# ME461_F28027.net
KiCad netlist of a schematic drawn in EAGLE
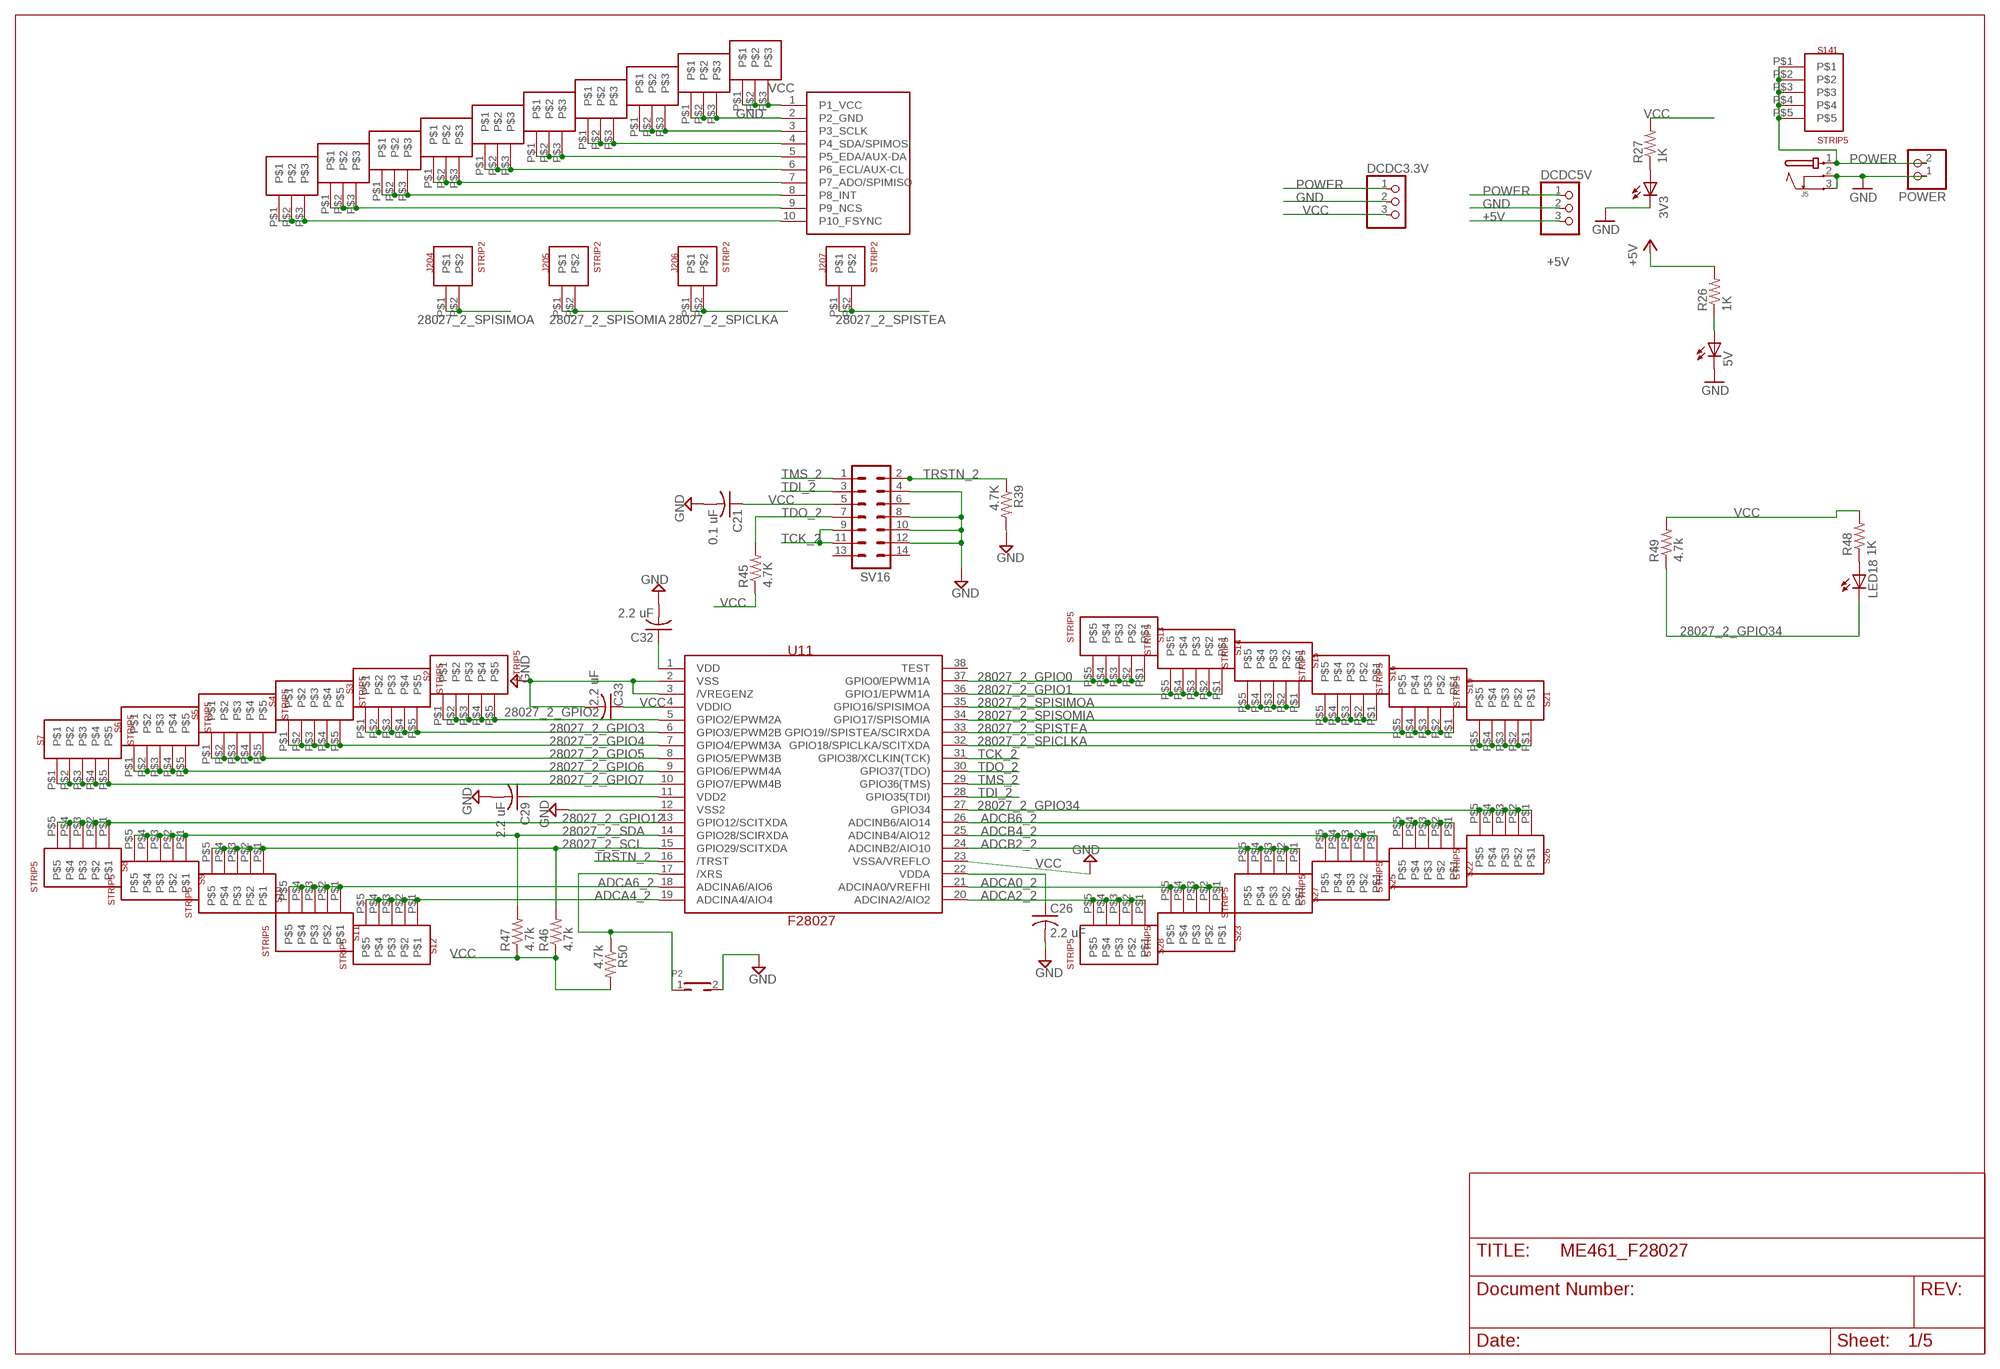
[diagram p0: schematic, sheet 1]
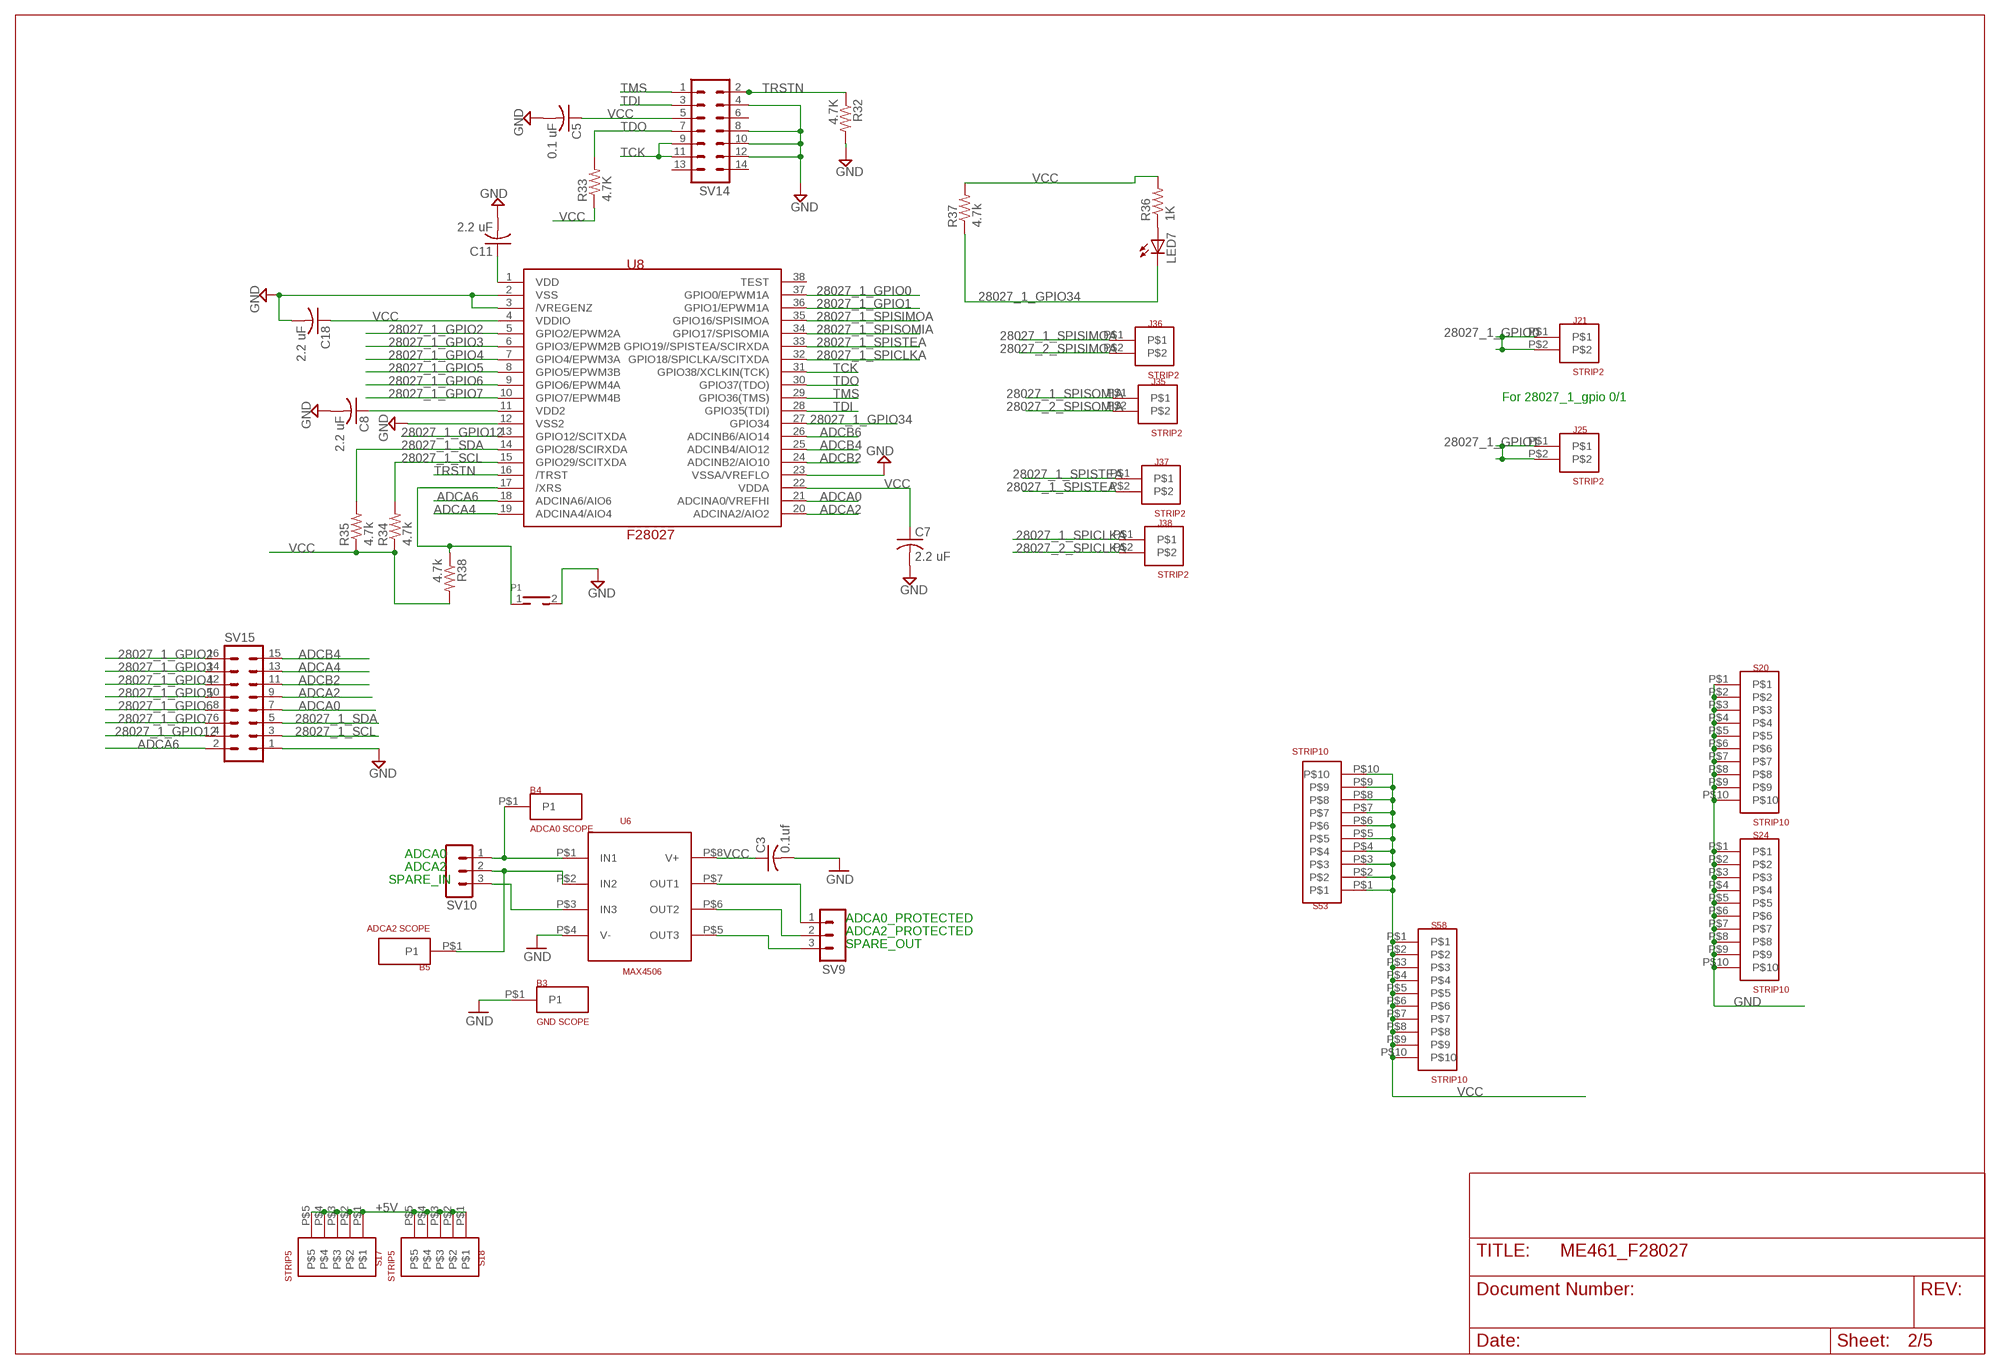
[diagram p1: schematic, sheet 2]
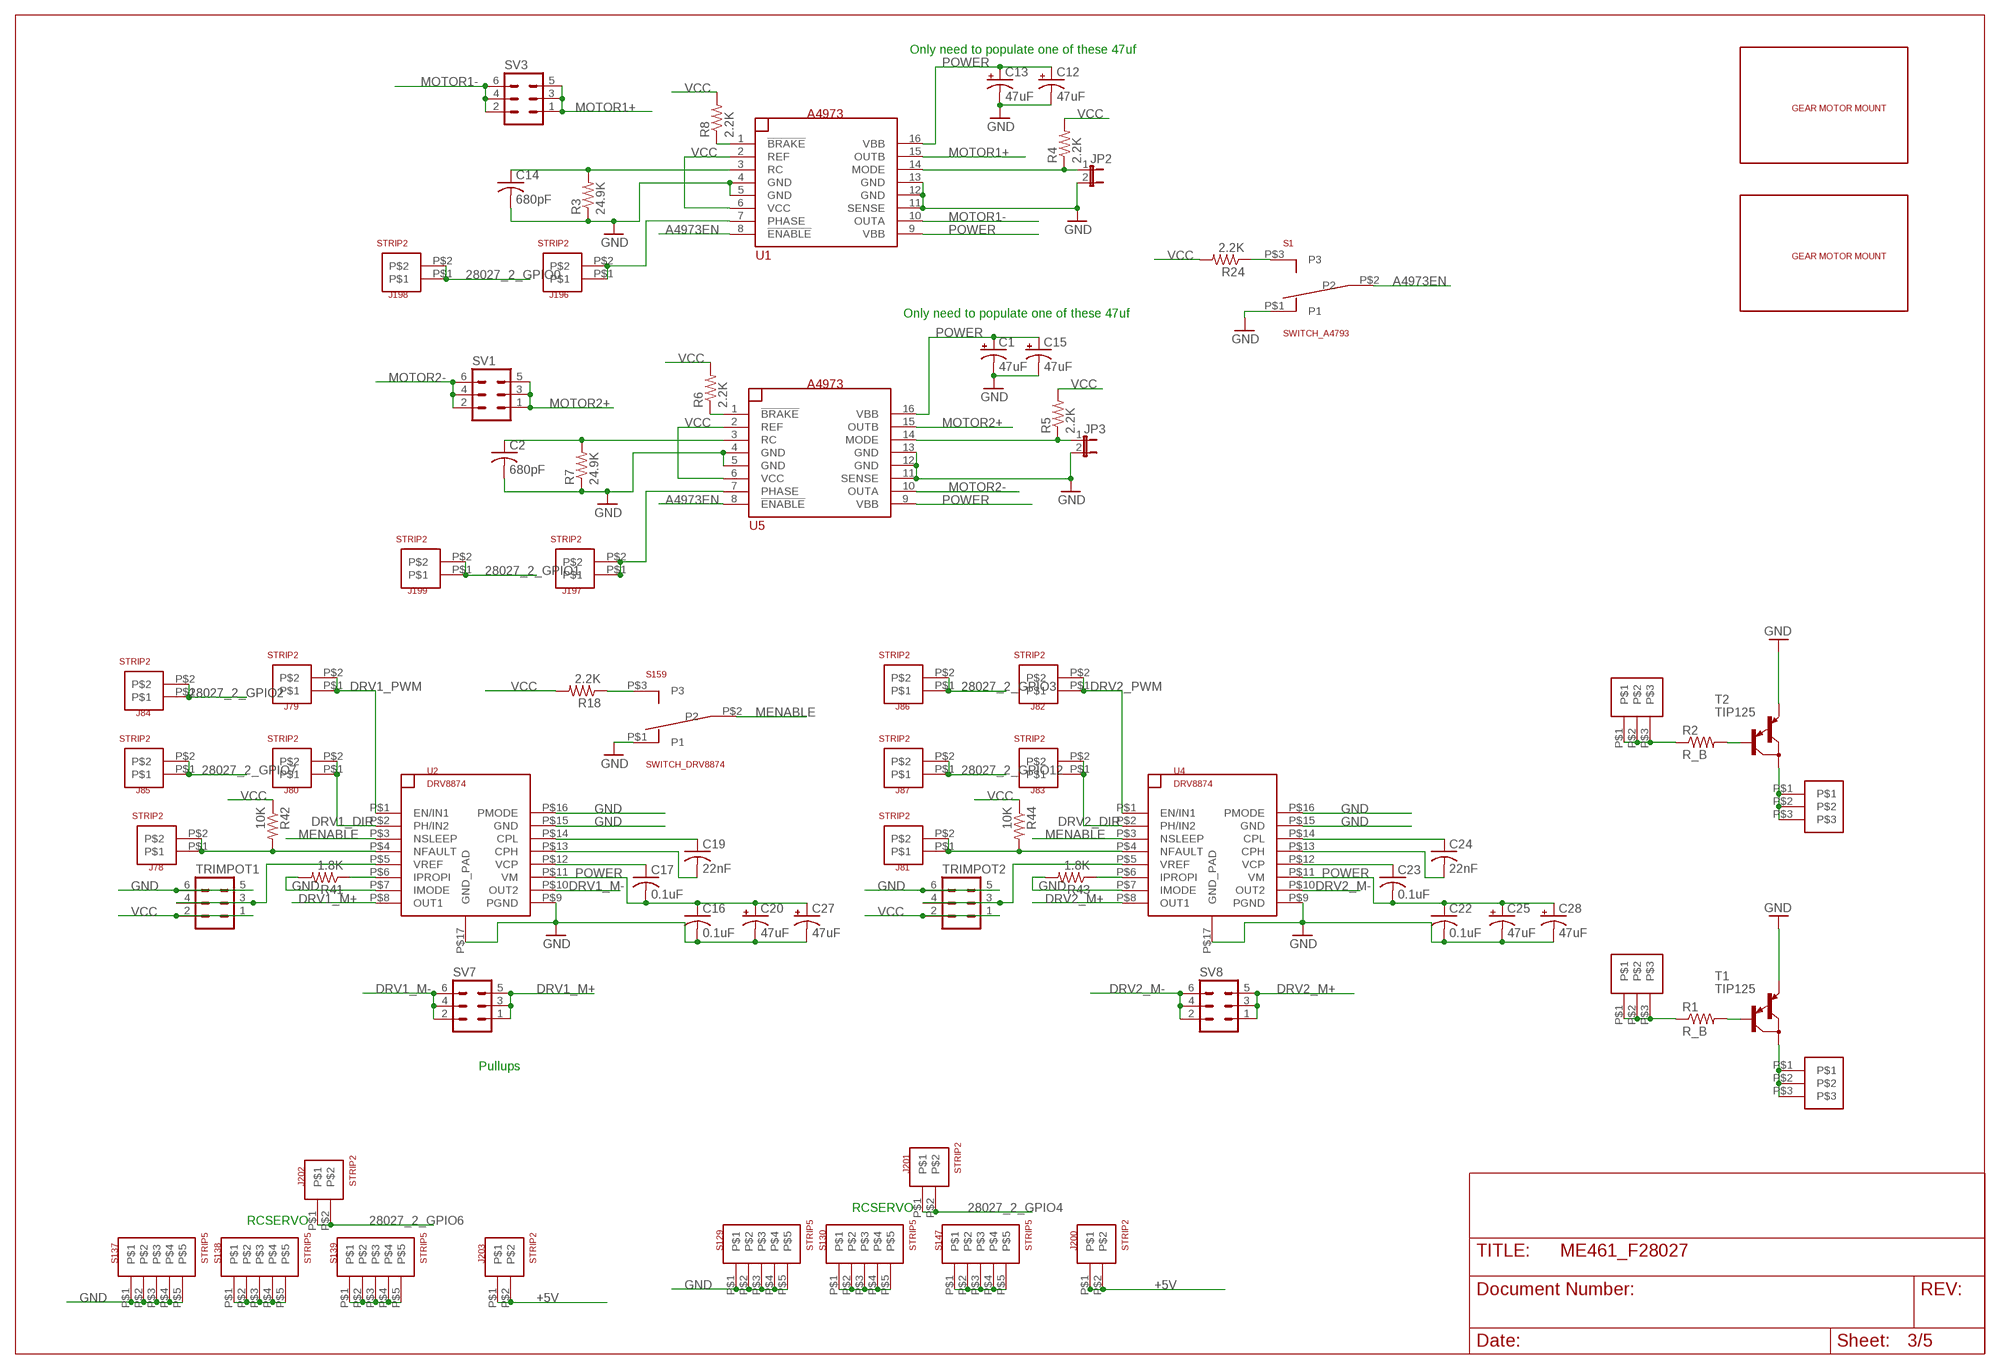
[diagram p2: schematic, sheet 3]
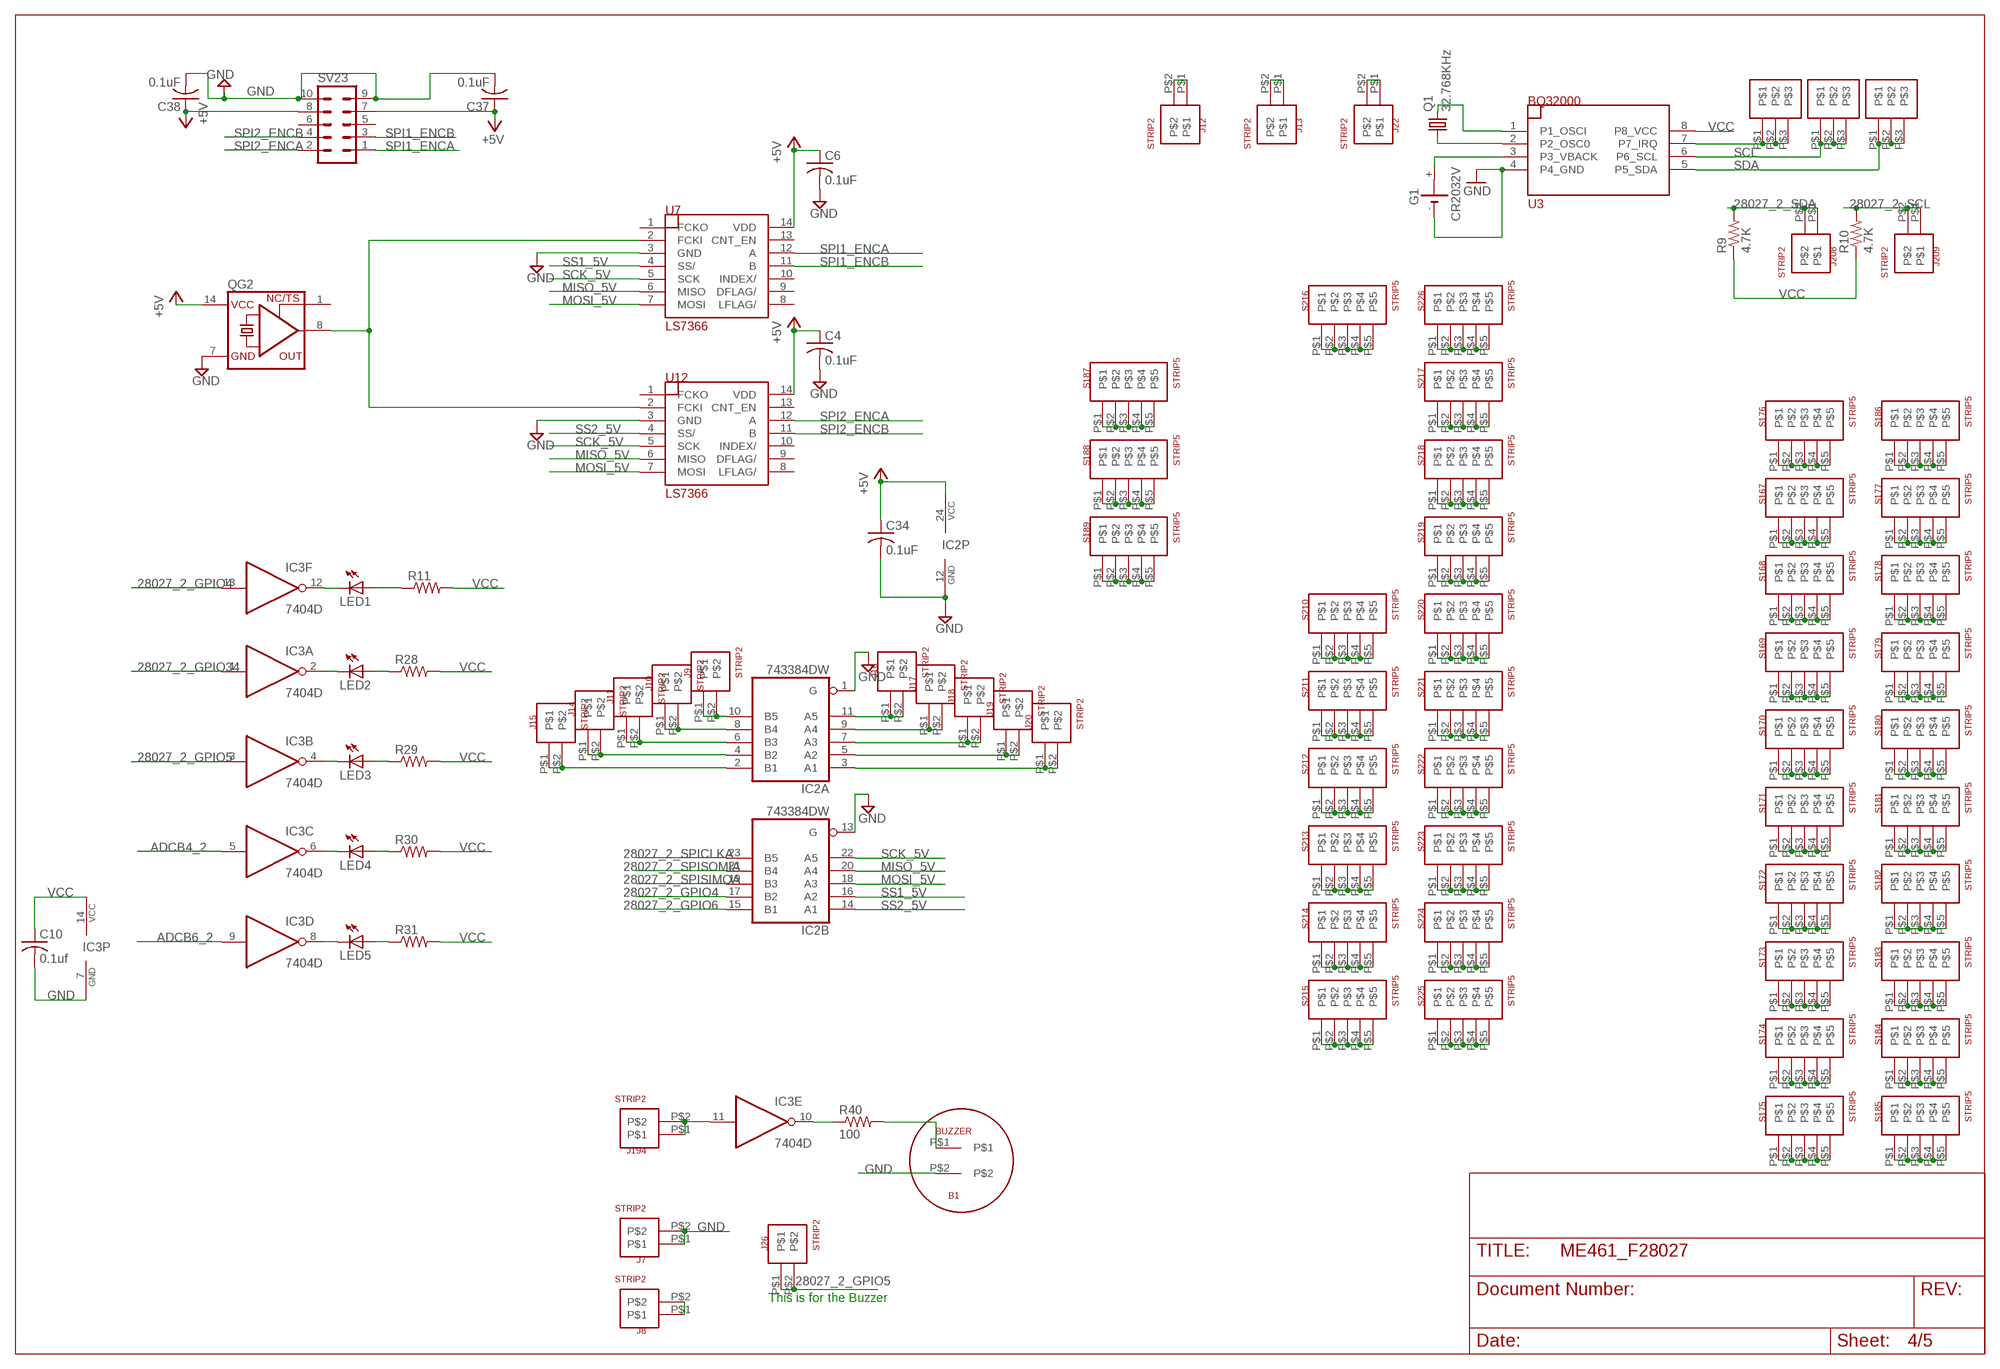
[diagram p3: schematic, sheet 4]
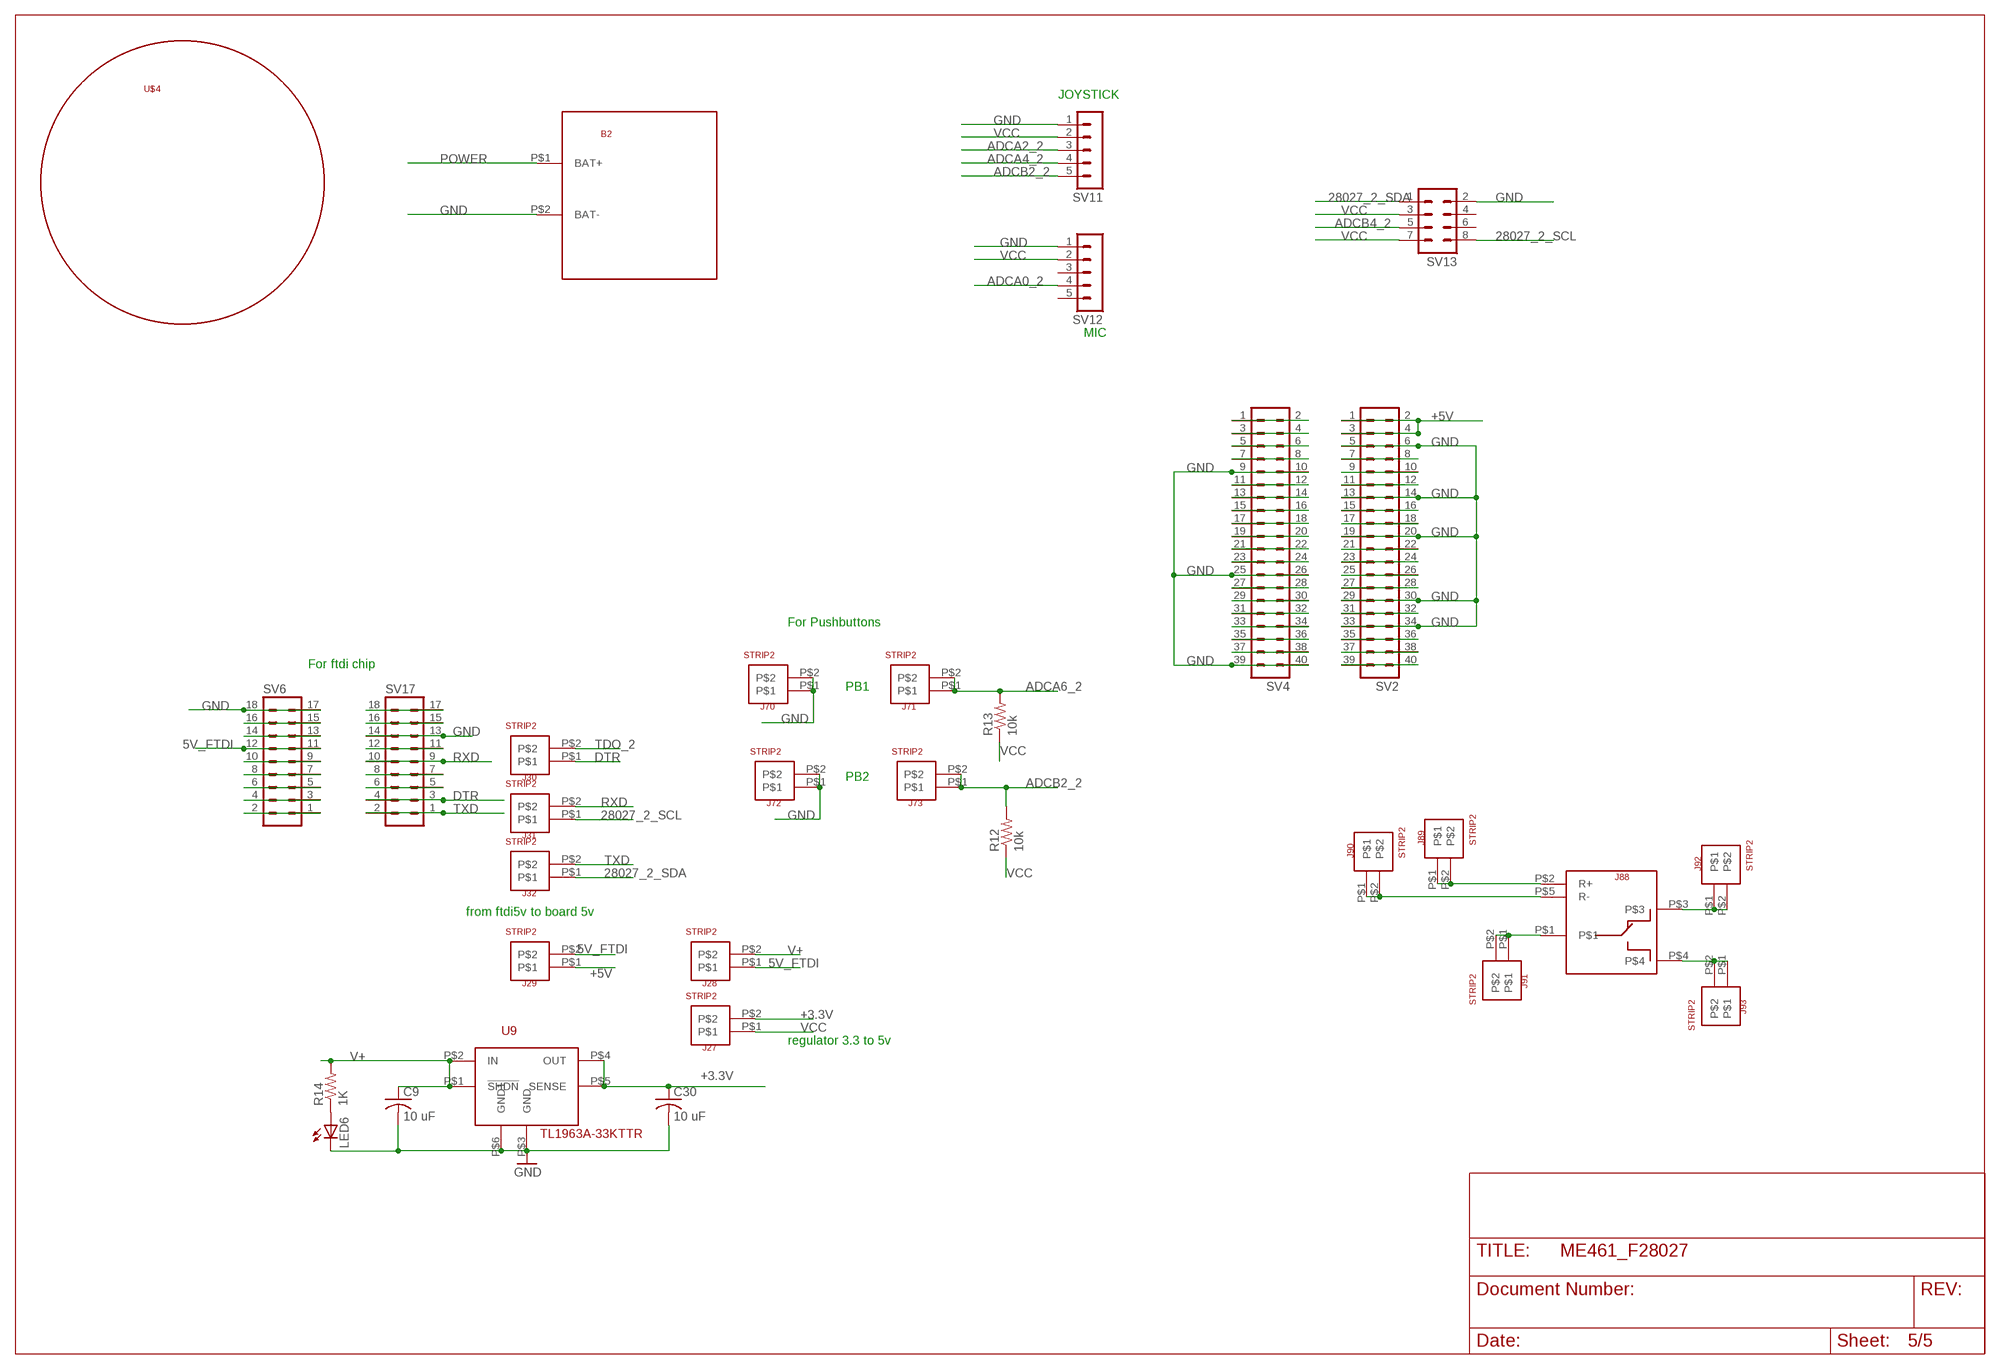
[diagram p4: schematic, sheet 5]

(export (version "E")
  (design (tool "Eeschema 10.0.6"))
  (components
    (comp (ref "C1")
      (value "47uF")
      (footprint "eagle-import:153CLV-0810")
      (libsource (lib "eagle-import") (part "CPOL-US153CLV-0810"))
    )
    (comp (ref "C2")
      (value "680pF")
      (footprint "eagle-import:C1206")
      (libsource (lib "eagle-import") (part "C-USC1206"))
    )
    (comp (ref "C12")
      (value "47uF")
      (footprint "eagle-import:153CLV-0810")
      (libsource (lib "eagle-import") (part "CPOL-US153CLV-0810"))
    )
    (comp (ref "C13")
      (value "47uF")
      (footprint "eagle-import:153CLV-0810")
      (libsource (lib "eagle-import") (part "CPOL-US153CLV-0810"))
    )
    (comp (ref "C14")
      (value "680pF")
      (footprint "eagle-import:C1206")
      (libsource (lib "eagle-import") (part "C-USC1206"))
    )
    (comp (ref "C15")
      (value "47uF")
      (footprint "eagle-import:153CLV-0810")
      (libsource (lib "eagle-import") (part "CPOL-US153CLV-0810"))
    )
    (comp (ref "C16")
      (value "0.1uF")
      (footprint "eagle-import:C1206")
      (libsource (lib "eagle-import") (part "C-USC1206"))
    )
    (comp (ref "C17")
      (value "0.1uF")
      (footprint "eagle-import:C1206")
      (libsource (lib "eagle-import") (part "C-USC1206"))
    )
    (comp (ref "C19")
      (value "22nF")
      (footprint "eagle-import:C1206")
      (libsource (lib "eagle-import") (part "C-USC1206"))
    )
    (comp (ref "C20")
      (value "47uF")
      (footprint "eagle-import:153CLV-0810")
      (libsource (lib "eagle-import") (part "CPOL-US153CLV-0810"))
    )
    (comp (ref "C22")
      (value "0.1uF")
      (footprint "eagle-import:C1206")
      (libsource (lib "eagle-import") (part "C-USC1206"))
    )
    (comp (ref "C23")
      (value "0.1uF")
      (footprint "eagle-import:C1206")
      (libsource (lib "eagle-import") (part "C-USC1206"))
    )
    (comp (ref "C24")
      (value "22nF")
      (footprint "eagle-import:C1206")
      (libsource (lib "eagle-import") (part "C-USC1206"))
    )
    (comp (ref "C25")
      (value "47uF")
      (footprint "eagle-import:153CLV-0810")
      (libsource (lib "eagle-import") (part "CPOL-US153CLV-0810"))
    )
    (comp (ref "C27")
      (value "47uF")
      (footprint "eagle-import:153CLV-0810")
      (libsource (lib "eagle-import") (part "CPOL-US153CLV-0810"))
    )
    (comp (ref "C28")
      (value "47uF")
      (footprint "eagle-import:153CLV-0810")
      (libsource (lib "eagle-import") (part "CPOL-US153CLV-0810"))
    )
    (comp (ref "J4")
      (value "STRIP3")
      (footprint "eagle-import:STRIP3")
      (libsource (lib "eagle-import") (part "STRIP3"))
    )
    (comp (ref "J6")
      (value "STRIP3")
      (footprint "eagle-import:STRIP3")
      (libsource (lib "eagle-import") (part "STRIP3"))
    )
    (comp (ref "J23")
      (value "STRIP3")
      (footprint "eagle-import:STRIP3")
      (libsource (lib "eagle-import") (part "STRIP3"))
    )
    (comp (ref "J24")
      (value "STRIP3")
      (footprint "eagle-import:STRIP3")
      (libsource (lib "eagle-import") (part "STRIP3"))
    )
    (comp (ref "J78")
      (value "STRIP2")
      (footprint "eagle-import:STRIP2")
      (libsource (lib "eagle-import") (part "STRIP2"))
    )
    (comp (ref "J79")
      (value "STRIP2")
      (footprint "eagle-import:STRIP2")
      (libsource (lib "eagle-import") (part "STRIP2"))
    )
    (comp (ref "J80")
      (value "STRIP2")
      (footprint "eagle-import:STRIP2")
      (libsource (lib "eagle-import") (part "STRIP2"))
    )
    (comp (ref "J81")
      (value "STRIP2")
      (footprint "eagle-import:STRIP2")
      (libsource (lib "eagle-import") (part "STRIP2"))
    )
    (comp (ref "J82")
      (value "STRIP2")
      (footprint "eagle-import:STRIP2")
      (libsource (lib "eagle-import") (part "STRIP2"))
    )
    (comp (ref "J83")
      (value "STRIP2")
      (footprint "eagle-import:STRIP2")
      (libsource (lib "eagle-import") (part "STRIP2"))
    )
    (comp (ref "J84")
      (value "STRIP2")
      (footprint "eagle-import:STRIP2")
      (libsource (lib "eagle-import") (part "STRIP2"))
    )
    (comp (ref "J85")
      (value "STRIP2")
      (footprint "eagle-import:STRIP2")
      (libsource (lib "eagle-import") (part "STRIP2"))
    )
    (comp (ref "J86")
      (value "STRIP2")
      (footprint "eagle-import:STRIP2")
      (libsource (lib "eagle-import") (part "STRIP2"))
    )
    (comp (ref "J87")
      (value "STRIP2")
      (footprint "eagle-import:STRIP2")
      (libsource (lib "eagle-import") (part "STRIP2"))
    )
    (comp (ref "J196")
      (value "STRIP2")
      (footprint "eagle-import:STRIP2")
      (libsource (lib "eagle-import") (part "STRIP2"))
    )
    (comp (ref "J197")
      (value "STRIP2")
      (footprint "eagle-import:STRIP2")
      (libsource (lib "eagle-import") (part "STRIP2"))
    )
    (comp (ref "J198")
      (value "STRIP2")
      (footprint "eagle-import:STRIP2")
      (libsource (lib "eagle-import") (part "STRIP2"))
    )
    (comp (ref "J199")
      (value "STRIP2")
      (footprint "eagle-import:STRIP2")
      (libsource (lib "eagle-import") (part "STRIP2"))
    )
    (comp (ref "J200")
      (value "STRIP2")
      (footprint "eagle-import:STRIP2")
      (libsource (lib "eagle-import") (part "STRIP2"))
    )
    (comp (ref "J201")
      (value "STRIP2")
      (footprint "eagle-import:STRIP2")
      (libsource (lib "eagle-import") (part "STRIP2"))
    )
    (comp (ref "J202")
      (value "STRIP2")
      (footprint "eagle-import:STRIP2")
      (libsource (lib "eagle-import") (part "STRIP2"))
    )
    (comp (ref "J203")
      (value "STRIP2")
      (footprint "eagle-import:STRIP2")
      (libsource (lib "eagle-import") (part "STRIP2"))
    )
    (comp (ref "JP2")
      (value "JP1E")
      (footprint "eagle-import:JP1")
      (libsource (lib "eagle-import") (part "JP1E"))
    )
    (comp (ref "JP3")
      (value "JP1E")
      (footprint "eagle-import:JP1")
      (libsource (lib "eagle-import") (part "JP1E"))
    )
    (comp (ref "R1")
      (value "R_B")
      (footprint "eagle-import:0207_10")
      (libsource (lib "eagle-import") (part "R-US_0207/10"))
    )
    (comp (ref "R2")
      (value "R_B")
      (footprint "eagle-import:0207_10")
      (libsource (lib "eagle-import") (part "R-US_0207/10"))
    )
    (comp (ref "R3")
      (value "24.9K")
      (footprint "eagle-import:M1206")
      (libsource (lib "eagle-import") (part "R-US_M1206"))
    )
    (comp (ref "R4")
      (value "2.2K")
      (footprint "eagle-import:M1206")
      (libsource (lib "eagle-import") (part "R-US_M1206"))
    )
    (comp (ref "R5")
      (value "2.2K")
      (footprint "eagle-import:M1206")
      (libsource (lib "eagle-import") (part "R-US_M1206"))
    )
    (comp (ref "R6")
      (value "2.2K")
      (footprint "eagle-import:M1206")
      (libsource (lib "eagle-import") (part "R-US_M1206"))
    )
    (comp (ref "R7")
      (value "24.9K")
      (footprint "eagle-import:M1206")
      (libsource (lib "eagle-import") (part "R-US_M1206"))
    )
    (comp (ref "R8")
      (value "2.2K")
      (footprint "eagle-import:M1206")
      (libsource (lib "eagle-import") (part "R-US_M1206"))
    )
    (comp (ref "R18")
      (value "2.2K")
      (footprint "eagle-import:M1206")
      (libsource (lib "eagle-import") (part "R-US_M1206"))
    )
    (comp (ref "R24")
      (value "2.2K")
      (footprint "eagle-import:M1206")
      (libsource (lib "eagle-import") (part "R-US_M1206"))
    )
    (comp (ref "R41")
      (value "1.8K")
      (footprint "eagle-import:M1206")
      (libsource (lib "eagle-import") (part "R-US_M1206"))
    )
    (comp (ref "R42")
      (value "10K")
      (footprint "eagle-import:M1206")
      (libsource (lib "eagle-import") (part "R-US_M1206"))
    )
    (comp (ref "R43")
      (value "1.8K")
      (footprint "eagle-import:M1206")
      (libsource (lib "eagle-import") (part "R-US_M1206"))
    )
    (comp (ref "R44")
      (value "10K")
      (footprint "eagle-import:M1206")
      (libsource (lib "eagle-import") (part "R-US_M1206"))
    )
    (comp (ref "S1")
      (value "SWITCH_A4793")
      (footprint "eagle-import:SWITCH_SLIDE")
      (libsource (lib "eagle-import") (part "SWITCH_SLIDE"))
    )
    (comp (ref "S129")
      (value "STRIP5")
      (footprint "eagle-import:STRIP5")
      (libsource (lib "eagle-import") (part "STRIP5"))
    )
    (comp (ref "S130")
      (value "STRIP5")
      (footprint "eagle-import:STRIP5")
      (libsource (lib "eagle-import") (part "STRIP5"))
    )
    (comp (ref "S137")
      (value "STRIP5")
      (footprint "eagle-import:STRIP5")
      (libsource (lib "eagle-import") (part "STRIP5"))
    )
    (comp (ref "S138")
      (value "STRIP5")
      (footprint "eagle-import:STRIP5")
      (libsource (lib "eagle-import") (part "STRIP5"))
    )
    (comp (ref "S139")
      (value "STRIP5")
      (footprint "eagle-import:STRIP5")
      (libsource (lib "eagle-import") (part "STRIP5"))
    )
    (comp (ref "S147")
      (value "STRIP5")
      (footprint "eagle-import:STRIP5")
      (libsource (lib "eagle-import") (part "STRIP5"))
    )
    (comp (ref "S159")
      (value "SWITCH_DRV8874")
      (footprint "eagle-import:SWITCH_SLIDE")
      (libsource (lib "eagle-import") (part "SWITCH_SLIDE"))
    )
    (comp (ref "SV1")
      (value "MA03-2")
      (footprint "eagle-import:MA03-2")
      (libsource (lib "eagle-import") (part "MA03-2"))
    )
    (comp (ref "SV3")
      (value "MA03-2")
      (footprint "eagle-import:MA03-2")
      (libsource (lib "eagle-import") (part "MA03-2"))
    )
    (comp (ref "SV7")
      (value "MA03-2")
      (footprint "eagle-import:MA03-2")
      (libsource (lib "eagle-import") (part "MA03-2"))
    )
    (comp (ref "SV8")
      (value "MA03-2")
      (footprint "eagle-import:MA03-2")
      (libsource (lib "eagle-import") (part "MA03-2"))
    )
    (comp (ref "T1")
      (value "TIP125")
      (footprint "eagle-import:TO220")
      (libsource (lib "eagle-import") (part "TIP125"))
    )
    (comp (ref "T2")
      (value "TIP125")
      (footprint "eagle-import:TO220")
      (libsource (lib "eagle-import") (part "TIP125"))
    )
    (comp (ref "TRIMPOT1")
      (value "MA03-2")
      (footprint "eagle-import:MA03-2")
      (libsource (lib "eagle-import") (part "MA03-2"))
    )
    (comp (ref "TRIMPOT2")
      (value "MA03-2")
      (footprint "eagle-import:MA03-2")
      (libsource (lib "eagle-import") (part "MA03-2"))
    )
    (comp (ref "U$2")
      (value "GEARMOTOR_MOUNT")
      (footprint "eagle-import:GEARMOTOR_MOUNT")
      (libsource (lib "eagle-import") (part "GEARMOTOR_MOUNT"))
    )
    (comp (ref "U$3")
      (value "GEARMOTOR_MOUNT")
      (footprint "eagle-import:GEARMOTOR_MOUNT")
      (libsource (lib "eagle-import") (part "GEARMOTOR_MOUNT"))
    )
    (comp (ref "U1")
      (value "A4973")
      (footprint "eagle-import:SO16W")
      (libsource (lib "eagle-import") (part "A3953"))
    )
    (comp (ref "U2")
      (value "DRV8874")
      (footprint "eagle-import:HTSSOP16")
      (libsource (lib "eagle-import") (part "DRV8874"))
    )
    (comp (ref "U4")
      (value "DRV8874")
      (footprint "eagle-import:HTSSOP16")
      (libsource (lib "eagle-import") (part "DRV8874"))
    )
    (comp (ref "U5")
      (value "A4973")
      (footprint "eagle-import:SO16W")
      (libsource (lib "eagle-import") (part "A3953"))
    )
    (comp (ref "B1")
      (value "BUZZER")
      (footprint "eagle-import:BUZZER")
      (libsource (lib "eagle-import") (part "BUZZER"))
    )
    (comp (ref "C4")
      (value "0.1uF")
      (footprint "eagle-import:C1206")
      (libsource (lib "eagle-import") (part "C-USC1206"))
    )
    (comp (ref "C6")
      (value "0.1uF")
      (footprint "eagle-import:C1206")
      (libsource (lib "eagle-import") (part "C-USC1206"))
    )
    (comp (ref "C10")
      (value "0.1uf")
      (footprint "eagle-import:C1206")
      (libsource (lib "eagle-import") (part "C-USC1206"))
    )
    (comp (ref "C34")
      (value "0.1uF")
      (footprint "eagle-import:C1206")
      (libsource (lib "eagle-import") (part "C-USC1206"))
    )
    (comp (ref "C37")
      (value "0.1uF")
      (footprint "eagle-import:C1206")
      (libsource (lib "eagle-import") (part "C-USC1206"))
    )
    (comp (ref "C38")
      (value "0.1uF")
      (footprint "eagle-import:C1206")
      (libsource (lib "eagle-import") (part "C-USC1206"))
    )
    (comp (ref "G1")
      (value "CR2032V")
      (footprint "eagle-import:CR2032V")
      (libsource (lib "eagle-import") (part "CR2032V"))
    )
    (comp (ref "IC2")
      (value "743384DW")
      (footprint "eagle-import:SO24W")
      (libsource (lib "eagle-import") (part "743384DW"))
    )
    (comp (ref "IC3")
      (value "7404D")
      (footprint "eagle-import:SO14")
      (libsource (lib "eagle-import") (part "7404D"))
    )
    (comp (ref "J1")
      (value "STRIP3")
      (footprint "eagle-import:STRIP3")
      (libsource (lib "eagle-import") (part "STRIP3"))
    )
    (comp (ref "J2")
      (value "STRIP3")
      (footprint "eagle-import:STRIP3")
      (libsource (lib "eagle-import") (part "STRIP3"))
    )
    (comp (ref "J3")
      (value "STRIP3")
      (footprint "eagle-import:STRIP3")
      (libsource (lib "eagle-import") (part "STRIP3"))
    )
    (comp (ref "J7")
      (value "STRIP2")
      (footprint "eagle-import:STRIP2")
      (libsource (lib "eagle-import") (part "STRIP2"))
    )
    (comp (ref "J8")
      (value "STRIP2")
      (footprint "eagle-import:STRIP2")
      (libsource (lib "eagle-import") (part "STRIP2"))
    )
    (comp (ref "J9")
      (value "STRIP2")
      (footprint "eagle-import:STRIP2")
      (libsource (lib "eagle-import") (part "STRIP2"))
    )
    (comp (ref "J10")
      (value "STRIP2")
      (footprint "eagle-import:STRIP2")
      (libsource (lib "eagle-import") (part "STRIP2"))
    )
    (comp (ref "J11")
      (value "STRIP2")
      (footprint "eagle-import:STRIP2")
      (libsource (lib "eagle-import") (part "STRIP2"))
    )
    (comp (ref "J12")
      (value "STRIP2")
      (footprint "eagle-import:STRIP2")
      (libsource (lib "eagle-import") (part "STRIP2"))
    )
    (comp (ref "J13")
      (value "STRIP2")
      (footprint "eagle-import:STRIP2")
      (libsource (lib "eagle-import") (part "STRIP2"))
    )
    (comp (ref "J14")
      (value "STRIP2")
      (footprint "eagle-import:STRIP2")
      (libsource (lib "eagle-import") (part "STRIP2"))
    )
    (comp (ref "J15")
      (value "STRIP2")
      (footprint "eagle-import:STRIP2")
      (libsource (lib "eagle-import") (part "STRIP2"))
    )
    (comp (ref "J16")
      (value "STRIP2")
      (footprint "eagle-import:STRIP2")
      (libsource (lib "eagle-import") (part "STRIP2"))
    )
    (comp (ref "J17")
      (value "STRIP2")
      (footprint "eagle-import:STRIP2")
      (libsource (lib "eagle-import") (part "STRIP2"))
    )
    (comp (ref "J18")
      (value "STRIP2")
      (footprint "eagle-import:STRIP2")
      (libsource (lib "eagle-import") (part "STRIP2"))
    )
    (comp (ref "J19")
      (value "STRIP2")
      (footprint "eagle-import:STRIP2")
      (libsource (lib "eagle-import") (part "STRIP2"))
    )
    (comp (ref "J20")
      (value "STRIP2")
      (footprint "eagle-import:STRIP2")
      (libsource (lib "eagle-import") (part "STRIP2"))
    )
    (comp (ref "J22")
      (value "STRIP2")
      (footprint "eagle-import:STRIP2")
      (libsource (lib "eagle-import") (part "STRIP2"))
    )
    (comp (ref "J26")
      (value "STRIP2")
      (footprint "eagle-import:STRIP2")
      (libsource (lib "eagle-import") (part "STRIP2"))
    )
    (comp (ref "J194")
      (value "STRIP2")
      (footprint "eagle-import:STRIP2")
      (libsource (lib "eagle-import") (part "STRIP2"))
    )
    (comp (ref "J208")
      (value "STRIP2")
      (footprint "eagle-import:STRIP2")
      (libsource (lib "eagle-import") (part "STRIP2"))
    )
    (comp (ref "J209")
      (value "STRIP2")
      (footprint "eagle-import:STRIP2")
      (libsource (lib "eagle-import") (part "STRIP2"))
    )
    (comp (ref "LED1")
      (value "LEDCHIPLED_1206")
      (footprint "eagle-import:CHIPLED_1206")
      (libsource (lib "eagle-import") (part "LEDCHIPLED_1206"))
    )
    (comp (ref "LED2")
      (value "LEDCHIPLED_1206")
      (footprint "eagle-import:CHIPLED_1206")
      (libsource (lib "eagle-import") (part "LEDCHIPLED_1206"))
    )
    (comp (ref "LED3")
      (value "LEDCHIPLED_1206")
      (footprint "eagle-import:CHIPLED_1206")
      (libsource (lib "eagle-import") (part "LEDCHIPLED_1206"))
    )
    (comp (ref "LED4")
      (value "LEDCHIPLED_1206")
      (footprint "eagle-import:CHIPLED_1206")
      (libsource (lib "eagle-import") (part "LEDCHIPLED_1206"))
    )
    (comp (ref "LED5")
      (value "LEDCHIPLED_1206")
      (footprint "eagle-import:CHIPLED_1206")
      (libsource (lib "eagle-import") (part "LEDCHIPLED_1206"))
    )
    (comp (ref "Q1")
      (value "32.768KHz")
      (footprint "eagle-import:TC26H")
      (libsource (lib "eagle-import") (part "CRYTALTC26H"))
    )
    (comp (ref "QG2")
      (value "XO-14")
      (footprint "eagle-import:DIL14S")
      (libsource (lib "eagle-import") (part "XO-14"))
    )
    (comp (ref "R9")
      (value "4.7K")
      (footprint "eagle-import:R1206")
      (libsource (lib "eagle-import") (part "R-US_R1206"))
    )
    (comp (ref "R10")
      (value "4.7K")
      (footprint "eagle-import:R1206")
      (libsource (lib "eagle-import") (part "R-US_R1206"))
    )
    (comp (ref "R11")
      (value "R-US_R1206")
      (footprint "eagle-import:R1206")
      (libsource (lib "eagle-import") (part "R-US_R1206"))
    )
    (comp (ref "R28")
      (value "R-US_R1206")
      (footprint "eagle-import:R1206")
      (libsource (lib "eagle-import") (part "R-US_R1206"))
    )
    (comp (ref "R29")
      (value "R-US_R1206")
      (footprint "eagle-import:R1206")
      (libsource (lib "eagle-import") (part "R-US_R1206"))
    )
    (comp (ref "R30")
      (value "R-US_R1206")
      (footprint "eagle-import:R1206")
      (libsource (lib "eagle-import") (part "R-US_R1206"))
    )
    (comp (ref "R31")
      (value "R-US_R1206")
      (footprint "eagle-import:R1206")
      (libsource (lib "eagle-import") (part "R-US_R1206"))
    )
    (comp (ref "R40")
      (value "100")
      (footprint "eagle-import:R1206")
      (libsource (lib "eagle-import") (part "R-US_R1206"))
    )
    (comp (ref "S167")
      (value "STRIP5")
      (footprint "eagle-import:STRIP5")
      (libsource (lib "eagle-import") (part "STRIP5"))
    )
    (comp (ref "S168")
      (value "STRIP5")
      (footprint "eagle-import:STRIP5")
      (libsource (lib "eagle-import") (part "STRIP5"))
    )
    (comp (ref "S169")
      (value "STRIP5")
      (footprint "eagle-import:STRIP5")
      (libsource (lib "eagle-import") (part "STRIP5"))
    )
    (comp (ref "S170")
      (value "STRIP5")
      (footprint "eagle-import:STRIP5")
      (libsource (lib "eagle-import") (part "STRIP5"))
    )
    (comp (ref "S171")
      (value "STRIP5")
      (footprint "eagle-import:STRIP5")
      (libsource (lib "eagle-import") (part "STRIP5"))
    )
    (comp (ref "S172")
      (value "STRIP5")
      (footprint "eagle-import:STRIP5")
      (libsource (lib "eagle-import") (part "STRIP5"))
    )
    (comp (ref "S173")
      (value "STRIP5")
      (footprint "eagle-import:STRIP5")
      (libsource (lib "eagle-import") (part "STRIP5"))
    )
    (comp (ref "S174")
      (value "STRIP5")
      (footprint "eagle-import:STRIP5")
      (libsource (lib "eagle-import") (part "STRIP5"))
    )
    (comp (ref "S175")
      (value "STRIP5")
      (footprint "eagle-import:STRIP5")
      (libsource (lib "eagle-import") (part "STRIP5"))
    )
    (comp (ref "S176")
      (value "STRIP5")
      (footprint "eagle-import:STRIP5")
      (libsource (lib "eagle-import") (part "STRIP5"))
    )
    (comp (ref "S177")
      (value "STRIP5")
      (footprint "eagle-import:STRIP5")
      (libsource (lib "eagle-import") (part "STRIP5"))
    )
    (comp (ref "S178")
      (value "STRIP5")
      (footprint "eagle-import:STRIP5")
      (libsource (lib "eagle-import") (part "STRIP5"))
    )
    (comp (ref "S179")
      (value "STRIP5")
      (footprint "eagle-import:STRIP5")
      (libsource (lib "eagle-import") (part "STRIP5"))
    )
    (comp (ref "S180")
      (value "STRIP5")
      (footprint "eagle-import:STRIP5")
      (libsource (lib "eagle-import") (part "STRIP5"))
    )
    (comp (ref "S181")
      (value "STRIP5")
      (footprint "eagle-import:STRIP5")
      (libsource (lib "eagle-import") (part "STRIP5"))
    )
    (comp (ref "S182")
      (value "STRIP5")
      (footprint "eagle-import:STRIP5")
      (libsource (lib "eagle-import") (part "STRIP5"))
    )
    (comp (ref "S183")
      (value "STRIP5")
      (footprint "eagle-import:STRIP5")
      (libsource (lib "eagle-import") (part "STRIP5"))
    )
    (comp (ref "S184")
      (value "STRIP5")
      (footprint "eagle-import:STRIP5")
      (libsource (lib "eagle-import") (part "STRIP5"))
    )
    (comp (ref "S185")
      (value "STRIP5")
      (footprint "eagle-import:STRIP5")
      (libsource (lib "eagle-import") (part "STRIP5"))
    )
    (comp (ref "S186")
      (value "STRIP5")
      (footprint "eagle-import:STRIP5")
      (libsource (lib "eagle-import") (part "STRIP5"))
    )
    (comp (ref "S187")
      (value "STRIP5")
      (footprint "eagle-import:STRIP5")
      (libsource (lib "eagle-import") (part "STRIP5"))
    )
    (comp (ref "S188")
      (value "STRIP5")
      (footprint "eagle-import:STRIP5")
      (libsource (lib "eagle-import") (part "STRIP5"))
    )
    (comp (ref "S189")
      (value "STRIP5")
      (footprint "eagle-import:STRIP5")
      (libsource (lib "eagle-import") (part "STRIP5"))
    )
    (comp (ref "S210")
      (value "STRIP5")
      (footprint "eagle-import:STRIP5")
      (libsource (lib "eagle-import") (part "STRIP5"))
    )
    (comp (ref "S211")
      (value "STRIP5")
      (footprint "eagle-import:STRIP5")
      (libsource (lib "eagle-import") (part "STRIP5"))
    )
    (comp (ref "S212")
      (value "STRIP5")
      (footprint "eagle-import:STRIP5")
      (libsource (lib "eagle-import") (part "STRIP5"))
    )
    (comp (ref "S213")
      (value "STRIP5")
      (footprint "eagle-import:STRIP5")
      (libsource (lib "eagle-import") (part "STRIP5"))
    )
    (comp (ref "S214")
      (value "STRIP5")
      (footprint "eagle-import:STRIP5")
      (libsource (lib "eagle-import") (part "STRIP5"))
    )
    (comp (ref "S215")
      (value "STRIP5")
      (footprint "eagle-import:STRIP5")
      (libsource (lib "eagle-import") (part "STRIP5"))
    )
    (comp (ref "S216")
      (value "STRIP5")
      (footprint "eagle-import:STRIP5")
      (libsource (lib "eagle-import") (part "STRIP5"))
    )
    (comp (ref "S217")
      (value "STRIP5")
      (footprint "eagle-import:STRIP5")
      (libsource (lib "eagle-import") (part "STRIP5"))
    )
    (comp (ref "S218")
      (value "STRIP5")
      (footprint "eagle-import:STRIP5")
      (libsource (lib "eagle-import") (part "STRIP5"))
    )
    (comp (ref "S219")
      (value "STRIP5")
      (footprint "eagle-import:STRIP5")
      (libsource (lib "eagle-import") (part "STRIP5"))
    )
    (comp (ref "S220")
      (value "STRIP5")
      (footprint "eagle-import:STRIP5")
      (libsource (lib "eagle-import") (part "STRIP5"))
    )
    (comp (ref "S221")
      (value "STRIP5")
      (footprint "eagle-import:STRIP5")
      (libsource (lib "eagle-import") (part "STRIP5"))
    )
    (comp (ref "S222")
      (value "STRIP5")
      (footprint "eagle-import:STRIP5")
      (libsource (lib "eagle-import") (part "STRIP5"))
    )
    (comp (ref "S223")
      (value "STRIP5")
      (footprint "eagle-import:STRIP5")
      (libsource (lib "eagle-import") (part "STRIP5"))
    )
    (comp (ref "S224")
      (value "STRIP5")
      (footprint "eagle-import:STRIP5")
      (libsource (lib "eagle-import") (part "STRIP5"))
    )
    (comp (ref "S225")
      (value "STRIP5")
      (footprint "eagle-import:STRIP5")
      (libsource (lib "eagle-import") (part "STRIP5"))
    )
    (comp (ref "S226")
      (value "STRIP5")
      (footprint "eagle-import:STRIP5")
      (libsource (lib "eagle-import") (part "STRIP5"))
    )
    (comp (ref "SV23")
      (value "MA05-2")
      (footprint "eagle-import:MA05-2")
      (libsource (lib "eagle-import") (part "MA05-2"))
    )
    (comp (ref "U3")
      (value "BQ32000")
      (footprint "eagle-import:SO08")
      (libsource (lib "eagle-import") (part "BQ32000"))
    )
    (comp (ref "U7")
      (value "LS7366")
      (footprint "eagle-import:SO14")
      (libsource (lib "eagle-import") (part "LS7366R"))
    )
    (comp (ref "U12")
      (value "LS7366")
      (footprint "eagle-import:SO14")
      (libsource (lib "eagle-import") (part "LS7366R"))
    )
    (comp (ref "3V3")
      (value "LEDCHIPLED_1206")
      (footprint "eagle-import:CHIPLED_1206")
      (libsource (lib "eagle-import") (part "LEDCHIPLED_1206"))
    )
    (comp (ref "5V")
      (value "LEDCHIPLED_1206")
      (footprint "eagle-import:CHIPLED_1206")
      (libsource (lib "eagle-import") (part "LEDCHIPLED_1206"))
    )
    (comp (ref "C21")
      (value "0.1 uF")
      (footprint "eagle-import:C1206")
      (libsource (lib "eagle-import") (part "C-USC1206"))
    )
    (comp (ref "C26")
      (value "2.2 uF")
      (footprint "eagle-import:C1206")
      (libsource (lib "eagle-import") (part "C-USC1206"))
    )
    (comp (ref "C29")
      (value "2.2 uF")
      (footprint "eagle-import:C1206")
      (libsource (lib "eagle-import") (part "C-USC1206"))
    )
    (comp (ref "C32")
      (value "2.2 uF")
      (footprint "eagle-import:C1206")
      (libsource (lib "eagle-import") (part "C-USC1206"))
    )
    (comp (ref "C33")
      (value "2.2 uF")
      (footprint "eagle-import:C1206")
      (libsource (lib "eagle-import") (part "C-USC1206"))
    )
    (comp (ref "DCDC3.3V")
      (value "PINHD-1X3")
      (footprint "eagle-import:1X03")
      (libsource (lib "eagle-import") (part "PINHD-1X3"))
    )
    (comp (ref "DCDC5V")
      (value "PINHD-1X3")
      (footprint "eagle-import:1X03")
      (libsource (lib "eagle-import") (part "PINHD-1X3"))
    )
    (comp (ref "J5")
      (value "JACK-PMS")
      (footprint "eagle-import:JACK-PMS")
      (libsource (lib "eagle-import") (part "JACK-PMS"))
    )
    (comp (ref "J123")
      (value "STRIP3")
      (footprint "eagle-import:STRIP3")
      (libsource (lib "eagle-import") (part "STRIP3"))
    )
    (comp (ref "J124")
      (value "STRIP3")
      (footprint "eagle-import:STRIP3")
      (libsource (lib "eagle-import") (part "STRIP3"))
    )
    (comp (ref "J125")
      (value "STRIP3")
      (footprint "eagle-import:STRIP3")
      (libsource (lib "eagle-import") (part "STRIP3"))
    )
    (comp (ref "J126")
      (value "STRIP3")
      (footprint "eagle-import:STRIP3")
      (libsource (lib "eagle-import") (part "STRIP3"))
    )
    (comp (ref "J127")
      (value "STRIP3")
      (footprint "eagle-import:STRIP3")
      (libsource (lib "eagle-import") (part "STRIP3"))
    )
    (comp (ref "J128")
      (value "STRIP3")
      (footprint "eagle-import:STRIP3")
      (libsource (lib "eagle-import") (part "STRIP3"))
    )
    (comp (ref "J129")
      (value "STRIP3")
      (footprint "eagle-import:STRIP3")
      (libsource (lib "eagle-import") (part "STRIP3"))
    )
    (comp (ref "J130")
      (value "STRIP3")
      (footprint "eagle-import:STRIP3")
      (libsource (lib "eagle-import") (part "STRIP3"))
    )
    (comp (ref "J131")
      (value "STRIP3")
      (footprint "eagle-import:STRIP3")
      (libsource (lib "eagle-import") (part "STRIP3"))
    )
    (comp (ref "J132")
      (value "STRIP3")
      (footprint "eagle-import:STRIP3")
      (libsource (lib "eagle-import") (part "STRIP3"))
    )
    (comp (ref "J204")
      (value "STRIP2")
      (footprint "eagle-import:STRIP2")
      (libsource (lib "eagle-import") (part "STRIP2"))
    )
    (comp (ref "J205")
      (value "STRIP2")
      (footprint "eagle-import:STRIP2")
      (libsource (lib "eagle-import") (part "STRIP2"))
    )
    (comp (ref "J206")
      (value "STRIP2")
      (footprint "eagle-import:STRIP2")
      (libsource (lib "eagle-import") (part "STRIP2"))
    )
    (comp (ref "J207")
      (value "STRIP2")
      (footprint "eagle-import:STRIP2")
      (libsource (lib "eagle-import") (part "STRIP2"))
    )
    (comp (ref "LED18")
      (value "LEDCHIPLED_1206")
      (footprint "eagle-import:CHIPLED_1206")
      (libsource (lib "eagle-import") (part "LEDCHIPLED_1206"))
    )
    (comp (ref "P2")
      (value "TH_PUSHBOTTON")
      (footprint "eagle-import:TH_PUSHBUTTON")
      (libsource (lib "eagle-import") (part "TH_PUSHBOTTON"))
    )
    (comp (ref "POWER")
      (value "PINHD-1X2")
      (footprint "eagle-import:1X02")
      (libsource (lib "eagle-import") (part "PINHD-1X2"))
    )
    (comp (ref "R26")
      (value "1K")
      (footprint "eagle-import:M1206")
      (libsource (lib "eagle-import") (part "R-US_M1206"))
    )
    (comp (ref "R27")
      (value "1K")
      (footprint "eagle-import:M1206")
      (libsource (lib "eagle-import") (part "R-US_M1206"))
    )
    (comp (ref "R39")
      (value "4.7K")
      (footprint "eagle-import:M1206")
      (libsource (lib "eagle-import") (part "R-US_M1206"))
    )
    (comp (ref "R45")
      (value "4.7K")
      (footprint "eagle-import:M1206")
      (libsource (lib "eagle-import") (part "R-US_M1206"))
    )
    (comp (ref "R46")
      (value "4.7k")
      (footprint "eagle-import:M1206")
      (libsource (lib "eagle-import") (part "R-US_M1206"))
    )
    (comp (ref "R47")
      (value "4.7k")
      (footprint "eagle-import:M1206")
      (libsource (lib "eagle-import") (part "R-US_M1206"))
    )
    (comp (ref "R48")
      (value "1K")
      (footprint "eagle-import:M1206")
      (libsource (lib "eagle-import") (part "R-US_M1206"))
    )
    (comp (ref "R49")
      (value "4.7k")
      (footprint "eagle-import:M1206")
      (libsource (lib "eagle-import") (part "R-US_M1206"))
    )
    (comp (ref "R50")
      (value "4.7k")
      (footprint "eagle-import:M1206")
      (libsource (lib "eagle-import") (part "R-US_M1206"))
    )
    (comp (ref "S2")
      (value "STRIP5")
      (footprint "eagle-import:STRIP5")
      (libsource (lib "eagle-import") (part "STRIP5"))
    )
    (comp (ref "S3")
      (value "STRIP5")
      (footprint "eagle-import:STRIP5")
      (libsource (lib "eagle-import") (part "STRIP5"))
    )
    (comp (ref "S4")
      (value "STRIP5")
      (footprint "eagle-import:STRIP5")
      (libsource (lib "eagle-import") (part "STRIP5"))
    )
    (comp (ref "S5")
      (value "STRIP5")
      (footprint "eagle-import:STRIP5")
      (libsource (lib "eagle-import") (part "STRIP5"))
    )
    (comp (ref "S6")
      (value "STRIP5")
      (footprint "eagle-import:STRIP5")
      (libsource (lib "eagle-import") (part "STRIP5"))
    )
    (comp (ref "S7")
      (value "STRIP5")
      (footprint "eagle-import:STRIP5")
      (libsource (lib "eagle-import") (part "STRIP5"))
    )
    (comp (ref "S8")
      (value "STRIP5")
      (footprint "eagle-import:STRIP5")
      (libsource (lib "eagle-import") (part "STRIP5"))
    )
    (comp (ref "S9")
      (value "STRIP5")
      (footprint "eagle-import:STRIP5")
      (libsource (lib "eagle-import") (part "STRIP5"))
    )
    (comp (ref "S10")
      (value "STRIP5")
      (footprint "eagle-import:STRIP5")
      (libsource (lib "eagle-import") (part "STRIP5"))
    )
    (comp (ref "S11")
      (value "STRIP5")
      (footprint "eagle-import:STRIP5")
      (libsource (lib "eagle-import") (part "STRIP5"))
    )
    (comp (ref "S12")
      (value "STRIP5")
      (footprint "eagle-import:STRIP5")
      (libsource (lib "eagle-import") (part "STRIP5"))
    )
    (comp (ref "S13")
      (value "STRIP5")
      (footprint "eagle-import:STRIP5")
      (libsource (lib "eagle-import") (part "STRIP5"))
    )
    (comp (ref "S14")
      (value "STRIP5")
      (footprint "eagle-import:STRIP5")
      (libsource (lib "eagle-import") (part "STRIP5"))
    )
    (comp (ref "S15")
      (value "STRIP5")
      (footprint "eagle-import:STRIP5")
      (libsource (lib "eagle-import") (part "STRIP5"))
    )
    (comp (ref "S16")
      (value "STRIP5")
      (footprint "eagle-import:STRIP5")
      (libsource (lib "eagle-import") (part "STRIP5"))
    )
    (comp (ref "S19")
      (value "STRIP5")
      (footprint "eagle-import:STRIP5")
      (libsource (lib "eagle-import") (part "STRIP5"))
    )
    (comp (ref "S21")
      (value "STRIP5")
      (footprint "eagle-import:STRIP5")
      (libsource (lib "eagle-import") (part "STRIP5"))
    )
    (comp (ref "S22")
      (value "STRIP5")
      (footprint "eagle-import:STRIP5")
      (libsource (lib "eagle-import") (part "STRIP5"))
    )
    (comp (ref "S23")
      (value "STRIP5")
      (footprint "eagle-import:STRIP5")
      (libsource (lib "eagle-import") (part "STRIP5"))
    )
    (comp (ref "S25")
      (value "STRIP5")
      (footprint "eagle-import:STRIP5")
      (libsource (lib "eagle-import") (part "STRIP5"))
    )
    (comp (ref "S26")
      (value "STRIP5")
      (footprint "eagle-import:STRIP5")
      (libsource (lib "eagle-import") (part "STRIP5"))
    )
    (comp (ref "S27")
      (value "STRIP5")
      (footprint "eagle-import:STRIP5")
      (libsource (lib "eagle-import") (part "STRIP5"))
    )
    (comp (ref "S28")
      (value "STRIP5")
      (footprint "eagle-import:STRIP5")
      (libsource (lib "eagle-import") (part "STRIP5"))
    )
    (comp (ref "S141")
      (value "STRIP5")
      (footprint "eagle-import:STRIP5")
      (libsource (lib "eagle-import") (part "STRIP5"))
    )
    (comp (ref "SV16")
      (value "MA07-2")
      (footprint "eagle-import:MA07-2")
      (libsource (lib "eagle-import") (part "MA07-2"))
    )
    (comp (ref "U$1")
      (value "MPU-9250-BB")
      (footprint "eagle-import:MPU-9250-BB")
      (libsource (lib "eagle-import") (part "MPU-9250-BB"))
    )
    (comp (ref "U11")
      (value "F28027")
      (footprint "eagle-import:DA38")
      (libsource (lib "eagle-import") (part "TMS320F28027DAS"))
    )
    (comp (ref "B2")
      (value "BATTERY_4AA_HOLDER")
      (footprint "eagle-import:BATTERY_4AA_HOLDER")
      (libsource (lib "eagle-import") (part "BATTERY_4AA_HOLDER"))
    )
    (comp (ref "C9")
      (value "10 uF")
      (footprint "eagle-import:C1206")
      (libsource (lib "eagle-import") (part "C-USC1206"))
    )
    (comp (ref "C30")
      (value "10 uF")
      (footprint "eagle-import:C1206")
      (libsource (lib "eagle-import") (part "C-USC1206"))
    )
    (comp (ref "J27")
      (value "STRIP2")
      (footprint "eagle-import:STRIP2")
      (libsource (lib "eagle-import") (part "STRIP2"))
    )
    (comp (ref "J28")
      (value "STRIP2")
      (footprint "eagle-import:STRIP2")
      (libsource (lib "eagle-import") (part "STRIP2"))
    )
    (comp (ref "J29")
      (value "STRIP2")
      (footprint "eagle-import:STRIP2")
      (libsource (lib "eagle-import") (part "STRIP2"))
    )
    (comp (ref "J30")
      (value "STRIP2")
      (footprint "eagle-import:STRIP2")
      (libsource (lib "eagle-import") (part "STRIP2"))
    )
    (comp (ref "J31")
      (value "STRIP2")
      (footprint "eagle-import:STRIP2")
      (libsource (lib "eagle-import") (part "STRIP2"))
    )
    (comp (ref "J32")
      (value "STRIP2")
      (footprint "eagle-import:STRIP2")
      (libsource (lib "eagle-import") (part "STRIP2"))
    )
    (comp (ref "J70")
      (value "STRIP2")
      (footprint "eagle-import:STRIP2")
      (libsource (lib "eagle-import") (part "STRIP2"))
    )
    (comp (ref "J71")
      (value "STRIP2")
      (footprint "eagle-import:STRIP2")
      (libsource (lib "eagle-import") (part "STRIP2"))
    )
    (comp (ref "J72")
      (value "STRIP2")
      (footprint "eagle-import:STRIP2")
      (libsource (lib "eagle-import") (part "STRIP2"))
    )
    (comp (ref "J73")
      (value "STRIP2")
      (footprint "eagle-import:STRIP2")
      (libsource (lib "eagle-import") (part "STRIP2"))
    )
    (comp (ref "J88")
      (value "RELAY_JQC-3F_5V")
      (footprint "eagle-import:RELAY_JQC-3F_5V")
      (libsource (lib "eagle-import") (part "RELAY_JQC-3F_5V"))
    )
    (comp (ref "J89")
      (value "STRIP2")
      (footprint "eagle-import:STRIP2")
      (libsource (lib "eagle-import") (part "STRIP2"))
    )
    (comp (ref "J90")
      (value "STRIP2")
      (footprint "eagle-import:STRIP2")
      (libsource (lib "eagle-import") (part "STRIP2"))
    )
    (comp (ref "J91")
      (value "STRIP2")
      (footprint "eagle-import:STRIP2")
      (libsource (lib "eagle-import") (part "STRIP2"))
    )
    (comp (ref "J92")
      (value "STRIP2")
      (footprint "eagle-import:STRIP2")
      (libsource (lib "eagle-import") (part "STRIP2"))
    )
    (comp (ref "J93")
      (value "STRIP2")
      (footprint "eagle-import:STRIP2")
      (libsource (lib "eagle-import") (part "STRIP2"))
    )
    (comp (ref "LED6")
      (value "LEDCHIPLED_1206")
      (footprint "eagle-import:CHIPLED_1206")
      (libsource (lib "eagle-import") (part "LEDCHIPLED_1206"))
    )
    (comp (ref "R12")
      (value "10k")
      (footprint "eagle-import:R1206")
      (libsource (lib "eagle-import") (part "R-US_R1206"))
    )
    (comp (ref "R13")
      (value "10k")
      (footprint "eagle-import:R1206")
      (libsource (lib "eagle-import") (part "R-US_R1206"))
    )
    (comp (ref "R14")
      (value "1K")
      (footprint "eagle-import:M1206")
      (libsource (lib "eagle-import") (part "R-US_M1206"))
    )
    (comp (ref "SV2")
      (value "MA20-2")
      (footprint "eagle-import:MA20-2")
      (libsource (lib "eagle-import") (part "MA20-2"))
    )
    (comp (ref "SV4")
      (value "MA20-2")
      (footprint "eagle-import:MA20-2")
      (libsource (lib "eagle-import") (part "MA20-2"))
    )
    (comp (ref "SV6")
      (value "MA09-2")
      (footprint "eagle-import:MA09-2")
      (libsource (lib "eagle-import") (part "MA09-2"))
    )
    (comp (ref "SV11")
      (value "MA05-1")
      (footprint "eagle-import:MA05-1")
      (libsource (lib "eagle-import") (part "MA05-1"))
    )
    (comp (ref "SV12")
      (value "MA05-1")
      (footprint "eagle-import:MA05-1")
      (libsource (lib "eagle-import") (part "MA05-1"))
    )
    (comp (ref "SV13")
      (value "MA04-2")
      (footprint "eagle-import:MA04-2")
      (libsource (lib "eagle-import") (part "MA04-2"))
    )
    (comp (ref "SV17")
      (value "MA09-2")
      (footprint "eagle-import:MA09-2")
      (libsource (lib "eagle-import") (part "MA09-2"))
    )
    (comp (ref "U$4")
      (value "CASTERWHEEL")
      (footprint "eagle-import:CASTERWHEEL")
      (libsource (lib "eagle-import") (part "CASTERWHEEL"))
    )
    (comp (ref "U9")
      (value "TL1963A-33KTTR")
      (footprint "eagle-import:TL1963AKTTR")
      (libsource (lib "eagle-import") (part "TL1963A-33KTTR"))
    )
    (comp (ref "B3")
      (value "GND SCOPE")
      (footprint "eagle-import:BANANA_MALE")
      (libsource (lib "eagle-import") (part "BANANA_MALE"))
    )
    (comp (ref "B4")
      (value "ADCA0 SCOPE")
      (footprint "eagle-import:BANANA_MALE")
      (libsource (lib "eagle-import") (part "BANANA_MALE"))
    )
    (comp (ref "B5")
      (value "ADCA2 SCOPE")
      (footprint "eagle-import:BANANA_MALE")
      (libsource (lib "eagle-import") (part "BANANA_MALE"))
    )
    (comp (ref "C3")
      (value "0.1uf")
      (footprint "eagle-import:C1206")
      (libsource (lib "eagle-import") (part "C-USC1206"))
    )
    (comp (ref "C5")
      (value "0.1 uF")
      (footprint "eagle-import:C1206")
      (libsource (lib "eagle-import") (part "C-USC1206"))
    )
    (comp (ref "C7")
      (value "2.2 uF")
      (footprint "eagle-import:C1206")
      (libsource (lib "eagle-import") (part "C-USC1206"))
    )
    (comp (ref "C8")
      (value "2.2 uF")
      (footprint "eagle-import:C1206")
      (libsource (lib "eagle-import") (part "C-USC1206"))
    )
    (comp (ref "C11")
      (value "2.2 uF")
      (footprint "eagle-import:C1206")
      (libsource (lib "eagle-import") (part "C-USC1206"))
    )
    (comp (ref "C18")
      (value "2.2 uF")
      (footprint "eagle-import:C1206")
      (libsource (lib "eagle-import") (part "C-USC1206"))
    )
    (comp (ref "J21")
      (value "STRIP2")
      (footprint "eagle-import:STRIP2")
      (libsource (lib "eagle-import") (part "STRIP2"))
    )
    (comp (ref "J25")
      (value "STRIP2")
      (footprint "eagle-import:STRIP2")
      (libsource (lib "eagle-import") (part "STRIP2"))
    )
    (comp (ref "J35")
      (value "STRIP2")
      (footprint "eagle-import:STRIP2")
      (libsource (lib "eagle-import") (part "STRIP2"))
    )
    (comp (ref "J36")
      (value "STRIP2")
      (footprint "eagle-import:STRIP2")
      (libsource (lib "eagle-import") (part "STRIP2"))
    )
    (comp (ref "J37")
      (value "STRIP2")
      (footprint "eagle-import:STRIP2")
      (libsource (lib "eagle-import") (part "STRIP2"))
    )
    (comp (ref "J38")
      (value "STRIP2")
      (footprint "eagle-import:STRIP2")
      (libsource (lib "eagle-import") (part "STRIP2"))
    )
    (comp (ref "LED7")
      (value "LEDCHIPLED_1206")
      (footprint "eagle-import:CHIPLED_1206")
      (libsource (lib "eagle-import") (part "LEDCHIPLED_1206"))
    )
    (comp (ref "P1")
      (value "TH_PUSHBOTTON")
      (footprint "eagle-import:TH_PUSHBUTTON")
      (libsource (lib "eagle-import") (part "TH_PUSHBOTTON"))
    )
    (comp (ref "R32")
      (value "4.7K")
      (footprint "eagle-import:M1206")
      (libsource (lib "eagle-import") (part "R-US_M1206"))
    )
    (comp (ref "R33")
      (value "4.7K")
      (footprint "eagle-import:M1206")
      (libsource (lib "eagle-import") (part "R-US_M1206"))
    )
    (comp (ref "R34")
      (value "4.7k")
      (footprint "eagle-import:M1206")
      (libsource (lib "eagle-import") (part "R-US_M1206"))
    )
    (comp (ref "R35")
      (value "4.7k")
      (footprint "eagle-import:M1206")
      (libsource (lib "eagle-import") (part "R-US_M1206"))
    )
    (comp (ref "R36")
      (value "1K")
      (footprint "eagle-import:M1206")
      (libsource (lib "eagle-import") (part "R-US_M1206"))
    )
    (comp (ref "R37")
      (value "4.7k")
      (footprint "eagle-import:M1206")
      (libsource (lib "eagle-import") (part "R-US_M1206"))
    )
    (comp (ref "R38")
      (value "4.7k")
      (footprint "eagle-import:M1206")
      (libsource (lib "eagle-import") (part "R-US_M1206"))
    )
    (comp (ref "S17")
      (value "STRIP5")
      (footprint "eagle-import:STRIP5")
      (libsource (lib "eagle-import") (part "STRIP5"))
    )
    (comp (ref "S18")
      (value "STRIP5")
      (footprint "eagle-import:STRIP5")
      (libsource (lib "eagle-import") (part "STRIP5"))
    )
    (comp (ref "S20")
      (value "STRIP10")
      (footprint "eagle-import:STRIP10")
      (libsource (lib "eagle-import") (part "STRIP10"))
    )
    (comp (ref "S24")
      (value "STRIP10")
      (footprint "eagle-import:STRIP10")
      (libsource (lib "eagle-import") (part "STRIP10"))
    )
    (comp (ref "S53")
      (value "STRIP10")
      (footprint "eagle-import:STRIP10")
      (libsource (lib "eagle-import") (part "STRIP10"))
    )
    (comp (ref "S58")
      (value "STRIP10")
      (footprint "eagle-import:STRIP10")
      (libsource (lib "eagle-import") (part "STRIP10"))
    )
    (comp (ref "SV9")
      (value "MA03-1")
      (footprint "eagle-import:MA03-1")
      (libsource (lib "eagle-import") (part "MA03-1"))
    )
    (comp (ref "SV10")
      (value "MA03-1")
      (footprint "eagle-import:MA03-1")
      (libsource (lib "eagle-import") (part "MA03-1"))
    )
    (comp (ref "SV14")
      (value "MA07-2")
      (footprint "eagle-import:MA07-2")
      (libsource (lib "eagle-import") (part "MA07-2"))
    )
    (comp (ref "SV15")
      (value "MA08-2")
      (footprint "eagle-import:MA08-2")
      (libsource (lib "eagle-import") (part "MA08-2"))
    )
    (comp (ref "U6")
      (value "MAX4506")
      (footprint "eagle-import:SOIC-8")
      (libsource (lib "eagle-import") (part "MAX4506-SOIC8"))
    )
    (comp (ref "U8")
      (value "F28027")
      (footprint "eagle-import:DA38")
      (libsource (lib "eagle-import") (part "TMS320F28027DAS"))
    )
  )
  (nets
    (net (code "1") (name "+3.3V") (class "Default")
      (node (ref "C30") (pin "1") (pinfunction "1_1") (pintype "passive"))
      (node (ref "J27") (pin "P$2") (pinfunction "P$2_P$2") (pintype "bidirectional"))
      (node (ref "U9") (pin "P$4") (pinfunction "OUT_P$4") (pintype "bidirectional"))
      (node (ref "U9") (pin "P$5") (pinfunction "SENSE_P$5") (pintype "bidirectional"))
    )
    (net (code "2") (name "+5V") (class "Default")
      (node (ref "C34") (pin "1") (pinfunction "1_1") (pintype "passive"))
      (node (ref "C37") (pin "1") (pinfunction "1_1") (pintype "passive"))
      (node (ref "C38") (pin "1") (pinfunction "1_1") (pintype "passive"))
      (node (ref "C4") (pin "1") (pinfunction "1_1") (pintype "passive"))
      (node (ref "C6") (pin "1") (pinfunction "1_1") (pintype "passive"))
      (node (ref "DCDC5V") (pin "3") (pinfunction "3_3") (pintype "passive"))
      (node (ref "IC2") (pin "24") (pinfunction "VCC_24") (pintype "power_in"))
      (node (ref "J200") (pin "P$1") (pinfunction "P$1_P$1") (pintype "bidirectional"))
      (node (ref "J200") (pin "P$2") (pinfunction "P$2_P$2") (pintype "bidirectional"))
      (node (ref "J203") (pin "P$1") (pinfunction "P$1_P$1") (pintype "bidirectional"))
      (node (ref "J203") (pin "P$2") (pinfunction "P$2_P$2") (pintype "bidirectional"))
      (node (ref "J29") (pin "P$1") (pinfunction "P$1_P$1") (pintype "bidirectional"))
      (node (ref "QG2") (pin "14") (pinfunction "VCC_14") (pintype "power_in"))
      (node (ref "R26") (pin "2") (pinfunction "2_2") (pintype "passive"))
      (node (ref "S17") (pin "P$1") (pinfunction "P$1_P$1") (pintype "bidirectional"))
      (node (ref "S17") (pin "P$2") (pinfunction "P$2_P$2") (pintype "bidirectional"))
      (node (ref "S17") (pin "P$3") (pinfunction "P$3_P$3") (pintype "bidirectional"))
      (node (ref "S17") (pin "P$4") (pinfunction "P$4_P$4") (pintype "bidirectional"))
      (node (ref "S17") (pin "P$5") (pinfunction "P$5_P$5") (pintype "bidirectional"))
      (node (ref "S18") (pin "P$1") (pinfunction "P$1_P$1") (pintype "bidirectional"))
      (node (ref "S18") (pin "P$2") (pinfunction "P$2_P$2") (pintype "bidirectional"))
      (node (ref "S18") (pin "P$3") (pinfunction "P$3_P$3") (pintype "bidirectional"))
      (node (ref "S18") (pin "P$4") (pinfunction "P$4_P$4") (pintype "bidirectional"))
      (node (ref "S18") (pin "P$5") (pinfunction "P$5_P$5") (pintype "bidirectional"))
      (node (ref "SV2") (pin "1") (pinfunction "1_1") (pintype "passive"))
      (node (ref "SV2") (pin "2") (pinfunction "2_2") (pintype "passive"))
      (node (ref "SV2") (pin "3") (pinfunction "3_3") (pintype "passive"))
      (node (ref "SV2") (pin "4") (pinfunction "4_4") (pintype "passive"))
      (node (ref "SV23") (pin "7") (pinfunction "7_7") (pintype "passive"))
      (node (ref "SV23") (pin "8") (pinfunction "8_8") (pintype "passive"))
      (node (ref "U12") (pin "14") (pinfunction "VDD_14") (pintype "bidirectional"))
      (node (ref "U7") (pin "14") (pinfunction "VDD_14") (pintype "bidirectional"))
    )
    (net (code "3") (name "5V_FTDI") (class "Default")
      (node (ref "J28") (pin "P$1") (pinfunction "P$1_P$1") (pintype "bidirectional"))
      (node (ref "J29") (pin "P$2") (pinfunction "P$2_P$2") (pintype "bidirectional"))
      (node (ref "SV6") (pin "11") (pinfunction "11_11") (pintype "passive"))
      (node (ref "SV6") (pin "12") (pinfunction "12_12") (pintype "passive"))
    )
    (net (code "4") (name "28027_1_GPIO0") (class "Default")
      (node (ref "J21") (pin "P$1") (pinfunction "P$1_P$1") (pintype "bidirectional"))
      (node (ref "J21") (pin "P$2") (pinfunction "P$2_P$2") (pintype "bidirectional"))
      (node (ref "U8") (pin "37") (pinfunction "GPIO0/EPWM1A_37") (pintype "bidirectional"))
    )
    (net (code "5") (name "28027_1_GPIO1") (class "Default")
      (node (ref "J25") (pin "P$1") (pinfunction "P$1_P$1") (pintype "bidirectional"))
      (node (ref "J25") (pin "P$2") (pinfunction "P$2_P$2") (pintype "bidirectional"))
      (node (ref "U8") (pin "36") (pinfunction "GPIO1/EPWM1A_36") (pintype "bidirectional"))
    )
    (net (code "6") (name "28027_1_GPIO2") (class "Default")
      (node (ref "SV15") (pin "16") (pinfunction "16_16") (pintype "passive"))
      (node (ref "U8") (pin "5") (pinfunction "GPIO2/EPWM2A_5") (pintype "bidirectional"))
    )
    (net (code "7") (name "28027_1_GPIO3") (class "Default")
      (node (ref "SV15") (pin "14") (pinfunction "14_14") (pintype "passive"))
      (node (ref "U8") (pin "6") (pinfunction "GPIO3/EPWM2B_6") (pintype "bidirectional"))
    )
    (net (code "8") (name "28027_1_GPIO4") (class "Default")
      (node (ref "SV15") (pin "12") (pinfunction "12_12") (pintype "passive"))
      (node (ref "U8") (pin "7") (pinfunction "GPIO4/EPWM3A_7") (pintype "bidirectional"))
    )
    (net (code "9") (name "28027_1_GPIO5") (class "Default")
      (node (ref "SV15") (pin "10") (pinfunction "10_10") (pintype "passive"))
      (node (ref "U8") (pin "8") (pinfunction "GPIO5/EPWM3B_8") (pintype "bidirectional"))
    )
    (net (code "10") (name "28027_1_GPIO6") (class "Default")
      (node (ref "SV15") (pin "8") (pinfunction "8_8") (pintype "passive"))
      (node (ref "U8") (pin "9") (pinfunction "GPIO6/EPWM4A_9") (pintype "bidirectional"))
    )
    (net (code "11") (name "28027_1_GPIO7") (class "Default")
      (node (ref "SV15") (pin "6") (pinfunction "6_6") (pintype "passive"))
      (node (ref "U8") (pin "10") (pinfunction "GPIO7/EPWM4B_10") (pintype "bidirectional"))
    )
    (net (code "12") (name "28027_1_GPIO12") (class "Default")
      (node (ref "SV15") (pin "4") (pinfunction "4_4") (pintype "passive"))
      (node (ref "U8") (pin "13") (pinfunction "GPIO12/SCITXDA_13") (pintype "bidirectional"))
    )
    (net (code "13") (name "28027_1_GPIO34") (class "Default")
      (node (ref "LED7") (pin "C") (pinfunction "C_C") (pintype "passive"))
      (node (ref "R37") (pin "1") (pinfunction "1_1") (pintype "passive"))
      (node (ref "U8") (pin "27") (pinfunction "GPIO34_27") (pintype "bidirectional"))
    )
    (net (code "14") (name "28027_1_SCL") (class "Default")
      (node (ref "R34") (pin "2") (pinfunction "2_2") (pintype "passive"))
      (node (ref "SV15") (pin "3") (pinfunction "3_3") (pintype "passive"))
      (node (ref "U8") (pin "15") (pinfunction "GPIO29/SCITXDA_15") (pintype "bidirectional"))
    )
    (net (code "15") (name "28027_1_SDA") (class "Default")
      (node (ref "R35") (pin "2") (pinfunction "2_2") (pintype "passive"))
      (node (ref "SV15") (pin "5") (pinfunction "5_5") (pintype "passive"))
      (node (ref "U8") (pin "14") (pinfunction "GPIO28/SCIRXDA_14") (pintype "bidirectional"))
    )
    (net (code "16") (name "28027_1_SPICLKA") (class "Default")
      (node (ref "J38") (pin "P$1") (pinfunction "P$1_P$1") (pintype "bidirectional"))
      (node (ref "U8") (pin "32") (pinfunction "GPIO18/SPICLKA/SCITXDA_32") (pintype "bidirectional"))
    )
    (net (code "17") (name "28027_1_SPISIMOA") (class "Default")
      (node (ref "J36") (pin "P$1") (pinfunction "P$1_P$1") (pintype "bidirectional"))
      (node (ref "U8") (pin "35") (pinfunction "GPIO16/SPISIMOA_35") (pintype "bidirectional"))
    )
    (net (code "18") (name "28027_1_SPISOMIA") (class "Default")
      (node (ref "J35") (pin "P$1") (pinfunction "P$1_P$1") (pintype "bidirectional"))
      (node (ref "U8") (pin "34") (pinfunction "GPIO17/SPISOMIA_34") (pintype "bidirectional"))
    )
    (net (code "19") (name "28027_1_SPISTEA") (class "Default")
      (node (ref "J37") (pin "P$1") (pinfunction "P$1_P$1") (pintype "bidirectional"))
      (node (ref "J37") (pin "P$2") (pinfunction "P$2_P$2") (pintype "bidirectional"))
      (node (ref "U8") (pin "33") (pinfunction "GPIO19//SPISTEA/SCIRXDA_33") (pintype "bidirectional"))
    )
    (net (code "20") (name "28027_2_GPIO0") (class "Default")
      (node (ref "J198") (pin "P$1") (pinfunction "P$1_P$1") (pintype "bidirectional"))
      (node (ref "J198") (pin "P$2") (pinfunction "P$2_P$2") (pintype "bidirectional"))
      (node (ref "S13") (pin "P$1") (pinfunction "P$1_P$1") (pintype "bidirectional"))
      (node (ref "S13") (pin "P$2") (pinfunction "P$2_P$2") (pintype "bidirectional"))
      (node (ref "S13") (pin "P$3") (pinfunction "P$3_P$3") (pintype "bidirectional"))
      (node (ref "S13") (pin "P$4") (pinfunction "P$4_P$4") (pintype "bidirectional"))
      (node (ref "S13") (pin "P$5") (pinfunction "P$5_P$5") (pintype "bidirectional"))
      (node (ref "U11") (pin "37") (pinfunction "GPIO0/EPWM1A_37") (pintype "bidirectional"))
    )
    (net (code "21") (name "28027_2_GPIO1") (class "Default")
      (node (ref "J199") (pin "P$1") (pinfunction "P$1_P$1") (pintype "bidirectional"))
      (node (ref "J199") (pin "P$2") (pinfunction "P$2_P$2") (pintype "bidirectional"))
      (node (ref "S14") (pin "P$1") (pinfunction "P$1_P$1") (pintype "bidirectional"))
      (node (ref "S14") (pin "P$2") (pinfunction "P$2_P$2") (pintype "bidirectional"))
      (node (ref "S14") (pin "P$3") (pinfunction "P$3_P$3") (pintype "bidirectional"))
      (node (ref "S14") (pin "P$4") (pinfunction "P$4_P$4") (pintype "bidirectional"))
      (node (ref "S14") (pin "P$5") (pinfunction "P$5_P$5") (pintype "bidirectional"))
      (node (ref "U11") (pin "36") (pinfunction "GPIO1/EPWM1A_36") (pintype "bidirectional"))
    )
    (net (code "22") (name "28027_2_GPIO2") (class "Default")
      (node (ref "J84") (pin "P$1") (pinfunction "P$1_P$1") (pintype "bidirectional"))
      (node (ref "J84") (pin "P$2") (pinfunction "P$2_P$2") (pintype "bidirectional"))
      (node (ref "S2") (pin "P$1") (pinfunction "P$1_P$1") (pintype "bidirectional"))
      (node (ref "S2") (pin "P$2") (pinfunction "P$2_P$2") (pintype "bidirectional"))
      (node (ref "S2") (pin "P$3") (pinfunction "P$3_P$3") (pintype "bidirectional"))
      (node (ref "S2") (pin "P$4") (pinfunction "P$4_P$4") (pintype "bidirectional"))
      (node (ref "S2") (pin "P$5") (pinfunction "P$5_P$5") (pintype "bidirectional"))
      (node (ref "U11") (pin "5") (pinfunction "GPIO2/EPWM2A_5") (pintype "bidirectional"))
    )
    (net (code "23") (name "28027_2_GPIO3") (class "Default")
      (node (ref "J86") (pin "P$1") (pinfunction "P$1_P$1") (pintype "bidirectional"))
      (node (ref "J86") (pin "P$2") (pinfunction "P$2_P$2") (pintype "bidirectional"))
      (node (ref "S3") (pin "P$1") (pinfunction "P$1_P$1") (pintype "bidirectional"))
      (node (ref "S3") (pin "P$2") (pinfunction "P$2_P$2") (pintype "bidirectional"))
      (node (ref "S3") (pin "P$3") (pinfunction "P$3_P$3") (pintype "bidirectional"))
      (node (ref "S3") (pin "P$4") (pinfunction "P$4_P$4") (pintype "bidirectional"))
      (node (ref "S3") (pin "P$5") (pinfunction "P$5_P$5") (pintype "bidirectional"))
      (node (ref "U11") (pin "6") (pinfunction "GPIO3/EPWM2B_6") (pintype "bidirectional"))
    )
    (net (code "24") (name "28027_2_GPIO4") (class "Default")
      (node (ref "IC2") (pin "17") (pinfunction "B2_17") (pintype "bidirectional"))
      (node (ref "IC3") (pin "13") (pinfunction "I_13") (pintype "input"))
      (node (ref "J201") (pin "P$1") (pinfunction "P$1_P$1") (pintype "bidirectional"))
      (node (ref "J201") (pin "P$2") (pinfunction "P$2_P$2") (pintype "bidirectional"))
      (node (ref "S4") (pin "P$1") (pinfunction "P$1_P$1") (pintype "bidirectional"))
      (node (ref "S4") (pin "P$2") (pinfunction "P$2_P$2") (pintype "bidirectional"))
      (node (ref "S4") (pin "P$3") (pinfunction "P$3_P$3") (pintype "bidirectional"))
      (node (ref "S4") (pin "P$4") (pinfunction "P$4_P$4") (pintype "bidirectional"))
      (node (ref "S4") (pin "P$5") (pinfunction "P$5_P$5") (pintype "bidirectional"))
      (node (ref "U11") (pin "7") (pinfunction "GPIO4/EPWM3A_7") (pintype "bidirectional"))
    )
    (net (code "25") (name "28027_2_GPIO5") (class "Default")
      (node (ref "IC3") (pin "3") (pinfunction "I_3") (pintype "input"))
      (node (ref "J26") (pin "P$1") (pinfunction "P$1_P$1") (pintype "bidirectional"))
      (node (ref "J26") (pin "P$2") (pinfunction "P$2_P$2") (pintype "bidirectional"))
      (node (ref "S5") (pin "P$1") (pinfunction "P$1_P$1") (pintype "bidirectional"))
      (node (ref "S5") (pin "P$2") (pinfunction "P$2_P$2") (pintype "bidirectional"))
      (node (ref "S5") (pin "P$3") (pinfunction "P$3_P$3") (pintype "bidirectional"))
      (node (ref "S5") (pin "P$4") (pinfunction "P$4_P$4") (pintype "bidirectional"))
      (node (ref "S5") (pin "P$5") (pinfunction "P$5_P$5") (pintype "bidirectional"))
      (node (ref "U11") (pin "8") (pinfunction "GPIO5/EPWM3B_8") (pintype "bidirectional"))
    )
    (net (code "26") (name "28027_2_GPIO6") (class "Default")
      (node (ref "IC2") (pin "15") (pinfunction "B1_15") (pintype "bidirectional"))
      (node (ref "J202") (pin "P$1") (pinfunction "P$1_P$1") (pintype "bidirectional"))
      (node (ref "J202") (pin "P$2") (pinfunction "P$2_P$2") (pintype "bidirectional"))
      (node (ref "S6") (pin "P$1") (pinfunction "P$1_P$1") (pintype "bidirectional"))
      (node (ref "S6") (pin "P$2") (pinfunction "P$2_P$2") (pintype "bidirectional"))
      (node (ref "S6") (pin "P$3") (pinfunction "P$3_P$3") (pintype "bidirectional"))
      (node (ref "S6") (pin "P$4") (pinfunction "P$4_P$4") (pintype "bidirectional"))
      (node (ref "S6") (pin "P$5") (pinfunction "P$5_P$5") (pintype "bidirectional"))
      (node (ref "U11") (pin "9") (pinfunction "GPIO6/EPWM4A_9") (pintype "bidirectional"))
    )
    (net (code "27") (name "28027_2_GPIO7") (class "Default")
      (node (ref "J85") (pin "P$1") (pinfunction "P$1_P$1") (pintype "bidirectional"))
      (node (ref "J85") (pin "P$2") (pinfunction "P$2_P$2") (pintype "bidirectional"))
      (node (ref "S7") (pin "P$1") (pinfunction "P$1_P$1") (pintype "bidirectional"))
      (node (ref "S7") (pin "P$2") (pinfunction "P$2_P$2") (pintype "bidirectional"))
      (node (ref "S7") (pin "P$3") (pinfunction "P$3_P$3") (pintype "bidirectional"))
      (node (ref "S7") (pin "P$4") (pinfunction "P$4_P$4") (pintype "bidirectional"))
      (node (ref "S7") (pin "P$5") (pinfunction "P$5_P$5") (pintype "bidirectional"))
      (node (ref "U11") (pin "10") (pinfunction "GPIO7/EPWM4B_10") (pintype "bidirectional"))
    )
    (net (code "28") (name "28027_2_GPIO12") (class "Default")
      (node (ref "J87") (pin "P$1") (pinfunction "P$1_P$1") (pintype "bidirectional"))
      (node (ref "J87") (pin "P$2") (pinfunction "P$2_P$2") (pintype "bidirectional"))
      (node (ref "S8") (pin "P$1") (pinfunction "P$1_P$1") (pintype "bidirectional"))
      (node (ref "S8") (pin "P$2") (pinfunction "P$2_P$2") (pintype "bidirectional"))
      (node (ref "S8") (pin "P$3") (pinfunction "P$3_P$3") (pintype "bidirectional"))
      (node (ref "S8") (pin "P$4") (pinfunction "P$4_P$4") (pintype "bidirectional"))
      (node (ref "S8") (pin "P$5") (pinfunction "P$5_P$5") (pintype "bidirectional"))
      (node (ref "U11") (pin "13") (pinfunction "GPIO12/SCITXDA_13") (pintype "bidirectional"))
    )
    (net (code "29") (name "28027_2_GPIO34") (class "Default")
      (node (ref "IC3") (pin "1") (pinfunction "I_1") (pintype "input"))
      (node (ref "LED18") (pin "C") (pinfunction "C_C") (pintype "passive"))
      (node (ref "R49") (pin "1") (pinfunction "1_1") (pintype "passive"))
      (node (ref "S26") (pin "P$1") (pinfunction "P$1_P$1") (pintype "bidirectional"))
      (node (ref "S26") (pin "P$2") (pinfunction "P$2_P$2") (pintype "bidirectional"))
      (node (ref "S26") (pin "P$3") (pinfunction "P$3_P$3") (pintype "bidirectional"))
      (node (ref "S26") (pin "P$4") (pinfunction "P$4_P$4") (pintype "bidirectional"))
      (node (ref "S26") (pin "P$5") (pinfunction "P$5_P$5") (pintype "bidirectional"))
      (node (ref "U11") (pin "27") (pinfunction "GPIO34_27") (pintype "bidirectional"))
    )
    (net (code "30") (name "28027_2_SCL") (class "Default")
      (node (ref "J209") (pin "P$1") (pinfunction "P$1_P$1") (pintype "bidirectional"))
      (node (ref "J209") (pin "P$2") (pinfunction "P$2_P$2") (pintype "bidirectional"))
      (node (ref "J31") (pin "P$1") (pinfunction "P$1_P$1") (pintype "bidirectional"))
      (node (ref "R10") (pin "2") (pinfunction "2_2") (pintype "passive"))
      (node (ref "R46") (pin "2") (pinfunction "2_2") (pintype "passive"))
      (node (ref "S10") (pin "P$1") (pinfunction "P$1_P$1") (pintype "bidirectional"))
      (node (ref "S10") (pin "P$2") (pinfunction "P$2_P$2") (pintype "bidirectional"))
      (node (ref "S10") (pin "P$3") (pinfunction "P$3_P$3") (pintype "bidirectional"))
      (node (ref "S10") (pin "P$4") (pinfunction "P$4_P$4") (pintype "bidirectional"))
      (node (ref "S10") (pin "P$5") (pinfunction "P$5_P$5") (pintype "bidirectional"))
      (node (ref "SV13") (pin "8") (pinfunction "8_8") (pintype "passive"))
      (node (ref "U11") (pin "15") (pinfunction "GPIO29/SCITXDA_15") (pintype "bidirectional"))
    )
    (net (code "31") (name "28027_2_SDA") (class "Default")
      (node (ref "J208") (pin "P$1") (pinfunction "P$1_P$1") (pintype "bidirectional"))
      (node (ref "J208") (pin "P$2") (pinfunction "P$2_P$2") (pintype "bidirectional"))
      (node (ref "J32") (pin "P$1") (pinfunction "P$1_P$1") (pintype "bidirectional"))
      (node (ref "R47") (pin "2") (pinfunction "2_2") (pintype "passive"))
      (node (ref "R9") (pin "2") (pinfunction "2_2") (pintype "passive"))
      (node (ref "S9") (pin "P$1") (pinfunction "P$1_P$1") (pintype "bidirectional"))
      (node (ref "S9") (pin "P$2") (pinfunction "P$2_P$2") (pintype "bidirectional"))
      (node (ref "S9") (pin "P$3") (pinfunction "P$3_P$3") (pintype "bidirectional"))
      (node (ref "S9") (pin "P$4") (pinfunction "P$4_P$4") (pintype "bidirectional"))
      (node (ref "S9") (pin "P$5") (pinfunction "P$5_P$5") (pintype "bidirectional"))
      (node (ref "SV13") (pin "1") (pinfunction "1_1") (pintype "passive"))
      (node (ref "U11") (pin "14") (pinfunction "GPIO28/SCIRXDA_14") (pintype "bidirectional"))
    )
    (net (code "32") (name "28027_2_SPICLKA") (class "Default")
      (node (ref "IC2") (pin "23") (pinfunction "B5_23") (pintype "bidirectional"))
      (node (ref "J206") (pin "P$1") (pinfunction "P$1_P$1") (pintype "bidirectional"))
      (node (ref "J206") (pin "P$2") (pinfunction "P$2_P$2") (pintype "bidirectional"))
      (node (ref "J38") (pin "P$2") (pinfunction "P$2_P$2") (pintype "bidirectional"))
      (node (ref "S21") (pin "P$1") (pinfunction "P$1_P$1") (pintype "bidirectional"))
      (node (ref "S21") (pin "P$2") (pinfunction "P$2_P$2") (pintype "bidirectional"))
      (node (ref "S21") (pin "P$3") (pinfunction "P$3_P$3") (pintype "bidirectional"))
      (node (ref "S21") (pin "P$4") (pinfunction "P$4_P$4") (pintype "bidirectional"))
      (node (ref "S21") (pin "P$5") (pinfunction "P$5_P$5") (pintype "bidirectional"))
      (node (ref "U11") (pin "32") (pinfunction "GPIO18/SPICLKA/SCITXDA_32") (pintype "bidirectional"))
    )
    (net (code "33") (name "28027_2_SPISIMOA") (class "Default")
      (node (ref "IC2") (pin "19") (pinfunction "B3_19") (pintype "bidirectional"))
      (node (ref "J204") (pin "P$1") (pinfunction "P$1_P$1") (pintype "bidirectional"))
      (node (ref "J204") (pin "P$2") (pinfunction "P$2_P$2") (pintype "bidirectional"))
      (node (ref "J36") (pin "P$2") (pinfunction "P$2_P$2") (pintype "bidirectional"))
      (node (ref "S15") (pin "P$1") (pinfunction "P$1_P$1") (pintype "bidirectional"))
      (node (ref "S15") (pin "P$2") (pinfunction "P$2_P$2") (pintype "bidirectional"))
      (node (ref "S15") (pin "P$3") (pinfunction "P$3_P$3") (pintype "bidirectional"))
      (node (ref "S15") (pin "P$4") (pinfunction "P$4_P$4") (pintype "bidirectional"))
      (node (ref "S15") (pin "P$5") (pinfunction "P$5_P$5") (pintype "bidirectional"))
      (node (ref "U11") (pin "35") (pinfunction "GPIO16/SPISIMOA_35") (pintype "bidirectional"))
    )
    (net (code "34") (name "28027_2_SPISOMIA") (class "Default")
      (node (ref "IC2") (pin "21") (pinfunction "B4_21") (pintype "bidirectional"))
      (node (ref "J205") (pin "P$1") (pinfunction "P$1_P$1") (pintype "bidirectional"))
      (node (ref "J205") (pin "P$2") (pinfunction "P$2_P$2") (pintype "bidirectional"))
      (node (ref "J35") (pin "P$2") (pinfunction "P$2_P$2") (pintype "bidirectional"))
      (node (ref "S16") (pin "P$1") (pinfunction "P$1_P$1") (pintype "bidirectional"))
      (node (ref "S16") (pin "P$2") (pinfunction "P$2_P$2") (pintype "bidirectional"))
      (node (ref "S16") (pin "P$3") (pinfunction "P$3_P$3") (pintype "bidirectional"))
      (node (ref "S16") (pin "P$4") (pinfunction "P$4_P$4") (pintype "bidirectional"))
      (node (ref "S16") (pin "P$5") (pinfunction "P$5_P$5") (pintype "bidirectional"))
      (node (ref "U11") (pin "34") (pinfunction "GPIO17/SPISOMIA_34") (pintype "bidirectional"))
    )
    (net (code "35") (name "28027_2_SPISTEA") (class "Default")
      (node (ref "J207") (pin "P$1") (pinfunction "P$1_P$1") (pintype "bidirectional"))
      (node (ref "J207") (pin "P$2") (pinfunction "P$2_P$2") (pintype "bidirectional"))
      (node (ref "S19") (pin "P$1") (pinfunction "P$1_P$1") (pintype "bidirectional"))
      (node (ref "S19") (pin "P$2") (pinfunction "P$2_P$2") (pintype "bidirectional"))
      (node (ref "S19") (pin "P$3") (pinfunction "P$3_P$3") (pintype "bidirectional"))
      (node (ref "S19") (pin "P$4") (pinfunction "P$4_P$4") (pintype "bidirectional"))
      (node (ref "S19") (pin "P$5") (pinfunction "P$5_P$5") (pintype "bidirectional"))
      (node (ref "U11") (pin "33") (pinfunction "GPIO19//SPISTEA/SCIRXDA_33") (pintype "bidirectional"))
    )
    (net (code "36") (name "A4973EN") (class "Default")
      (node (ref "S1") (pin "P$2") (pinfunction "P2_P$2") (pintype "bidirectional"))
      (node (ref "U1") (pin "8") (pinfunction "~{ENABLE}_8") (pintype "bidirectional"))
      (node (ref "U5") (pin "8") (pinfunction "~{ENABLE}_8") (pintype "bidirectional"))
    )
    (net (code "37") (name "ADCA0") (class "Default")
      (node (ref "SV15") (pin "7") (pinfunction "7_7") (pintype "passive"))
      (node (ref "U8") (pin "21") (pinfunction "ADCINA0/VREFHI_21") (pintype "bidirectional"))
    )
    (net (code "38") (name "ADCA0_2") (class "Default")
      (node (ref "S23") (pin "P$1") (pinfunction "P$1_P$1") (pintype "bidirectional"))
      (node (ref "S23") (pin "P$2") (pinfunction "P$2_P$2") (pintype "bidirectional"))
      (node (ref "S23") (pin "P$3") (pinfunction "P$3_P$3") (pintype "bidirectional"))
      (node (ref "S23") (pin "P$4") (pinfunction "P$4_P$4") (pintype "bidirectional"))
      (node (ref "S23") (pin "P$5") (pinfunction "P$5_P$5") (pintype "bidirectional"))
      (node (ref "SV12") (pin "4") (pinfunction "4_4") (pintype "passive"))
      (node (ref "U11") (pin "21") (pinfunction "ADCINA0/VREFHI_21") (pintype "bidirectional"))
    )
    (net (code "39") (name "ADCA2") (class "Default")
      (node (ref "SV15") (pin "9") (pinfunction "9_9") (pintype "passive"))
      (node (ref "U8") (pin "20") (pinfunction "ADCINA2/AIO2_20") (pintype "bidirectional"))
    )
    (net (code "40") (name "ADCA2_2") (class "Default")
      (node (ref "S28") (pin "P$1") (pinfunction "P$1_P$1") (pintype "bidirectional"))
      (node (ref "S28") (pin "P$2") (pinfunction "P$2_P$2") (pintype "bidirectional"))
      (node (ref "S28") (pin "P$3") (pinfunction "P$3_P$3") (pintype "bidirectional"))
      (node (ref "S28") (pin "P$4") (pinfunction "P$4_P$4") (pintype "bidirectional"))
      (node (ref "S28") (pin "P$5") (pinfunction "P$5_P$5") (pintype "bidirectional"))
      (node (ref "SV11") (pin "3") (pinfunction "3_3") (pintype "passive"))
      (node (ref "U11") (pin "20") (pinfunction "ADCINA2/AIO2_20") (pintype "bidirectional"))
    )
    (net (code "41") (name "ADCA4") (class "Default")
      (node (ref "SV15") (pin "13") (pinfunction "13_13") (pintype "passive"))
      (node (ref "U8") (pin "19") (pinfunction "ADCINA4/AIO4_19") (pintype "bidirectional"))
    )
    (net (code "42") (name "ADCA4_2") (class "Default")
      (node (ref "S12") (pin "P$1") (pinfunction "P$1_P$1") (pintype "bidirectional"))
      (node (ref "S12") (pin "P$2") (pinfunction "P$2_P$2") (pintype "bidirectional"))
      (node (ref "S12") (pin "P$3") (pinfunction "P$3_P$3") (pintype "bidirectional"))
      (node (ref "S12") (pin "P$4") (pinfunction "P$4_P$4") (pintype "bidirectional"))
      (node (ref "S12") (pin "P$5") (pinfunction "P$5_P$5") (pintype "bidirectional"))
      (node (ref "SV11") (pin "4") (pinfunction "4_4") (pintype "passive"))
      (node (ref "U11") (pin "19") (pinfunction "ADCINA4/AIO4_19") (pintype "bidirectional"))
    )
    (net (code "43") (name "ADCA6") (class "Default")
      (node (ref "SV15") (pin "2") (pinfunction "2_2") (pintype "passive"))
      (node (ref "U8") (pin "18") (pinfunction "ADCINA6/AIO6_18") (pintype "bidirectional"))
    )
    (net (code "44") (name "ADCA6_2") (class "Default")
      (node (ref "J71") (pin "P$1") (pinfunction "P$1_P$1") (pintype "bidirectional"))
      (node (ref "J71") (pin "P$2") (pinfunction "P$2_P$2") (pintype "bidirectional"))
      (node (ref "R13") (pin "2") (pinfunction "2_2") (pintype "passive"))
      (node (ref "S11") (pin "P$1") (pinfunction "P$1_P$1") (pintype "bidirectional"))
      (node (ref "S11") (pin "P$2") (pinfunction "P$2_P$2") (pintype "bidirectional"))
      (node (ref "S11") (pin "P$3") (pinfunction "P$3_P$3") (pintype "bidirectional"))
      (node (ref "S11") (pin "P$4") (pinfunction "P$4_P$4") (pintype "bidirectional"))
      (node (ref "S11") (pin "P$5") (pinfunction "P$5_P$5") (pintype "bidirectional"))
      (node (ref "U11") (pin "18") (pinfunction "ADCINA6/AIO6_18") (pintype "bidirectional"))
    )
    (net (code "45") (name "ADCB2") (class "Default")
      (node (ref "SV15") (pin "11") (pinfunction "11_11") (pintype "passive"))
      (node (ref "U8") (pin "24") (pinfunction "ADCINB2/AIO10_24") (pintype "bidirectional"))
    )
    (net (code "46") (name "ADCB2_2") (class "Default")
      (node (ref "J73") (pin "P$1") (pinfunction "P$1_P$1") (pintype "bidirectional"))
      (node (ref "J73") (pin "P$2") (pinfunction "P$2_P$2") (pintype "bidirectional"))
      (node (ref "R12") (pin "2") (pinfunction "2_2") (pintype "passive"))
      (node (ref "S27") (pin "P$1") (pinfunction "P$1_P$1") (pintype "bidirectional"))
      (node (ref "S27") (pin "P$2") (pinfunction "P$2_P$2") (pintype "bidirectional"))
      (node (ref "S27") (pin "P$3") (pinfunction "P$3_P$3") (pintype "bidirectional"))
      (node (ref "S27") (pin "P$4") (pinfunction "P$4_P$4") (pintype "bidirectional"))
      (node (ref "S27") (pin "P$5") (pinfunction "P$5_P$5") (pintype "bidirectional"))
      (node (ref "SV11") (pin "5") (pinfunction "5_5") (pintype "passive"))
      (node (ref "U11") (pin "24") (pinfunction "ADCINB2/AIO10_24") (pintype "bidirectional"))
    )
    (net (code "47") (name "ADCB4") (class "Default")
      (node (ref "SV15") (pin "15") (pinfunction "15_15") (pintype "passive"))
      (node (ref "U8") (pin "25") (pinfunction "ADCINB4/AIO12_25") (pintype "bidirectional"))
    )
    (net (code "48") (name "ADCB4_2") (class "Default")
      (node (ref "IC3") (pin "5") (pinfunction "I_5") (pintype "input"))
      (node (ref "S25") (pin "P$1") (pinfunction "P$1_P$1") (pintype "bidirectional"))
      (node (ref "S25") (pin "P$2") (pinfunction "P$2_P$2") (pintype "bidirectional"))
      (node (ref "S25") (pin "P$3") (pinfunction "P$3_P$3") (pintype "bidirectional"))
      (node (ref "S25") (pin "P$4") (pinfunction "P$4_P$4") (pintype "bidirectional"))
      (node (ref "S25") (pin "P$5") (pinfunction "P$5_P$5") (pintype "bidirectional"))
      (node (ref "SV13") (pin "5") (pinfunction "5_5") (pintype "passive"))
      (node (ref "U11") (pin "25") (pinfunction "ADCINB4/AIO12_25") (pintype "bidirectional"))
    )
    (net (code "49") (name "ADCB6") (class "Default")
      (node (ref "U8") (pin "26") (pinfunction "ADCINB6/AIO14_26") (pintype "bidirectional"))
    )
    (net (code "50") (name "ADCB6_2") (class "Default")
      (node (ref "IC3") (pin "9") (pinfunction "I_9") (pintype "input"))
      (node (ref "S22") (pin "P$1") (pinfunction "P$1_P$1") (pintype "bidirectional"))
      (node (ref "S22") (pin "P$2") (pinfunction "P$2_P$2") (pintype "bidirectional"))
      (node (ref "S22") (pin "P$3") (pinfunction "P$3_P$3") (pintype "bidirectional"))
      (node (ref "S22") (pin "P$4") (pinfunction "P$4_P$4") (pintype "bidirectional"))
      (node (ref "S22") (pin "P$5") (pinfunction "P$5_P$5") (pintype "bidirectional"))
      (node (ref "U11") (pin "26") (pinfunction "ADCINB6/AIO14_26") (pintype "bidirectional"))
    )
    (net (code "51") (name "DRV1_DIR") (class "Default")
      (node (ref "J80") (pin "P$1") (pinfunction "P$1_P$1") (pintype "bidirectional"))
      (node (ref "J80") (pin "P$2") (pinfunction "P$2_P$2") (pintype "bidirectional"))
      (node (ref "U2") (pin "P$2") (pinfunction "PH/IN2_P$2") (pintype "bidirectional"))
    )
    (net (code "52") (name "DRV1_M+") (class "Default")
      (node (ref "SV7") (pin "1") (pinfunction "1_1") (pintype "passive"))
      (node (ref "SV7") (pin "3") (pinfunction "3_3") (pintype "passive"))
      (node (ref "SV7") (pin "5") (pinfunction "5_5") (pintype "passive"))
      (node (ref "U2") (pin "P$8") (pinfunction "OUT1_P$8") (pintype "bidirectional"))
    )
    (net (code "53") (name "DRV1_M-") (class "Default")
      (node (ref "SV7") (pin "2") (pinfunction "2_2") (pintype "passive"))
      (node (ref "SV7") (pin "4") (pinfunction "4_4") (pintype "passive"))
      (node (ref "SV7") (pin "6") (pinfunction "6_6") (pintype "passive"))
      (node (ref "U2") (pin "P$10") (pinfunction "OUT2_P$10") (pintype "bidirectional"))
    )
    (net (code "54") (name "DRV1_PWM") (class "Default")
      (node (ref "J79") (pin "P$1") (pinfunction "P$1_P$1") (pintype "bidirectional"))
      (node (ref "J79") (pin "P$2") (pinfunction "P$2_P$2") (pintype "bidirectional"))
      (node (ref "U2") (pin "P$1") (pinfunction "EN/IN1_P$1") (pintype "bidirectional"))
    )
    (net (code "55") (name "DRV2_DIR") (class "Default")
      (node (ref "J83") (pin "P$1") (pinfunction "P$1_P$1") (pintype "bidirectional"))
      (node (ref "J83") (pin "P$2") (pinfunction "P$2_P$2") (pintype "bidirectional"))
      (node (ref "U4") (pin "P$2") (pinfunction "PH/IN2_P$2") (pintype "bidirectional"))
    )
    (net (code "56") (name "DRV2_M+") (class "Default")
      (node (ref "SV8") (pin "1") (pinfunction "1_1") (pintype "passive"))
      (node (ref "SV8") (pin "3") (pinfunction "3_3") (pintype "passive"))
      (node (ref "SV8") (pin "5") (pinfunction "5_5") (pintype "passive"))
      (node (ref "U4") (pin "P$8") (pinfunction "OUT1_P$8") (pintype "bidirectional"))
    )
    (net (code "57") (name "DRV2_M-") (class "Default")
      (node (ref "SV8") (pin "2") (pinfunction "2_2") (pintype "passive"))
      (node (ref "SV8") (pin "4") (pinfunction "4_4") (pintype "passive"))
      (node (ref "SV8") (pin "6") (pinfunction "6_6") (pintype "passive"))
      (node (ref "U4") (pin "P$10") (pinfunction "OUT2_P$10") (pintype "bidirectional"))
    )
    (net (code "58") (name "DRV2_PWM") (class "Default")
      (node (ref "J82") (pin "P$1") (pinfunction "P$1_P$1") (pintype "bidirectional"))
      (node (ref "J82") (pin "P$2") (pinfunction "P$2_P$2") (pintype "bidirectional"))
      (node (ref "U4") (pin "P$1") (pinfunction "EN/IN1_P$1") (pintype "bidirectional"))
    )
    (net (code "59") (name "DTR") (class "Default")
      (node (ref "J30") (pin "P$1") (pinfunction "P$1_P$1") (pintype "bidirectional"))
      (node (ref "SV17") (pin "3") (pinfunction "3_3") (pintype "passive"))
      (node (ref "SV17") (pin "4") (pinfunction "4_4") (pintype "passive"))
    )
    (net (code "60") (name "GND") (class "Default")
      (node (ref "3V3") (pin "C") (pinfunction "C_C") (pintype "passive"))
      (node (ref "5V") (pin "C") (pinfunction "C_C") (pintype "passive"))
      (node (ref "B1") (pin "P$2") (pinfunction "P$2_P$2") (pintype "bidirectional"))
      (node (ref "B2") (pin "P$2") (pinfunction "BAT-_P$2") (pintype "bidirectional"))
      (node (ref "B3") (pin "P$1") (pinfunction "P1_P$1") (pintype "bidirectional"))
      (node (ref "C1") (pin "-") (pinfunction "-_-") (pintype "passive"))
      (node (ref "C10") (pin "2") (pinfunction "2_2") (pintype "passive"))
      (node (ref "C11") (pin "2") (pinfunction "2_2") (pintype "passive"))
      (node (ref "C12") (pin "-") (pinfunction "-_-") (pintype "passive"))
      (node (ref "C13") (pin "-") (pinfunction "-_-") (pintype "passive"))
      (node (ref "C14") (pin "2") (pinfunction "2_2") (pintype "passive"))
      (node (ref "C15") (pin "-") (pinfunction "-_-") (pintype "passive"))
      (node (ref "C16") (pin "2") (pinfunction "2_2") (pintype "passive"))
      (node (ref "C18") (pin "2") (pinfunction "2_2") (pintype "passive"))
      (node (ref "C2") (pin "2") (pinfunction "2_2") (pintype "passive"))
      (node (ref "C20") (pin "-") (pinfunction "-_-") (pintype "passive"))
      (node (ref "C21") (pin "2") (pinfunction "2_2") (pintype "passive"))
      (node (ref "C22") (pin "2") (pinfunction "2_2") (pintype "passive"))
      (node (ref "C25") (pin "-") (pinfunction "-_-") (pintype "passive"))
      (node (ref "C26") (pin "2") (pinfunction "2_2") (pintype "passive"))
      (node (ref "C27") (pin "-") (pinfunction "-_-") (pintype "passive"))
      (node (ref "C28") (pin "-") (pinfunction "-_-") (pintype "passive"))
      (node (ref "C29") (pin "2") (pinfunction "2_2") (pintype "passive"))
      (node (ref "C3") (pin "2") (pinfunction "2_2") (pintype "passive"))
      (node (ref "C30") (pin "2") (pinfunction "2_2") (pintype "passive"))
      (node (ref "C32") (pin "2") (pinfunction "2_2") (pintype "passive"))
      (node (ref "C33") (pin "2") (pinfunction "2_2") (pintype "passive"))
      (node (ref "C34") (pin "2") (pinfunction "2_2") (pintype "passive"))
      (node (ref "C37") (pin "2") (pinfunction "2_2") (pintype "passive"))
      (node (ref "C38") (pin "2") (pinfunction "2_2") (pintype "passive"))
      (node (ref "C4") (pin "2") (pinfunction "2_2") (pintype "passive"))
      (node (ref "C5") (pin "2") (pinfunction "2_2") (pintype "passive"))
      (node (ref "C6") (pin "2") (pinfunction "2_2") (pintype "passive"))
      (node (ref "C7") (pin "2") (pinfunction "2_2") (pintype "passive"))
      (node (ref "C8") (pin "2") (pinfunction "2_2") (pintype "passive"))
      (node (ref "C9") (pin "2") (pinfunction "2_2") (pintype "passive"))
      (node (ref "DCDC3.3V") (pin "2") (pinfunction "2_2") (pintype "passive"))
      (node (ref "DCDC5V") (pin "2") (pinfunction "2_2") (pintype "passive"))
      (node (ref "G1") (pin "-") (pinfunction "-_-") (pintype "passive"))
      (node (ref "IC2") (pin "1") (pinfunction "G_1") (pintype "input"))
      (node (ref "IC2") (pin "12") (pinfunction "GND_12") (pintype "power_in"))
      (node (ref "IC2") (pin "13") (pinfunction "G_13") (pintype "input"))
      (node (ref "IC3") (pin "7") (pinfunction "GND_7") (pintype "power_in"))
      (node (ref "J124") (pin "P$1") (pinfunction "P$1_P$1") (pintype "bidirectional"))
      (node (ref "J124") (pin "P$2") (pinfunction "P$2_P$2") (pintype "bidirectional"))
      (node (ref "J124") (pin "P$3") (pinfunction "P$3_P$3") (pintype "bidirectional"))
      (node (ref "J5") (pin "2") (pinfunction "2_2") (pintype "passive"))
      (node (ref "J5") (pin "3") (pinfunction "3_3") (pintype "passive"))
      (node (ref "J7") (pin "P$1") (pinfunction "P$1_P$1") (pintype "bidirectional"))
      (node (ref "J7") (pin "P$2") (pinfunction "P$2_P$2") (pintype "bidirectional"))
      (node (ref "J70") (pin "P$1") (pinfunction "P$1_P$1") (pintype "bidirectional"))
      (node (ref "J70") (pin "P$2") (pinfunction "P$2_P$2") (pintype "bidirectional"))
      (node (ref "J72") (pin "P$1") (pinfunction "P$1_P$1") (pintype "bidirectional"))
      (node (ref "J72") (pin "P$2") (pinfunction "P$2_P$2") (pintype "bidirectional"))
      (node (ref "JP2") (pin "2") (pinfunction "2_2") (pintype "passive"))
      (node (ref "JP3") (pin "2") (pinfunction "2_2") (pintype "passive"))
      (node (ref "LED6") (pin "C") (pinfunction "C_C") (pintype "passive"))
      (node (ref "P1") (pin "2") (pinfunction "2_2") (pintype "bidirectional"))
      (node (ref "P2") (pin "2") (pinfunction "2_2") (pintype "bidirectional"))
      (node (ref "POWER") (pin "1") (pinfunction "1_1") (pintype "passive"))
      (node (ref "QG2") (pin "7") (pinfunction "GND_7") (pintype "power_in"))
      (node (ref "R3") (pin "1") (pinfunction "1_1") (pintype "passive"))
      (node (ref "R32") (pin "2") (pinfunction "2_2") (pintype "passive"))
      (node (ref "R39") (pin "2") (pinfunction "2_2") (pintype "passive"))
      (node (ref "R41") (pin "2") (pinfunction "2_2") (pintype "passive"))
      (node (ref "R43") (pin "2") (pinfunction "2_2") (pintype "passive"))
      (node (ref "R7") (pin "1") (pinfunction "1_1") (pintype "passive"))
      (node (ref "S1") (pin "P$1") (pinfunction "P1_P$1") (pintype "bidirectional"))
      (node (ref "S129") (pin "P$1") (pinfunction "P$1_P$1") (pintype "bidirectional"))
      (node (ref "S129") (pin "P$2") (pinfunction "P$2_P$2") (pintype "bidirectional"))
      (node (ref "S129") (pin "P$3") (pinfunction "P$3_P$3") (pintype "bidirectional"))
      (node (ref "S129") (pin "P$4") (pinfunction "P$4_P$4") (pintype "bidirectional"))
      (node (ref "S129") (pin "P$5") (pinfunction "P$5_P$5") (pintype "bidirectional"))
      (node (ref "S137") (pin "P$1") (pinfunction "P$1_P$1") (pintype "bidirectional"))
      (node (ref "S137") (pin "P$2") (pinfunction "P$2_P$2") (pintype "bidirectional"))
      (node (ref "S137") (pin "P$3") (pinfunction "P$3_P$3") (pintype "bidirectional"))
      (node (ref "S137") (pin "P$4") (pinfunction "P$4_P$4") (pintype "bidirectional"))
      (node (ref "S137") (pin "P$5") (pinfunction "P$5_P$5") (pintype "bidirectional"))
      (node (ref "S159") (pin "P$1") (pinfunction "P1_P$1") (pintype "bidirectional"))
      (node (ref "S20") (pin "P$1") (pinfunction "P$1_P$1") (pintype "bidirectional"))
      (node (ref "S20") (pin "P$10") (pinfunction "P$10_P$10") (pintype "bidirectional"))
      (node (ref "S20") (pin "P$2") (pinfunction "P$2_P$2") (pintype "bidirectional"))
      (node (ref "S20") (pin "P$3") (pinfunction "P$3_P$3") (pintype "bidirectional"))
      (node (ref "S20") (pin "P$4") (pinfunction "P$4_P$4") (pintype "bidirectional"))
      (node (ref "S20") (pin "P$5") (pinfunction "P$5_P$5") (pintype "bidirectional"))
      (node (ref "S20") (pin "P$6") (pinfunction "P$6_P$6") (pintype "bidirectional"))
      (node (ref "S20") (pin "P$7") (pinfunction "P$7_P$7") (pintype "bidirectional"))
      (node (ref "S20") (pin "P$8") (pinfunction "P$8_P$8") (pintype "bidirectional"))
      (node (ref "S20") (pin "P$9") (pinfunction "P$9_P$9") (pintype "bidirectional"))
      (node (ref "S24") (pin "P$1") (pinfunction "P$1_P$1") (pintype "bidirectional"))
      (node (ref "S24") (pin "P$10") (pinfunction "P$10_P$10") (pintype "bidirectional"))
      (node (ref "S24") (pin "P$2") (pinfunction "P$2_P$2") (pintype "bidirectional"))
      (node (ref "S24") (pin "P$3") (pinfunction "P$3_P$3") (pintype "bidirectional"))
      (node (ref "S24") (pin "P$4") (pinfunction "P$4_P$4") (pintype "bidirectional"))
      (node (ref "S24") (pin "P$5") (pinfunction "P$5_P$5") (pintype "bidirectional"))
      (node (ref "S24") (pin "P$6") (pinfunction "P$6_P$6") (pintype "bidirectional"))
      (node (ref "S24") (pin "P$7") (pinfunction "P$7_P$7") (pintype "bidirectional"))
      (node (ref "S24") (pin "P$8") (pinfunction "P$8_P$8") (pintype "bidirectional"))
      (node (ref "S24") (pin "P$9") (pinfunction "P$9_P$9") (pintype "bidirectional"))
      (node (ref "SV11") (pin "1") (pinfunction "1_1") (pintype "passive"))
      (node (ref "SV12") (pin "1") (pinfunction "1_1") (pintype "passive"))
      (node (ref "SV13") (pin "2") (pinfunction "2_2") (pintype "passive"))
      (node (ref "SV14") (pin "10") (pinfunction "10_10") (pintype "passive"))
      (node (ref "SV14") (pin "12") (pinfunction "12_12") (pintype "passive"))
      (node (ref "SV14") (pin "4") (pinfunction "4_4") (pintype "passive"))
      (node (ref "SV14") (pin "8") (pinfunction "8_8") (pintype "passive"))
      (node (ref "SV15") (pin "1") (pinfunction "1_1") (pintype "passive"))
      (node (ref "SV16") (pin "10") (pinfunction "10_10") (pintype "passive"))
      (node (ref "SV16") (pin "12") (pinfunction "12_12") (pintype "passive"))
      (node (ref "SV16") (pin "4") (pinfunction "4_4") (pintype "passive"))
      (node (ref "SV16") (pin "8") (pinfunction "8_8") (pintype "passive"))
      (node (ref "SV17") (pin "13") (pinfunction "13_13") (pintype "passive"))
      (node (ref "SV17") (pin "14") (pinfunction "14_14") (pintype "passive"))
      (node (ref "SV2") (pin "13") (pinfunction "13_13") (pintype "passive"))
      (node (ref "SV2") (pin "14") (pinfunction "14_14") (pintype "passive"))
      (node (ref "SV2") (pin "19") (pinfunction "19_19") (pintype "passive"))
      (node (ref "SV2") (pin "20") (pinfunction "20_20") (pintype "passive"))
      (node (ref "SV2") (pin "29") (pinfunction "29_29") (pintype "passive"))
      (node (ref "SV2") (pin "30") (pinfunction "30_30") (pintype "passive"))
      (node (ref "SV2") (pin "33") (pinfunction "33_33") (pintype "passive"))
      (node (ref "SV2") (pin "34") (pinfunction "34_34") (pintype "passive"))
      (node (ref "SV2") (pin "5") (pinfunction "5_5") (pintype "passive"))
      (node (ref "SV2") (pin "6") (pinfunction "6_6") (pintype "passive"))
      (node (ref "SV23") (pin "10") (pinfunction "10_10") (pintype "passive"))
      (node (ref "SV23") (pin "9") (pinfunction "9_9") (pintype "passive"))
      (node (ref "SV4") (pin "10") (pinfunction "10_10") (pintype "passive"))
      (node (ref "SV4") (pin "25") (pinfunction "25_25") (pintype "passive"))
      (node (ref "SV4") (pin "26") (pinfunction "26_26") (pintype "passive"))
      (node (ref "SV4") (pin "39") (pinfunction "39_39") (pintype "passive"))
      (node (ref "SV4") (pin "40") (pinfunction "40_40") (pintype "passive"))
      (node (ref "SV4") (pin "9") (pinfunction "9_9") (pintype "passive"))
      (node (ref "SV6") (pin "17") (pinfunction "17_17") (pintype "passive"))
      (node (ref "SV6") (pin "18") (pinfunction "18_18") (pintype "passive"))
      (node (ref "T1") (pin "3") (pinfunction "E_3") (pintype "passive"))
      (node (ref "T2") (pin "3") (pinfunction "E_3") (pintype "passive"))
      (node (ref "TRIMPOT1") (pin "5") (pinfunction "5_5") (pintype "passive"))
      (node (ref "TRIMPOT1") (pin "6") (pinfunction "6_6") (pintype "passive"))
      (node (ref "TRIMPOT2") (pin "5") (pinfunction "5_5") (pintype "passive"))
      (node (ref "TRIMPOT2") (pin "6") (pinfunction "6_6") (pintype "passive"))
      (node (ref "U$1") (pin "2") (pinfunction "P2_GND_2") (pintype "bidirectional"))
      (node (ref "U1") (pin "11") (pinfunction "SENSE_11") (pintype "bidirectional"))
      (node (ref "U1") (pin "12") (pinfunction "GND_12") (pintype "bidirectional"))
      (node (ref "U1") (pin "13") (pinfunction "GND_13") (pintype "bidirectional"))
      (node (ref "U1") (pin "4") (pinfunction "GND_4") (pintype "bidirectional"))
      (node (ref "U1") (pin "5") (pinfunction "GND_5") (pintype "bidirectional"))
      (node (ref "U11") (pin "12") (pinfunction "VSS2_12") (pintype "bidirectional"))
      (node (ref "U11") (pin "2") (pinfunction "VSS_2") (pintype "bidirectional"))
      (node (ref "U11") (pin "23") (pinfunction "VSSA/VREFLO_23") (pintype "bidirectional"))
      (node (ref "U11") (pin "3") (pinfunction "/VREGENZ_3") (pintype "bidirectional"))
      (node (ref "U12") (pin "3") (pinfunction "GND_3") (pintype "bidirectional"))
      (node (ref "U2") (pin "P$15") (pinfunction "GND_P$15") (pintype "bidirectional"))
      (node (ref "U2") (pin "P$16") (pinfunction "PMODE_P$16") (pintype "bidirectional"))
      (node (ref "U2") (pin "P$17") (pinfunction "GND_PAD_P$17") (pintype "bidirectional"))
      (node (ref "U2") (pin "P$7") (pinfunction "IMODE_P$7") (pintype "bidirectional"))
      (node (ref "U2") (pin "P$9") (pinfunction "PGND_P$9") (pintype "bidirectional"))
      (node (ref "U3") (pin "4") (pinfunction "P4_GND_4") (pintype "bidirectional"))
      (node (ref "U4") (pin "P$15") (pinfunction "GND_P$15") (pintype "bidirectional"))
      (node (ref "U4") (pin "P$16") (pinfunction "PMODE_P$16") (pintype "bidirectional"))
      (node (ref "U4") (pin "P$17") (pinfunction "GND_PAD_P$17") (pintype "bidirectional"))
      (node (ref "U4") (pin "P$7") (pinfunction "IMODE_P$7") (pintype "bidirectional"))
      (node (ref "U4") (pin "P$9") (pinfunction "PGND_P$9") (pintype "bidirectional"))
      (node (ref "U5") (pin "11") (pinfunction "SENSE_11") (pintype "bidirectional"))
      (node (ref "U5") (pin "12") (pinfunction "GND_12") (pintype "bidirectional"))
      (node (ref "U5") (pin "13") (pinfunction "GND_13") (pintype "bidirectional"))
      (node (ref "U5") (pin "4") (pinfunction "GND_4") (pintype "bidirectional"))
      (node (ref "U5") (pin "5") (pinfunction "GND_5") (pintype "bidirectional"))
      (node (ref "U6") (pin "P$4") (pinfunction "V-_P$4") (pintype "bidirectional"))
      (node (ref "U7") (pin "3") (pinfunction "GND_3") (pintype "bidirectional"))
      (node (ref "U8") (pin "12") (pinfunction "VSS2_12") (pintype "bidirectional"))
      (node (ref "U8") (pin "2") (pinfunction "VSS_2") (pintype "bidirectional"))
      (node (ref "U8") (pin "23") (pinfunction "VSSA/VREFLO_23") (pintype "bidirectional"))
      (node (ref "U8") (pin "3") (pinfunction "/VREGENZ_3") (pintype "bidirectional"))
      (node (ref "U9") (pin "P$3") (pinfunction "GND_P$3") (pintype "bidirectional"))
      (node (ref "U9") (pin "P$6") (pinfunction "GND1_P$6") (pintype "bidirectional"))
    )
    (net (code "61") (name "MENABLE") (class "Default")
      (node (ref "S159") (pin "P$2") (pinfunction "P2_P$2") (pintype "bidirectional"))
      (node (ref "U2") (pin "P$3") (pinfunction "NSLEEP_P$3") (pintype "bidirectional"))
      (node (ref "U4") (pin "P$3") (pinfunction "NSLEEP_P$3") (pintype "bidirectional"))
    )
    (net (code "62") (name "MISO_5V") (class "Default")
      (node (ref "IC2") (pin "20") (pinfunction "A4_20") (pintype "bidirectional"))
      (node (ref "U12") (pin "6") (pinfunction "MISO_6") (pintype "bidirectional"))
      (node (ref "U7") (pin "6") (pinfunction "MISO_6") (pintype "bidirectional"))
    )
    (net (code "63") (name "MOSI_5V") (class "Default")
      (node (ref "IC2") (pin "18") (pinfunction "A3_18") (pintype "bidirectional"))
      (node (ref "U12") (pin "7") (pinfunction "MOSI_7") (pintype "bidirectional"))
      (node (ref "U7") (pin "7") (pinfunction "MOSI_7") (pintype "bidirectional"))
    )
    (net (code "64") (name "MOTOR1+") (class "Default")
      (node (ref "SV3") (pin "1") (pinfunction "1_1") (pintype "passive"))
      (node (ref "SV3") (pin "3") (pinfunction "3_3") (pintype "passive"))
      (node (ref "SV3") (pin "5") (pinfunction "5_5") (pintype "passive"))
      (node (ref "U1") (pin "15") (pinfunction "OUTB_15") (pintype "bidirectional"))
    )
    (net (code "65") (name "MOTOR1-") (class "Default")
      (node (ref "SV3") (pin "2") (pinfunction "2_2") (pintype "passive"))
      (node (ref "SV3") (pin "4") (pinfunction "4_4") (pintype "passive"))
      (node (ref "SV3") (pin "6") (pinfunction "6_6") (pintype "passive"))
      (node (ref "U1") (pin "10") (pinfunction "OUTA_10") (pintype "bidirectional"))
    )
    (net (code "66") (name "MOTOR2+") (class "Default")
      (node (ref "SV1") (pin "1") (pinfunction "1_1") (pintype "passive"))
      (node (ref "SV1") (pin "3") (pinfunction "3_3") (pintype "passive"))
      (node (ref "SV1") (pin "5") (pinfunction "5_5") (pintype "passive"))
      (node (ref "U5") (pin "15") (pinfunction "OUTB_15") (pintype "bidirectional"))
    )
    (net (code "67") (name "MOTOR2-") (class "Default")
      (node (ref "SV1") (pin "2") (pinfunction "2_2") (pintype "passive"))
      (node (ref "SV1") (pin "4") (pinfunction "4_4") (pintype "passive"))
      (node (ref "SV1") (pin "6") (pinfunction "6_6") (pintype "passive"))
      (node (ref "U5") (pin "10") (pinfunction "OUTA_10") (pintype "bidirectional"))
    )
    (net (code "68") (name "Net-(3V3-PadA)") (class "Default")
      (node (ref "3V3") (pin "A") (pinfunction "A_A") (pintype "passive"))
      (node (ref "R27") (pin "1") (pinfunction "1_1") (pintype "passive"))
    )
    (net (code "69") (name "Net-(5V-PadA)") (class "Default")
      (node (ref "5V") (pin "A") (pinfunction "A_A") (pintype "passive"))
      (node (ref "R26") (pin "1") (pinfunction "1_1") (pintype "passive"))
    )
    (net (code "70") (name "Net-(B1-PadP$1)") (class "Default")
      (node (ref "B1") (pin "P$1") (pinfunction "P$1_P$1") (pintype "bidirectional"))
      (node (ref "R40") (pin "2") (pinfunction "2_2") (pintype "passive"))
    )
    (net (code "71") (name "Net-(B4-P1)") (class "Default")
      (node (ref "B4") (pin "P$1") (pinfunction "P1_P$1") (pintype "bidirectional"))
      (node (ref "SV10") (pin "1") (pinfunction "1_1") (pintype "passive"))
      (node (ref "U6") (pin "P$1") (pinfunction "IN1_P$1") (pintype "bidirectional"))
    )
    (net (code "72") (name "Net-(B5-P1)") (class "Default")
      (node (ref "B5") (pin "P$1") (pinfunction "P1_P$1") (pintype "bidirectional"))
      (node (ref "SV10") (pin "2") (pinfunction "2_2") (pintype "passive"))
      (node (ref "U6") (pin "P$2") (pinfunction "IN2_P$2") (pintype "bidirectional"))
    )
    (net (code "73") (name "Net-(IC2A-A1)") (class "Default")
      (node (ref "IC2") (pin "3") (pinfunction "A1_3") (pintype "bidirectional"))
      (node (ref "J20") (pin "P$1") (pinfunction "P$1_P$1") (pintype "bidirectional"))
      (node (ref "J20") (pin "P$2") (pinfunction "P$2_P$2") (pintype "bidirectional"))
    )
    (net (code "74") (name "Net-(IC2A-A2)") (class "Default")
      (node (ref "IC2") (pin "5") (pinfunction "A2_5") (pintype "bidirectional"))
      (node (ref "J19") (pin "P$1") (pinfunction "P$1_P$1") (pintype "bidirectional"))
      (node (ref "J19") (pin "P$2") (pinfunction "P$2_P$2") (pintype "bidirectional"))
    )
    (net (code "75") (name "Net-(IC2A-A3)") (class "Default")
      (node (ref "IC2") (pin "7") (pinfunction "A3_7") (pintype "bidirectional"))
      (node (ref "J18") (pin "P$1") (pinfunction "P$1_P$1") (pintype "bidirectional"))
      (node (ref "J18") (pin "P$2") (pinfunction "P$2_P$2") (pintype "bidirectional"))
    )
    (net (code "76") (name "Net-(IC2A-A4)") (class "Default")
      (node (ref "IC2") (pin "9") (pinfunction "A4_9") (pintype "bidirectional"))
      (node (ref "J17") (pin "P$1") (pinfunction "P$1_P$1") (pintype "bidirectional"))
      (node (ref "J17") (pin "P$2") (pinfunction "P$2_P$2") (pintype "bidirectional"))
    )
    (net (code "77") (name "Net-(IC2A-A5)") (class "Default")
      (node (ref "IC2") (pin "11") (pinfunction "A5_11") (pintype "bidirectional"))
      (node (ref "J16") (pin "P$1") (pinfunction "P$1_P$1") (pintype "bidirectional"))
      (node (ref "J16") (pin "P$2") (pinfunction "P$2_P$2") (pintype "bidirectional"))
    )
    (net (code "78") (name "Net-(IC2A-B1)") (class "Default")
      (node (ref "IC2") (pin "2") (pinfunction "B1_2") (pintype "bidirectional"))
      (node (ref "J15") (pin "P$1") (pinfunction "P$1_P$1") (pintype "bidirectional"))
      (node (ref "J15") (pin "P$2") (pinfunction "P$2_P$2") (pintype "bidirectional"))
    )
    (net (code "79") (name "Net-(IC2A-B2)") (class "Default")
      (node (ref "IC2") (pin "4") (pinfunction "B2_4") (pintype "bidirectional"))
      (node (ref "J14") (pin "P$1") (pinfunction "P$1_P$1") (pintype "bidirectional"))
      (node (ref "J14") (pin "P$2") (pinfunction "P$2_P$2") (pintype "bidirectional"))
    )
    (net (code "80") (name "Net-(IC2A-B3)") (class "Default")
      (node (ref "IC2") (pin "6") (pinfunction "B3_6") (pintype "bidirectional"))
      (node (ref "J11") (pin "P$1") (pinfunction "P$1_P$1") (pintype "bidirectional"))
      (node (ref "J11") (pin "P$2") (pinfunction "P$2_P$2") (pintype "bidirectional"))
    )
    (net (code "81") (name "Net-(IC2A-B4)") (class "Default")
      (node (ref "IC2") (pin "8") (pinfunction "B4_8") (pintype "bidirectional"))
      (node (ref "J10") (pin "P$1") (pinfunction "P$1_P$1") (pintype "bidirectional"))
      (node (ref "J10") (pin "P$2") (pinfunction "P$2_P$2") (pintype "bidirectional"))
    )
    (net (code "82") (name "Net-(IC2A-B5)") (class "Default")
      (node (ref "IC2") (pin "10") (pinfunction "B5_10") (pintype "bidirectional"))
      (node (ref "J9") (pin "P$1") (pinfunction "P$1_P$1") (pintype "bidirectional"))
      (node (ref "J9") (pin "P$2") (pinfunction "P$2_P$2") (pintype "bidirectional"))
    )
    (net (code "83") (name "Net-(IC3A-O)") (class "Default")
      (node (ref "IC3") (pin "2") (pinfunction "O_2") (pintype "output"))
      (node (ref "LED2") (pin "C") (pinfunction "C_C") (pintype "passive"))
    )
    (net (code "84") (name "Net-(IC3B-O)") (class "Default")
      (node (ref "IC3") (pin "4") (pinfunction "O_4") (pintype "output"))
      (node (ref "LED3") (pin "C") (pinfunction "C_C") (pintype "passive"))
    )
    (net (code "85") (name "Net-(IC3C-O)") (class "Default")
      (node (ref "IC3") (pin "6") (pinfunction "O_6") (pintype "output"))
      (node (ref "LED4") (pin "C") (pinfunction "C_C") (pintype "passive"))
    )
    (net (code "86") (name "Net-(IC3D-O)") (class "Default")
      (node (ref "IC3") (pin "8") (pinfunction "O_8") (pintype "output"))
      (node (ref "LED5") (pin "C") (pinfunction "C_C") (pintype "passive"))
    )
    (net (code "87") (name "Net-(IC3E-I)") (class "Default")
      (node (ref "IC3") (pin "11") (pinfunction "I_11") (pintype "input"))
      (node (ref "J194") (pin "P$1") (pinfunction "P$1_P$1") (pintype "bidirectional"))
      (node (ref "J194") (pin "P$2") (pinfunction "P$2_P$2") (pintype "bidirectional"))
    )
    (net (code "88") (name "Net-(IC3E-O)") (class "Default")
      (node (ref "IC3") (pin "10") (pinfunction "O_10") (pintype "output"))
      (node (ref "R40") (pin "1") (pinfunction "1_1") (pintype "passive"))
    )
    (net (code "89") (name "Net-(IC3F-O)") (class "Default")
      (node (ref "IC3") (pin "12") (pinfunction "O_12") (pintype "output"))
      (node (ref "LED1") (pin "C") (pinfunction "C_C") (pintype "passive"))
    )
    (net (code "90") (name "Net-(J6-PadP$1)") (class "Default")
      (node (ref "J6") (pin "P$1") (pinfunction "P$1_P$1") (pintype "bidirectional"))
      (node (ref "J6") (pin "P$2") (pinfunction "P$2_P$2") (pintype "bidirectional"))
      (node (ref "J6") (pin "P$3") (pinfunction "P$3_P$3") (pintype "bidirectional"))
      (node (ref "R1") (pin "1") (pinfunction "1_1") (pintype "passive"))
    )
    (net (code "91") (name "Net-(J8-PadP$1)") (class "Default")
      (node (ref "J8") (pin "P$1") (pinfunction "P$1_P$1") (pintype "bidirectional"))
      (node (ref "J8") (pin "P$2") (pinfunction "P$2_P$2") (pintype "bidirectional"))
    )
    (net (code "92") (name "Net-(J12-PadP$1)") (class "Default")
      (node (ref "J12") (pin "P$1") (pinfunction "P$1_P$1") (pintype "bidirectional"))
      (node (ref "J12") (pin "P$2") (pinfunction "P$2_P$2") (pintype "bidirectional"))
    )
    (net (code "93") (name "Net-(J13-PadP$1)") (class "Default")
      (node (ref "J13") (pin "P$1") (pinfunction "P$1_P$1") (pintype "bidirectional"))
      (node (ref "J13") (pin "P$2") (pinfunction "P$2_P$2") (pintype "bidirectional"))
    )
    (net (code "94") (name "Net-(J22-PadP$1)") (class "Default")
      (node (ref "J22") (pin "P$1") (pinfunction "P$1_P$1") (pintype "bidirectional"))
      (node (ref "J22") (pin "P$2") (pinfunction "P$2_P$2") (pintype "bidirectional"))
    )
    (net (code "95") (name "Net-(J24-PadP$1)") (class "Default")
      (node (ref "J24") (pin "P$1") (pinfunction "P$1_P$1") (pintype "bidirectional"))
      (node (ref "J24") (pin "P$2") (pinfunction "P$2_P$2") (pintype "bidirectional"))
      (node (ref "J24") (pin "P$3") (pinfunction "P$3_P$3") (pintype "bidirectional"))
      (node (ref "R2") (pin "1") (pinfunction "1_1") (pintype "passive"))
    )
    (net (code "96") (name "Net-(J88-PadP$1)") (class "Default")
      (node (ref "J88") (pin "P$1") (pinfunction "P$1_P$1") (pintype "bidirectional"))
      (node (ref "J91") (pin "P$1") (pinfunction "P$1_P$1") (pintype "bidirectional"))
      (node (ref "J91") (pin "P$2") (pinfunction "P$2_P$2") (pintype "bidirectional"))
    )
    (net (code "97") (name "Net-(J88-PadP$3)") (class "Default")
      (node (ref "J88") (pin "P$3") (pinfunction "P$3_P$3") (pintype "bidirectional"))
      (node (ref "J92") (pin "P$1") (pinfunction "P$1_P$1") (pintype "bidirectional"))
      (node (ref "J92") (pin "P$2") (pinfunction "P$2_P$2") (pintype "bidirectional"))
    )
    (net (code "98") (name "Net-(J88-PadP$4)") (class "Default")
      (node (ref "J88") (pin "P$4") (pinfunction "P$4_P$4") (pintype "bidirectional"))
      (node (ref "J93") (pin "P$1") (pinfunction "P$1_P$1") (pintype "bidirectional"))
      (node (ref "J93") (pin "P$2") (pinfunction "P$2_P$2") (pintype "bidirectional"))
    )
    (net (code "99") (name "Net-(J88-R+)") (class "Default")
      (node (ref "J88") (pin "P$2") (pinfunction "R+_P$2") (pintype "bidirectional"))
      (node (ref "J89") (pin "P$1") (pinfunction "P$1_P$1") (pintype "bidirectional"))
      (node (ref "J89") (pin "P$2") (pinfunction "P$2_P$2") (pintype "bidirectional"))
    )
    (net (code "100") (name "Net-(J88-R-)") (class "Default")
      (node (ref "J88") (pin "P$5") (pinfunction "R-_P$5") (pintype "bidirectional"))
      (node (ref "J90") (pin "P$1") (pinfunction "P$1_P$1") (pintype "bidirectional"))
      (node (ref "J90") (pin "P$2") (pinfunction "P$2_P$2") (pintype "bidirectional"))
    )
    (net (code "101") (name "Net-(LED1-PadA)") (class "Default")
      (node (ref "LED1") (pin "A") (pinfunction "A_A") (pintype "passive"))
      (node (ref "R11") (pin "1") (pinfunction "1_1") (pintype "passive"))
    )
    (net (code "102") (name "Net-(LED2-PadA)") (class "Default")
      (node (ref "LED2") (pin "A") (pinfunction "A_A") (pintype "passive"))
      (node (ref "R28") (pin "1") (pinfunction "1_1") (pintype "passive"))
    )
    (net (code "103") (name "Net-(LED3-PadA)") (class "Default")
      (node (ref "LED3") (pin "A") (pinfunction "A_A") (pintype "passive"))
      (node (ref "R29") (pin "1") (pinfunction "1_1") (pintype "passive"))
    )
    (net (code "104") (name "Net-(LED4-PadA)") (class "Default")
      (node (ref "LED4") (pin "A") (pinfunction "A_A") (pintype "passive"))
      (node (ref "R30") (pin "1") (pinfunction "1_1") (pintype "passive"))
    )
    (net (code "105") (name "Net-(LED5-PadA)") (class "Default")
      (node (ref "LED5") (pin "A") (pinfunction "A_A") (pintype "passive"))
      (node (ref "R31") (pin "1") (pinfunction "1_1") (pintype "passive"))
    )
    (net (code "106") (name "Net-(LED6-PadA)") (class "Default")
      (node (ref "LED6") (pin "A") (pinfunction "A_A") (pintype "passive"))
      (node (ref "R14") (pin "1") (pinfunction "1_1") (pintype "passive"))
    )
    (net (code "107") (name "Net-(LED7-PadA)") (class "Default")
      (node (ref "LED7") (pin "A") (pinfunction "A_A") (pintype "passive"))
      (node (ref "R36") (pin "1") (pinfunction "1_1") (pintype "passive"))
    )
    (net (code "108") (name "Net-(LED18-PadA)") (class "Default")
      (node (ref "LED18") (pin "A") (pinfunction "A_A") (pintype "passive"))
      (node (ref "R48") (pin "1") (pinfunction "1_1") (pintype "passive"))
    )
    (net (code "109") (name "Net-(QG2-OUT)") (class "Default")
      (node (ref "QG2") (pin "8") (pinfunction "OUT_8") (pintype "output"))
      (node (ref "U12") (pin "2") (pinfunction "FCKI_2") (pintype "bidirectional"))
      (node (ref "U7") (pin "2") (pinfunction "FCKI_2") (pintype "bidirectional"))
    )
    (net (code "110") (name "Net-(S1-P3)") (class "Default")
      (node (ref "R24") (pin "1") (pinfunction "1_1") (pintype "passive"))
      (node (ref "S1") (pin "P$3") (pinfunction "P3_P$3") (pintype "bidirectional"))
    )
    (net (code "111") (name "Net-(S130-PadP$1)") (class "Default")
      (node (ref "S130") (pin "P$1") (pinfunction "P$1_P$1") (pintype "bidirectional"))
      (node (ref "S130") (pin "P$2") (pinfunction "P$2_P$2") (pintype "bidirectional"))
      (node (ref "S130") (pin "P$3") (pinfunction "P$3_P$3") (pintype "bidirectional"))
      (node (ref "S130") (pin "P$4") (pinfunction "P$4_P$4") (pintype "bidirectional"))
      (node (ref "S130") (pin "P$5") (pinfunction "P$5_P$5") (pintype "bidirectional"))
    )
    (net (code "112") (name "Net-(S138-PadP$1)") (class "Default")
      (node (ref "S138") (pin "P$1") (pinfunction "P$1_P$1") (pintype "bidirectional"))
      (node (ref "S138") (pin "P$2") (pinfunction "P$2_P$2") (pintype "bidirectional"))
      (node (ref "S138") (pin "P$3") (pinfunction "P$3_P$3") (pintype "bidirectional"))
      (node (ref "S138") (pin "P$4") (pinfunction "P$4_P$4") (pintype "bidirectional"))
      (node (ref "S138") (pin "P$5") (pinfunction "P$5_P$5") (pintype "bidirectional"))
    )
    (net (code "113") (name "Net-(S139-PadP$1)") (class "Default")
      (node (ref "S139") (pin "P$1") (pinfunction "P$1_P$1") (pintype "bidirectional"))
      (node (ref "S139") (pin "P$2") (pinfunction "P$2_P$2") (pintype "bidirectional"))
      (node (ref "S139") (pin "P$3") (pinfunction "P$3_P$3") (pintype "bidirectional"))
      (node (ref "S139") (pin "P$4") (pinfunction "P$4_P$4") (pintype "bidirectional"))
      (node (ref "S139") (pin "P$5") (pinfunction "P$5_P$5") (pintype "bidirectional"))
    )
    (net (code "114") (name "Net-(S147-PadP$1)") (class "Default")
      (node (ref "S147") (pin "P$1") (pinfunction "P$1_P$1") (pintype "bidirectional"))
      (node (ref "S147") (pin "P$2") (pinfunction "P$2_P$2") (pintype "bidirectional"))
      (node (ref "S147") (pin "P$3") (pinfunction "P$3_P$3") (pintype "bidirectional"))
      (node (ref "S147") (pin "P$4") (pinfunction "P$4_P$4") (pintype "bidirectional"))
      (node (ref "S147") (pin "P$5") (pinfunction "P$5_P$5") (pintype "bidirectional"))
    )
    (net (code "115") (name "Net-(S159-P3)") (class "Default")
      (node (ref "R18") (pin "1") (pinfunction "1_1") (pintype "passive"))
      (node (ref "S159") (pin "P$3") (pinfunction "P3_P$3") (pintype "bidirectional"))
    )
    (net (code "116") (name "Net-(S167-PadP$1)") (class "Default")
      (node (ref "S167") (pin "P$1") (pinfunction "P$1_P$1") (pintype "bidirectional"))
      (node (ref "S167") (pin "P$2") (pinfunction "P$2_P$2") (pintype "bidirectional"))
      (node (ref "S167") (pin "P$3") (pinfunction "P$3_P$3") (pintype "bidirectional"))
      (node (ref "S167") (pin "P$4") (pinfunction "P$4_P$4") (pintype "bidirectional"))
      (node (ref "S167") (pin "P$5") (pinfunction "P$5_P$5") (pintype "bidirectional"))
    )
    (net (code "117") (name "Net-(S168-PadP$1)") (class "Default")
      (node (ref "S168") (pin "P$1") (pinfunction "P$1_P$1") (pintype "bidirectional"))
      (node (ref "S168") (pin "P$2") (pinfunction "P$2_P$2") (pintype "bidirectional"))
      (node (ref "S168") (pin "P$3") (pinfunction "P$3_P$3") (pintype "bidirectional"))
      (node (ref "S168") (pin "P$4") (pinfunction "P$4_P$4") (pintype "bidirectional"))
      (node (ref "S168") (pin "P$5") (pinfunction "P$5_P$5") (pintype "bidirectional"))
    )
    (net (code "118") (name "Net-(S169-PadP$1)") (class "Default")
      (node (ref "S169") (pin "P$1") (pinfunction "P$1_P$1") (pintype "bidirectional"))
      (node (ref "S169") (pin "P$2") (pinfunction "P$2_P$2") (pintype "bidirectional"))
      (node (ref "S169") (pin "P$3") (pinfunction "P$3_P$3") (pintype "bidirectional"))
      (node (ref "S169") (pin "P$4") (pinfunction "P$4_P$4") (pintype "bidirectional"))
      (node (ref "S169") (pin "P$5") (pinfunction "P$5_P$5") (pintype "bidirectional"))
    )
    (net (code "119") (name "Net-(S170-PadP$1)") (class "Default")
      (node (ref "S170") (pin "P$1") (pinfunction "P$1_P$1") (pintype "bidirectional"))
      (node (ref "S170") (pin "P$2") (pinfunction "P$2_P$2") (pintype "bidirectional"))
      (node (ref "S170") (pin "P$3") (pinfunction "P$3_P$3") (pintype "bidirectional"))
      (node (ref "S170") (pin "P$4") (pinfunction "P$4_P$4") (pintype "bidirectional"))
      (node (ref "S170") (pin "P$5") (pinfunction "P$5_P$5") (pintype "bidirectional"))
    )
    (net (code "120") (name "Net-(S171-PadP$1)") (class "Default")
      (node (ref "S171") (pin "P$1") (pinfunction "P$1_P$1") (pintype "bidirectional"))
      (node (ref "S171") (pin "P$2") (pinfunction "P$2_P$2") (pintype "bidirectional"))
      (node (ref "S171") (pin "P$3") (pinfunction "P$3_P$3") (pintype "bidirectional"))
      (node (ref "S171") (pin "P$4") (pinfunction "P$4_P$4") (pintype "bidirectional"))
      (node (ref "S171") (pin "P$5") (pinfunction "P$5_P$5") (pintype "bidirectional"))
    )
    (net (code "121") (name "Net-(S172-PadP$1)") (class "Default")
      (node (ref "S172") (pin "P$1") (pinfunction "P$1_P$1") (pintype "bidirectional"))
      (node (ref "S172") (pin "P$2") (pinfunction "P$2_P$2") (pintype "bidirectional"))
      (node (ref "S172") (pin "P$3") (pinfunction "P$3_P$3") (pintype "bidirectional"))
      (node (ref "S172") (pin "P$4") (pinfunction "P$4_P$4") (pintype "bidirectional"))
      (node (ref "S172") (pin "P$5") (pinfunction "P$5_P$5") (pintype "bidirectional"))
    )
    (net (code "122") (name "Net-(S173-PadP$1)") (class "Default")
      (node (ref "S173") (pin "P$1") (pinfunction "P$1_P$1") (pintype "bidirectional"))
      (node (ref "S173") (pin "P$2") (pinfunction "P$2_P$2") (pintype "bidirectional"))
      (node (ref "S173") (pin "P$3") (pinfunction "P$3_P$3") (pintype "bidirectional"))
      (node (ref "S173") (pin "P$4") (pinfunction "P$4_P$4") (pintype "bidirectional"))
      (node (ref "S173") (pin "P$5") (pinfunction "P$5_P$5") (pintype "bidirectional"))
    )
    (net (code "123") (name "Net-(S174-PadP$1)") (class "Default")
      (node (ref "S174") (pin "P$1") (pinfunction "P$1_P$1") (pintype "bidirectional"))
      (node (ref "S174") (pin "P$2") (pinfunction "P$2_P$2") (pintype "bidirectional"))
      (node (ref "S174") (pin "P$3") (pinfunction "P$3_P$3") (pintype "bidirectional"))
      (node (ref "S174") (pin "P$4") (pinfunction "P$4_P$4") (pintype "bidirectional"))
      (node (ref "S174") (pin "P$5") (pinfunction "P$5_P$5") (pintype "bidirectional"))
    )
    (net (code "124") (name "Net-(S175-PadP$1)") (class "Default")
      (node (ref "S175") (pin "P$1") (pinfunction "P$1_P$1") (pintype "bidirectional"))
      (node (ref "S175") (pin "P$2") (pinfunction "P$2_P$2") (pintype "bidirectional"))
      (node (ref "S175") (pin "P$3") (pinfunction "P$3_P$3") (pintype "bidirectional"))
      (node (ref "S175") (pin "P$4") (pinfunction "P$4_P$4") (pintype "bidirectional"))
      (node (ref "S175") (pin "P$5") (pinfunction "P$5_P$5") (pintype "bidirectional"))
    )
    (net (code "125") (name "Net-(S176-PadP$1)") (class "Default")
      (node (ref "S176") (pin "P$1") (pinfunction "P$1_P$1") (pintype "bidirectional"))
      (node (ref "S176") (pin "P$2") (pinfunction "P$2_P$2") (pintype "bidirectional"))
      (node (ref "S176") (pin "P$3") (pinfunction "P$3_P$3") (pintype "bidirectional"))
      (node (ref "S176") (pin "P$4") (pinfunction "P$4_P$4") (pintype "bidirectional"))
      (node (ref "S176") (pin "P$5") (pinfunction "P$5_P$5") (pintype "bidirectional"))
    )
    (net (code "126") (name "Net-(S177-PadP$1)") (class "Default")
      (node (ref "S177") (pin "P$1") (pinfunction "P$1_P$1") (pintype "bidirectional"))
      (node (ref "S177") (pin "P$2") (pinfunction "P$2_P$2") (pintype "bidirectional"))
      (node (ref "S177") (pin "P$3") (pinfunction "P$3_P$3") (pintype "bidirectional"))
      (node (ref "S177") (pin "P$4") (pinfunction "P$4_P$4") (pintype "bidirectional"))
      (node (ref "S177") (pin "P$5") (pinfunction "P$5_P$5") (pintype "bidirectional"))
    )
    (net (code "127") (name "Net-(S178-PadP$1)") (class "Default")
      (node (ref "S178") (pin "P$1") (pinfunction "P$1_P$1") (pintype "bidirectional"))
      (node (ref "S178") (pin "P$2") (pinfunction "P$2_P$2") (pintype "bidirectional"))
      (node (ref "S178") (pin "P$3") (pinfunction "P$3_P$3") (pintype "bidirectional"))
      (node (ref "S178") (pin "P$4") (pinfunction "P$4_P$4") (pintype "bidirectional"))
      (node (ref "S178") (pin "P$5") (pinfunction "P$5_P$5") (pintype "bidirectional"))
    )
    (net (code "128") (name "Net-(S179-PadP$1)") (class "Default")
      (node (ref "S179") (pin "P$1") (pinfunction "P$1_P$1") (pintype "bidirectional"))
      (node (ref "S179") (pin "P$2") (pinfunction "P$2_P$2") (pintype "bidirectional"))
      (node (ref "S179") (pin "P$3") (pinfunction "P$3_P$3") (pintype "bidirectional"))
      (node (ref "S179") (pin "P$4") (pinfunction "P$4_P$4") (pintype "bidirectional"))
      (node (ref "S179") (pin "P$5") (pinfunction "P$5_P$5") (pintype "bidirectional"))
    )
    (net (code "129") (name "Net-(S180-PadP$1)") (class "Default")
      (node (ref "S180") (pin "P$1") (pinfunction "P$1_P$1") (pintype "bidirectional"))
      (node (ref "S180") (pin "P$2") (pinfunction "P$2_P$2") (pintype "bidirectional"))
      (node (ref "S180") (pin "P$3") (pinfunction "P$3_P$3") (pintype "bidirectional"))
      (node (ref "S180") (pin "P$4") (pinfunction "P$4_P$4") (pintype "bidirectional"))
      (node (ref "S180") (pin "P$5") (pinfunction "P$5_P$5") (pintype "bidirectional"))
    )
    (net (code "130") (name "Net-(S181-PadP$1)") (class "Default")
      (node (ref "S181") (pin "P$1") (pinfunction "P$1_P$1") (pintype "bidirectional"))
      (node (ref "S181") (pin "P$2") (pinfunction "P$2_P$2") (pintype "bidirectional"))
      (node (ref "S181") (pin "P$3") (pinfunction "P$3_P$3") (pintype "bidirectional"))
      (node (ref "S181") (pin "P$4") (pinfunction "P$4_P$4") (pintype "bidirectional"))
      (node (ref "S181") (pin "P$5") (pinfunction "P$5_P$5") (pintype "bidirectional"))
    )
    (net (code "131") (name "Net-(S182-PadP$1)") (class "Default")
      (node (ref "S182") (pin "P$1") (pinfunction "P$1_P$1") (pintype "bidirectional"))
      (node (ref "S182") (pin "P$2") (pinfunction "P$2_P$2") (pintype "bidirectional"))
      (node (ref "S182") (pin "P$3") (pinfunction "P$3_P$3") (pintype "bidirectional"))
      (node (ref "S182") (pin "P$4") (pinfunction "P$4_P$4") (pintype "bidirectional"))
      (node (ref "S182") (pin "P$5") (pinfunction "P$5_P$5") (pintype "bidirectional"))
    )
    (net (code "132") (name "Net-(S183-PadP$1)") (class "Default")
      (node (ref "S183") (pin "P$1") (pinfunction "P$1_P$1") (pintype "bidirectional"))
      (node (ref "S183") (pin "P$2") (pinfunction "P$2_P$2") (pintype "bidirectional"))
      (node (ref "S183") (pin "P$3") (pinfunction "P$3_P$3") (pintype "bidirectional"))
      (node (ref "S183") (pin "P$4") (pinfunction "P$4_P$4") (pintype "bidirectional"))
      (node (ref "S183") (pin "P$5") (pinfunction "P$5_P$5") (pintype "bidirectional"))
    )
    (net (code "133") (name "Net-(S184-PadP$1)") (class "Default")
      (node (ref "S184") (pin "P$1") (pinfunction "P$1_P$1") (pintype "bidirectional"))
      (node (ref "S184") (pin "P$2") (pinfunction "P$2_P$2") (pintype "bidirectional"))
      (node (ref "S184") (pin "P$3") (pinfunction "P$3_P$3") (pintype "bidirectional"))
      (node (ref "S184") (pin "P$4") (pinfunction "P$4_P$4") (pintype "bidirectional"))
      (node (ref "S184") (pin "P$5") (pinfunction "P$5_P$5") (pintype "bidirectional"))
    )
    (net (code "134") (name "Net-(S185-PadP$1)") (class "Default")
      (node (ref "S185") (pin "P$1") (pinfunction "P$1_P$1") (pintype "bidirectional"))
      (node (ref "S185") (pin "P$2") (pinfunction "P$2_P$2") (pintype "bidirectional"))
      (node (ref "S185") (pin "P$3") (pinfunction "P$3_P$3") (pintype "bidirectional"))
      (node (ref "S185") (pin "P$4") (pinfunction "P$4_P$4") (pintype "bidirectional"))
      (node (ref "S185") (pin "P$5") (pinfunction "P$5_P$5") (pintype "bidirectional"))
    )
    (net (code "135") (name "Net-(S186-PadP$1)") (class "Default")
      (node (ref "S186") (pin "P$1") (pinfunction "P$1_P$1") (pintype "bidirectional"))
      (node (ref "S186") (pin "P$2") (pinfunction "P$2_P$2") (pintype "bidirectional"))
      (node (ref "S186") (pin "P$3") (pinfunction "P$3_P$3") (pintype "bidirectional"))
      (node (ref "S186") (pin "P$4") (pinfunction "P$4_P$4") (pintype "bidirectional"))
      (node (ref "S186") (pin "P$5") (pinfunction "P$5_P$5") (pintype "bidirectional"))
    )
    (net (code "136") (name "Net-(S187-PadP$1)") (class "Default")
      (node (ref "S187") (pin "P$1") (pinfunction "P$1_P$1") (pintype "bidirectional"))
      (node (ref "S187") (pin "P$2") (pinfunction "P$2_P$2") (pintype "bidirectional"))
      (node (ref "S187") (pin "P$3") (pinfunction "P$3_P$3") (pintype "bidirectional"))
      (node (ref "S187") (pin "P$4") (pinfunction "P$4_P$4") (pintype "bidirectional"))
      (node (ref "S187") (pin "P$5") (pinfunction "P$5_P$5") (pintype "bidirectional"))
    )
    (net (code "137") (name "Net-(S188-PadP$1)") (class "Default")
      (node (ref "S188") (pin "P$1") (pinfunction "P$1_P$1") (pintype "bidirectional"))
      (node (ref "S188") (pin "P$2") (pinfunction "P$2_P$2") (pintype "bidirectional"))
      (node (ref "S188") (pin "P$3") (pinfunction "P$3_P$3") (pintype "bidirectional"))
      (node (ref "S188") (pin "P$4") (pinfunction "P$4_P$4") (pintype "bidirectional"))
      (node (ref "S188") (pin "P$5") (pinfunction "P$5_P$5") (pintype "bidirectional"))
    )
    (net (code "138") (name "Net-(S189-PadP$1)") (class "Default")
      (node (ref "S189") (pin "P$1") (pinfunction "P$1_P$1") (pintype "bidirectional"))
      (node (ref "S189") (pin "P$2") (pinfunction "P$2_P$2") (pintype "bidirectional"))
      (node (ref "S189") (pin "P$3") (pinfunction "P$3_P$3") (pintype "bidirectional"))
      (node (ref "S189") (pin "P$4") (pinfunction "P$4_P$4") (pintype "bidirectional"))
      (node (ref "S189") (pin "P$5") (pinfunction "P$5_P$5") (pintype "bidirectional"))
    )
    (net (code "139") (name "Net-(S210-PadP$1)") (class "Default")
      (node (ref "S210") (pin "P$1") (pinfunction "P$1_P$1") (pintype "bidirectional"))
      (node (ref "S210") (pin "P$2") (pinfunction "P$2_P$2") (pintype "bidirectional"))
      (node (ref "S210") (pin "P$3") (pinfunction "P$3_P$3") (pintype "bidirectional"))
      (node (ref "S210") (pin "P$4") (pinfunction "P$4_P$4") (pintype "bidirectional"))
      (node (ref "S210") (pin "P$5") (pinfunction "P$5_P$5") (pintype "bidirectional"))
    )
    (net (code "140") (name "Net-(S211-PadP$1)") (class "Default")
      (node (ref "S211") (pin "P$1") (pinfunction "P$1_P$1") (pintype "bidirectional"))
      (node (ref "S211") (pin "P$2") (pinfunction "P$2_P$2") (pintype "bidirectional"))
      (node (ref "S211") (pin "P$3") (pinfunction "P$3_P$3") (pintype "bidirectional"))
      (node (ref "S211") (pin "P$4") (pinfunction "P$4_P$4") (pintype "bidirectional"))
      (node (ref "S211") (pin "P$5") (pinfunction "P$5_P$5") (pintype "bidirectional"))
    )
    (net (code "141") (name "Net-(S212-PadP$1)") (class "Default")
      (node (ref "S212") (pin "P$1") (pinfunction "P$1_P$1") (pintype "bidirectional"))
      (node (ref "S212") (pin "P$2") (pinfunction "P$2_P$2") (pintype "bidirectional"))
      (node (ref "S212") (pin "P$3") (pinfunction "P$3_P$3") (pintype "bidirectional"))
      (node (ref "S212") (pin "P$4") (pinfunction "P$4_P$4") (pintype "bidirectional"))
      (node (ref "S212") (pin "P$5") (pinfunction "P$5_P$5") (pintype "bidirectional"))
    )
    (net (code "142") (name "Net-(S213-PadP$1)") (class "Default")
      (node (ref "S213") (pin "P$1") (pinfunction "P$1_P$1") (pintype "bidirectional"))
      (node (ref "S213") (pin "P$2") (pinfunction "P$2_P$2") (pintype "bidirectional"))
      (node (ref "S213") (pin "P$3") (pinfunction "P$3_P$3") (pintype "bidirectional"))
      (node (ref "S213") (pin "P$4") (pinfunction "P$4_P$4") (pintype "bidirectional"))
      (node (ref "S213") (pin "P$5") (pinfunction "P$5_P$5") (pintype "bidirectional"))
    )
    (net (code "143") (name "Net-(S214-PadP$1)") (class "Default")
      (node (ref "S214") (pin "P$1") (pinfunction "P$1_P$1") (pintype "bidirectional"))
      (node (ref "S214") (pin "P$2") (pinfunction "P$2_P$2") (pintype "bidirectional"))
      (node (ref "S214") (pin "P$3") (pinfunction "P$3_P$3") (pintype "bidirectional"))
      (node (ref "S214") (pin "P$4") (pinfunction "P$4_P$4") (pintype "bidirectional"))
      (node (ref "S214") (pin "P$5") (pinfunction "P$5_P$5") (pintype "bidirectional"))
    )
    (net (code "144") (name "Net-(S215-PadP$1)") (class "Default")
      (node (ref "S215") (pin "P$1") (pinfunction "P$1_P$1") (pintype "bidirectional"))
      (node (ref "S215") (pin "P$2") (pinfunction "P$2_P$2") (pintype "bidirectional"))
      (node (ref "S215") (pin "P$3") (pinfunction "P$3_P$3") (pintype "bidirectional"))
      (node (ref "S215") (pin "P$4") (pinfunction "P$4_P$4") (pintype "bidirectional"))
      (node (ref "S215") (pin "P$5") (pinfunction "P$5_P$5") (pintype "bidirectional"))
    )
    (net (code "145") (name "Net-(S216-PadP$1)") (class "Default")
      (node (ref "S216") (pin "P$1") (pinfunction "P$1_P$1") (pintype "bidirectional"))
      (node (ref "S216") (pin "P$2") (pinfunction "P$2_P$2") (pintype "bidirectional"))
      (node (ref "S216") (pin "P$3") (pinfunction "P$3_P$3") (pintype "bidirectional"))
      (node (ref "S216") (pin "P$4") (pinfunction "P$4_P$4") (pintype "bidirectional"))
      (node (ref "S216") (pin "P$5") (pinfunction "P$5_P$5") (pintype "bidirectional"))
    )
    (net (code "146") (name "Net-(S217-PadP$1)") (class "Default")
      (node (ref "S217") (pin "P$1") (pinfunction "P$1_P$1") (pintype "bidirectional"))
      (node (ref "S217") (pin "P$2") (pinfunction "P$2_P$2") (pintype "bidirectional"))
      (node (ref "S217") (pin "P$3") (pinfunction "P$3_P$3") (pintype "bidirectional"))
      (node (ref "S217") (pin "P$4") (pinfunction "P$4_P$4") (pintype "bidirectional"))
      (node (ref "S217") (pin "P$5") (pinfunction "P$5_P$5") (pintype "bidirectional"))
    )
    (net (code "147") (name "Net-(S218-PadP$1)") (class "Default")
      (node (ref "S218") (pin "P$1") (pinfunction "P$1_P$1") (pintype "bidirectional"))
      (node (ref "S218") (pin "P$2") (pinfunction "P$2_P$2") (pintype "bidirectional"))
      (node (ref "S218") (pin "P$3") (pinfunction "P$3_P$3") (pintype "bidirectional"))
      (node (ref "S218") (pin "P$4") (pinfunction "P$4_P$4") (pintype "bidirectional"))
      (node (ref "S218") (pin "P$5") (pinfunction "P$5_P$5") (pintype "bidirectional"))
    )
    (net (code "148") (name "Net-(S219-PadP$1)") (class "Default")
      (node (ref "S219") (pin "P$1") (pinfunction "P$1_P$1") (pintype "bidirectional"))
      (node (ref "S219") (pin "P$2") (pinfunction "P$2_P$2") (pintype "bidirectional"))
      (node (ref "S219") (pin "P$3") (pinfunction "P$3_P$3") (pintype "bidirectional"))
      (node (ref "S219") (pin "P$4") (pinfunction "P$4_P$4") (pintype "bidirectional"))
      (node (ref "S219") (pin "P$5") (pinfunction "P$5_P$5") (pintype "bidirectional"))
    )
    (net (code "149") (name "Net-(S220-PadP$1)") (class "Default")
      (node (ref "S220") (pin "P$1") (pinfunction "P$1_P$1") (pintype "bidirectional"))
      (node (ref "S220") (pin "P$2") (pinfunction "P$2_P$2") (pintype "bidirectional"))
      (node (ref "S220") (pin "P$3") (pinfunction "P$3_P$3") (pintype "bidirectional"))
      (node (ref "S220") (pin "P$4") (pinfunction "P$4_P$4") (pintype "bidirectional"))
      (node (ref "S220") (pin "P$5") (pinfunction "P$5_P$5") (pintype "bidirectional"))
    )
    (net (code "150") (name "Net-(S221-PadP$1)") (class "Default")
      (node (ref "S221") (pin "P$1") (pinfunction "P$1_P$1") (pintype "bidirectional"))
      (node (ref "S221") (pin "P$2") (pinfunction "P$2_P$2") (pintype "bidirectional"))
      (node (ref "S221") (pin "P$3") (pinfunction "P$3_P$3") (pintype "bidirectional"))
      (node (ref "S221") (pin "P$4") (pinfunction "P$4_P$4") (pintype "bidirectional"))
      (node (ref "S221") (pin "P$5") (pinfunction "P$5_P$5") (pintype "bidirectional"))
    )
    (net (code "151") (name "Net-(S222-PadP$1)") (class "Default")
      (node (ref "S222") (pin "P$1") (pinfunction "P$1_P$1") (pintype "bidirectional"))
      (node (ref "S222") (pin "P$2") (pinfunction "P$2_P$2") (pintype "bidirectional"))
      (node (ref "S222") (pin "P$3") (pinfunction "P$3_P$3") (pintype "bidirectional"))
      (node (ref "S222") (pin "P$4") (pinfunction "P$4_P$4") (pintype "bidirectional"))
      (node (ref "S222") (pin "P$5") (pinfunction "P$5_P$5") (pintype "bidirectional"))
    )
    (net (code "152") (name "Net-(S223-PadP$1)") (class "Default")
      (node (ref "S223") (pin "P$1") (pinfunction "P$1_P$1") (pintype "bidirectional"))
      (node (ref "S223") (pin "P$2") (pinfunction "P$2_P$2") (pintype "bidirectional"))
      (node (ref "S223") (pin "P$3") (pinfunction "P$3_P$3") (pintype "bidirectional"))
      (node (ref "S223") (pin "P$4") (pinfunction "P$4_P$4") (pintype "bidirectional"))
      (node (ref "S223") (pin "P$5") (pinfunction "P$5_P$5") (pintype "bidirectional"))
    )
    (net (code "153") (name "Net-(S224-PadP$1)") (class "Default")
      (node (ref "S224") (pin "P$1") (pinfunction "P$1_P$1") (pintype "bidirectional"))
      (node (ref "S224") (pin "P$2") (pinfunction "P$2_P$2") (pintype "bidirectional"))
      (node (ref "S224") (pin "P$3") (pinfunction "P$3_P$3") (pintype "bidirectional"))
      (node (ref "S224") (pin "P$4") (pinfunction "P$4_P$4") (pintype "bidirectional"))
      (node (ref "S224") (pin "P$5") (pinfunction "P$5_P$5") (pintype "bidirectional"))
    )
    (net (code "154") (name "Net-(S225-PadP$1)") (class "Default")
      (node (ref "S225") (pin "P$1") (pinfunction "P$1_P$1") (pintype "bidirectional"))
      (node (ref "S225") (pin "P$2") (pinfunction "P$2_P$2") (pintype "bidirectional"))
      (node (ref "S225") (pin "P$3") (pinfunction "P$3_P$3") (pintype "bidirectional"))
      (node (ref "S225") (pin "P$4") (pinfunction "P$4_P$4") (pintype "bidirectional"))
      (node (ref "S225") (pin "P$5") (pinfunction "P$5_P$5") (pintype "bidirectional"))
    )
    (net (code "155") (name "Net-(S226-PadP$1)") (class "Default")
      (node (ref "S226") (pin "P$1") (pinfunction "P$1_P$1") (pintype "bidirectional"))
      (node (ref "S226") (pin "P$2") (pinfunction "P$2_P$2") (pintype "bidirectional"))
      (node (ref "S226") (pin "P$3") (pinfunction "P$3_P$3") (pintype "bidirectional"))
      (node (ref "S226") (pin "P$4") (pinfunction "P$4_P$4") (pintype "bidirectional"))
      (node (ref "S226") (pin "P$5") (pinfunction "P$5_P$5") (pintype "bidirectional"))
    )
    (net (code "156") (name "Net-(SV2-Pad7)") (class "Default")
      (node (ref "SV2") (pin "7") (pinfunction "7_7") (pintype "passive"))
      (node (ref "SV2") (pin "8") (pinfunction "8_8") (pintype "passive"))
    )
    (net (code "157") (name "Net-(SV2-Pad10)") (class "Default")
      (node (ref "SV2") (pin "10") (pinfunction "10_10") (pintype "passive"))
      (node (ref "SV2") (pin "9") (pinfunction "9_9") (pintype "passive"))
    )
    (net (code "158") (name "Net-(SV2-Pad11)") (class "Default")
      (node (ref "SV2") (pin "11") (pinfunction "11_11") (pintype "passive"))
      (node (ref "SV2") (pin "12") (pinfunction "12_12") (pintype "passive"))
    )
    (net (code "159") (name "Net-(SV2-Pad15)") (class "Default")
      (node (ref "SV2") (pin "15") (pinfunction "15_15") (pintype "passive"))
      (node (ref "SV2") (pin "16") (pinfunction "16_16") (pintype "passive"))
    )
    (net (code "160") (name "Net-(SV2-Pad17)") (class "Default")
      (node (ref "SV2") (pin "17") (pinfunction "17_17") (pintype "passive"))
      (node (ref "SV2") (pin "18") (pinfunction "18_18") (pintype "passive"))
    )
    (net (code "161") (name "Net-(SV2-Pad21)") (class "Default")
      (node (ref "SV2") (pin "21") (pinfunction "21_21") (pintype "passive"))
      (node (ref "SV2") (pin "22") (pinfunction "22_22") (pintype "passive"))
    )
    (net (code "162") (name "Net-(SV2-Pad23)") (class "Default")
      (node (ref "SV2") (pin "23") (pinfunction "23_23") (pintype "passive"))
      (node (ref "SV2") (pin "24") (pinfunction "24_24") (pintype "passive"))
    )
    (net (code "163") (name "Net-(SV2-Pad25)") (class "Default")
      (node (ref "SV2") (pin "25") (pinfunction "25_25") (pintype "passive"))
      (node (ref "SV2") (pin "26") (pinfunction "26_26") (pintype "passive"))
    )
    (net (code "164") (name "Net-(SV2-Pad27)") (class "Default")
      (node (ref "SV2") (pin "27") (pinfunction "27_27") (pintype "passive"))
      (node (ref "SV2") (pin "28") (pinfunction "28_28") (pintype "passive"))
    )
    (net (code "165") (name "Net-(SV2-Pad31)") (class "Default")
      (node (ref "SV2") (pin "31") (pinfunction "31_31") (pintype "passive"))
      (node (ref "SV2") (pin "32") (pinfunction "32_32") (pintype "passive"))
    )
    (net (code "166") (name "Net-(SV2-Pad35)") (class "Default")
      (node (ref "SV2") (pin "35") (pinfunction "35_35") (pintype "passive"))
      (node (ref "SV2") (pin "36") (pinfunction "36_36") (pintype "passive"))
    )
    (net (code "167") (name "Net-(SV2-Pad37)") (class "Default")
      (node (ref "SV2") (pin "37") (pinfunction "37_37") (pintype "passive"))
      (node (ref "SV2") (pin "38") (pinfunction "38_38") (pintype "passive"))
    )
    (net (code "168") (name "Net-(SV2-Pad39)") (class "Default")
      (node (ref "SV2") (pin "39") (pinfunction "39_39") (pintype "passive"))
      (node (ref "SV2") (pin "40") (pinfunction "40_40") (pintype "passive"))
    )
    (net (code "169") (name "Net-(SV4-Pad1)") (class "Default")
      (node (ref "SV4") (pin "1") (pinfunction "1_1") (pintype "passive"))
      (node (ref "SV4") (pin "2") (pinfunction "2_2") (pintype "passive"))
    )
    (net (code "170") (name "Net-(SV4-Pad3)") (class "Default")
      (node (ref "SV4") (pin "3") (pinfunction "3_3") (pintype "passive"))
      (node (ref "SV4") (pin "4") (pinfunction "4_4") (pintype "passive"))
    )
    (net (code "171") (name "Net-(SV4-Pad5)") (class "Default")
      (node (ref "SV4") (pin "5") (pinfunction "5_5") (pintype "passive"))
      (node (ref "SV4") (pin "6") (pinfunction "6_6") (pintype "passive"))
    )
    (net (code "172") (name "Net-(SV4-Pad7)") (class "Default")
      (node (ref "SV4") (pin "7") (pinfunction "7_7") (pintype "passive"))
      (node (ref "SV4") (pin "8") (pinfunction "8_8") (pintype "passive"))
    )
    (net (code "173") (name "Net-(SV4-Pad11)") (class "Default")
      (node (ref "SV4") (pin "11") (pinfunction "11_11") (pintype "passive"))
      (node (ref "SV4") (pin "12") (pinfunction "12_12") (pintype "passive"))
    )
    (net (code "174") (name "Net-(SV4-Pad13)") (class "Default")
      (node (ref "SV4") (pin "13") (pinfunction "13_13") (pintype "passive"))
      (node (ref "SV4") (pin "14") (pinfunction "14_14") (pintype "passive"))
    )
    (net (code "175") (name "Net-(SV4-Pad15)") (class "Default")
      (node (ref "SV4") (pin "15") (pinfunction "15_15") (pintype "passive"))
      (node (ref "SV4") (pin "16") (pinfunction "16_16") (pintype "passive"))
    )
    (net (code "176") (name "Net-(SV4-Pad17)") (class "Default")
      (node (ref "SV4") (pin "17") (pinfunction "17_17") (pintype "passive"))
      (node (ref "SV4") (pin "18") (pinfunction "18_18") (pintype "passive"))
    )
    (net (code "177") (name "Net-(SV4-Pad19)") (class "Default")
      (node (ref "SV4") (pin "19") (pinfunction "19_19") (pintype "passive"))
      (node (ref "SV4") (pin "20") (pinfunction "20_20") (pintype "passive"))
    )
    (net (code "178") (name "Net-(SV4-Pad21)") (class "Default")
      (node (ref "SV4") (pin "21") (pinfunction "21_21") (pintype "passive"))
      (node (ref "SV4") (pin "22") (pinfunction "22_22") (pintype "passive"))
    )
    (net (code "179") (name "Net-(SV4-Pad23)") (class "Default")
      (node (ref "SV4") (pin "23") (pinfunction "23_23") (pintype "passive"))
      (node (ref "SV4") (pin "24") (pinfunction "24_24") (pintype "passive"))
    )
    (net (code "180") (name "Net-(SV4-Pad27)") (class "Default")
      (node (ref "SV4") (pin "27") (pinfunction "27_27") (pintype "passive"))
      (node (ref "SV4") (pin "28") (pinfunction "28_28") (pintype "passive"))
    )
    (net (code "181") (name "Net-(SV4-Pad29)") (class "Default")
      (node (ref "SV4") (pin "29") (pinfunction "29_29") (pintype "passive"))
      (node (ref "SV4") (pin "30") (pinfunction "30_30") (pintype "passive"))
    )
    (net (code "182") (name "Net-(SV4-Pad31)") (class "Default")
      (node (ref "SV4") (pin "31") (pinfunction "31_31") (pintype "passive"))
      (node (ref "SV4") (pin "32") (pinfunction "32_32") (pintype "passive"))
    )
    (net (code "183") (name "Net-(SV4-Pad33)") (class "Default")
      (node (ref "SV4") (pin "33") (pinfunction "33_33") (pintype "passive"))
      (node (ref "SV4") (pin "34") (pinfunction "34_34") (pintype "passive"))
    )
    (net (code "184") (name "Net-(SV4-Pad35)") (class "Default")
      (node (ref "SV4") (pin "35") (pinfunction "35_35") (pintype "passive"))
      (node (ref "SV4") (pin "36") (pinfunction "36_36") (pintype "passive"))
    )
    (net (code "185") (name "Net-(SV4-Pad37)") (class "Default")
      (node (ref "SV4") (pin "37") (pinfunction "37_37") (pintype "passive"))
      (node (ref "SV4") (pin "38") (pinfunction "38_38") (pintype "passive"))
    )
    (net (code "186") (name "Net-(SV6-Pad1)") (class "Default")
      (node (ref "SV6") (pin "1") (pinfunction "1_1") (pintype "passive"))
      (node (ref "SV6") (pin "2") (pinfunction "2_2") (pintype "passive"))
    )
    (net (code "187") (name "Net-(SV6-Pad3)") (class "Default")
      (node (ref "SV6") (pin "3") (pinfunction "3_3") (pintype "passive"))
      (node (ref "SV6") (pin "4") (pinfunction "4_4") (pintype "passive"))
    )
    (net (code "188") (name "Net-(SV6-Pad5)") (class "Default")
      (node (ref "SV6") (pin "5") (pinfunction "5_5") (pintype "passive"))
      (node (ref "SV6") (pin "6") (pinfunction "6_6") (pintype "passive"))
    )
    (net (code "189") (name "Net-(SV6-Pad7)") (class "Default")
      (node (ref "SV6") (pin "7") (pinfunction "7_7") (pintype "passive"))
      (node (ref "SV6") (pin "8") (pinfunction "8_8") (pintype "passive"))
    )
    (net (code "190") (name "Net-(SV6-Pad10)") (class "Default")
      (node (ref "SV6") (pin "10") (pinfunction "10_10") (pintype "passive"))
      (node (ref "SV6") (pin "9") (pinfunction "9_9") (pintype "passive"))
    )
    (net (code "191") (name "Net-(SV6-Pad13)") (class "Default")
      (node (ref "SV6") (pin "13") (pinfunction "13_13") (pintype "passive"))
      (node (ref "SV6") (pin "14") (pinfunction "14_14") (pintype "passive"))
    )
    (net (code "192") (name "Net-(SV6-Pad15)") (class "Default")
      (node (ref "SV6") (pin "15") (pinfunction "15_15") (pintype "passive"))
      (node (ref "SV6") (pin "16") (pinfunction "16_16") (pintype "passive"))
    )
    (net (code "193") (name "Net-(SV17-Pad5)") (class "Default")
      (node (ref "SV17") (pin "5") (pinfunction "5_5") (pintype "passive"))
      (node (ref "SV17") (pin "6") (pinfunction "6_6") (pintype "passive"))
    )
    (net (code "194") (name "Net-(SV17-Pad7)") (class "Default")
      (node (ref "SV17") (pin "7") (pinfunction "7_7") (pintype "passive"))
      (node (ref "SV17") (pin "8") (pinfunction "8_8") (pintype "passive"))
    )
    (net (code "195") (name "Net-(SV17-Pad11)") (class "Default")
      (node (ref "SV17") (pin "11") (pinfunction "11_11") (pintype "passive"))
      (node (ref "SV17") (pin "12") (pinfunction "12_12") (pintype "passive"))
    )
    (net (code "196") (name "Net-(SV17-Pad15)") (class "Default")
      (node (ref "SV17") (pin "15") (pinfunction "15_15") (pintype "passive"))
      (node (ref "SV17") (pin "16") (pinfunction "16_16") (pintype "passive"))
    )
    (net (code "197") (name "Net-(SV17-Pad17)") (class "Default")
      (node (ref "SV17") (pin "17") (pinfunction "17_17") (pintype "passive"))
      (node (ref "SV17") (pin "18") (pinfunction "18_18") (pintype "passive"))
    )
    (net (code "198") (name "Net-(T1-B)") (class "Default")
      (node (ref "R1") (pin "2") (pinfunction "2_2") (pintype "passive"))
      (node (ref "T1") (pin "1") (pinfunction "B_1") (pintype "passive"))
    )
    (net (code "199") (name "Net-(T1-C)") (class "Default")
      (node (ref "J4") (pin "P$1") (pinfunction "P$1_P$1") (pintype "bidirectional"))
      (node (ref "J4") (pin "P$2") (pinfunction "P$2_P$2") (pintype "bidirectional"))
      (node (ref "J4") (pin "P$3") (pinfunction "P$3_P$3") (pintype "bidirectional"))
      (node (ref "T1") (pin "2") (pinfunction "C_2") (pintype "passive"))
    )
    (net (code "200") (name "Net-(T2-B)") (class "Default")
      (node (ref "R2") (pin "2") (pinfunction "2_2") (pintype "passive"))
      (node (ref "T2") (pin "1") (pinfunction "B_1") (pintype "passive"))
    )
    (net (code "201") (name "Net-(T2-C)") (class "Default")
      (node (ref "J23") (pin "P$1") (pinfunction "P$1_P$1") (pintype "bidirectional"))
      (node (ref "J23") (pin "P$2") (pinfunction "P$2_P$2") (pintype "bidirectional"))
      (node (ref "J23") (pin "P$3") (pinfunction "P$3_P$3") (pintype "bidirectional"))
      (node (ref "T2") (pin "2") (pinfunction "C_2") (pintype "passive"))
    )
    (net (code "202") (name "Net-(U$1-P3_SCLK)") (class "Default")
      (node (ref "J125") (pin "P$1") (pinfunction "P$1_P$1") (pintype "bidirectional"))
      (node (ref "J125") (pin "P$2") (pinfunction "P$2_P$2") (pintype "bidirectional"))
      (node (ref "J125") (pin "P$3") (pinfunction "P$3_P$3") (pintype "bidirectional"))
      (node (ref "U$1") (pin "3") (pinfunction "P3_SCLK_3") (pintype "bidirectional"))
    )
    (net (code "203") (name "Net-(U$1-P4_SDA{slash}SPIMOSI)") (class "Default")
      (node (ref "J126") (pin "P$1") (pinfunction "P$1_P$1") (pintype "bidirectional"))
      (node (ref "J126") (pin "P$2") (pinfunction "P$2_P$2") (pintype "bidirectional"))
      (node (ref "J126") (pin "P$3") (pinfunction "P$3_P$3") (pintype "bidirectional"))
      (node (ref "U$1") (pin "4") (pinfunction "P4_SDA/SPIMOSI_4") (pintype "bidirectional"))
    )
    (net (code "204") (name "Net-(U$1-P5_EDA{slash}AUX-DA)") (class "Default")
      (node (ref "J127") (pin "P$1") (pinfunction "P$1_P$1") (pintype "bidirectional"))
      (node (ref "J127") (pin "P$2") (pinfunction "P$2_P$2") (pintype "bidirectional"))
      (node (ref "J127") (pin "P$3") (pinfunction "P$3_P$3") (pintype "bidirectional"))
      (node (ref "U$1") (pin "5") (pinfunction "P5_EDA/AUX-DA_5") (pintype "bidirectional"))
    )
    (net (code "205") (name "Net-(U$1-P6_ECL{slash}AUX-CL)") (class "Default")
      (node (ref "J128") (pin "P$1") (pinfunction "P$1_P$1") (pintype "bidirectional"))
      (node (ref "J128") (pin "P$2") (pinfunction "P$2_P$2") (pintype "bidirectional"))
      (node (ref "J128") (pin "P$3") (pinfunction "P$3_P$3") (pintype "bidirectional"))
      (node (ref "U$1") (pin "6") (pinfunction "P6_ECL/AUX-CL_6") (pintype "bidirectional"))
    )
    (net (code "206") (name "Net-(U$1-P7_ADO{slash}SPIMISO)") (class "Default")
      (node (ref "J129") (pin "P$1") (pinfunction "P$1_P$1") (pintype "bidirectional"))
      (node (ref "J129") (pin "P$2") (pinfunction "P$2_P$2") (pintype "bidirectional"))
      (node (ref "J129") (pin "P$3") (pinfunction "P$3_P$3") (pintype "bidirectional"))
      (node (ref "U$1") (pin "7") (pinfunction "P7_ADO/SPIMISO_7") (pintype "bidirectional"))
    )
    (net (code "207") (name "Net-(U$1-P8_INT)") (class "Default")
      (node (ref "J130") (pin "P$1") (pinfunction "P$1_P$1") (pintype "bidirectional"))
      (node (ref "J130") (pin "P$2") (pinfunction "P$2_P$2") (pintype "bidirectional"))
      (node (ref "J130") (pin "P$3") (pinfunction "P$3_P$3") (pintype "bidirectional"))
      (node (ref "U$1") (pin "8") (pinfunction "P8_INT_8") (pintype "bidirectional"))
    )
    (net (code "208") (name "Net-(U$1-P9_NCS)") (class "Default")
      (node (ref "J131") (pin "P$1") (pinfunction "P$1_P$1") (pintype "bidirectional"))
      (node (ref "J131") (pin "P$2") (pinfunction "P$2_P$2") (pintype "bidirectional"))
      (node (ref "J131") (pin "P$3") (pinfunction "P$3_P$3") (pintype "bidirectional"))
      (node (ref "U$1") (pin "9") (pinfunction "P9_NCS_9") (pintype "bidirectional"))
    )
    (net (code "209") (name "Net-(U$1-P10_FSYNC)") (class "Default")
      (node (ref "J132") (pin "P$1") (pinfunction "P$1_P$1") (pintype "bidirectional"))
      (node (ref "J132") (pin "P$2") (pinfunction "P$2_P$2") (pintype "bidirectional"))
      (node (ref "J132") (pin "P$3") (pinfunction "P$3_P$3") (pintype "bidirectional"))
      (node (ref "U$1") (pin "10") (pinfunction "P10_FSYNC_10") (pintype "bidirectional"))
    )
    (net (code "210") (name "Net-(U1-MODE)") (class "Default")
      (node (ref "JP2") (pin "1") (pinfunction "1_1") (pintype "passive"))
      (node (ref "R4") (pin "1") (pinfunction "1_1") (pintype "passive"))
      (node (ref "U1") (pin "14") (pinfunction "MODE_14") (pintype "bidirectional"))
    )
    (net (code "211") (name "Net-(U1-PHASE)") (class "Default")
      (node (ref "J196") (pin "P$1") (pinfunction "P$1_P$1") (pintype "bidirectional"))
      (node (ref "J196") (pin "P$2") (pinfunction "P$2_P$2") (pintype "bidirectional"))
      (node (ref "U1") (pin "7") (pinfunction "PHASE_7") (pintype "bidirectional"))
    )
    (net (code "212") (name "Net-(U1-RC)") (class "Default")
      (node (ref "C14") (pin "1") (pinfunction "1_1") (pintype "passive"))
      (node (ref "R3") (pin "2") (pinfunction "2_2") (pintype "passive"))
      (node (ref "U1") (pin "3") (pinfunction "RC_3") (pintype "bidirectional"))
    )
    (net (code "213") (name "Net-(U1-~{BRAKE})") (class "Default")
      (node (ref "R8") (pin "1") (pinfunction "1_1") (pintype "passive"))
      (node (ref "U1") (pin "1") (pinfunction "~{BRAKE}_1") (pintype "bidirectional"))
    )
    (net (code "214") (name "Net-(U2-CPH)") (class "Default")
      (node (ref "C19") (pin "2") (pinfunction "2_2") (pintype "passive"))
      (node (ref "U2") (pin "P$13") (pinfunction "CPH_P$13") (pintype "bidirectional"))
    )
    (net (code "215") (name "Net-(U2-CPL)") (class "Default")
      (node (ref "C19") (pin "1") (pinfunction "1_1") (pintype "passive"))
      (node (ref "U2") (pin "P$14") (pinfunction "CPL_P$14") (pintype "bidirectional"))
    )
    (net (code "216") (name "Net-(U2-IPROPI)") (class "Default")
      (node (ref "R41") (pin "1") (pinfunction "1_1") (pintype "passive"))
      (node (ref "U2") (pin "P$6") (pinfunction "IPROPI_P$6") (pintype "bidirectional"))
    )
    (net (code "217") (name "Net-(U2-NFAULT)") (class "Default")
      (node (ref "J78") (pin "P$1") (pinfunction "P$1_P$1") (pintype "bidirectional"))
      (node (ref "J78") (pin "P$2") (pinfunction "P$2_P$2") (pintype "bidirectional"))
      (node (ref "R42") (pin "2") (pinfunction "2_2") (pintype "passive"))
      (node (ref "U2") (pin "P$4") (pinfunction "NFAULT_P$4") (pintype "bidirectional"))
    )
    (net (code "218") (name "Net-(U2-VCP)") (class "Default")
      (node (ref "C17") (pin "1") (pinfunction "1_1") (pintype "passive"))
      (node (ref "U2") (pin "P$12") (pinfunction "VCP_P$12") (pintype "bidirectional"))
    )
    (net (code "219") (name "Net-(U2-VREF)") (class "Default")
      (node (ref "TRIMPOT1") (pin "3") (pinfunction "3_3") (pintype "passive"))
      (node (ref "TRIMPOT1") (pin "4") (pinfunction "4_4") (pintype "passive"))
      (node (ref "U2") (pin "P$5") (pinfunction "VREF_P$5") (pintype "bidirectional"))
    )
    (net (code "220") (name "Net-(U3-P1_OSCI)") (class "Default")
      (node (ref "Q1") (pin "2") (pinfunction "2_2") (pintype "passive"))
      (node (ref "U3") (pin "1") (pinfunction "P1_OSCI_1") (pintype "bidirectional"))
    )
    (net (code "221") (name "Net-(U3-P2_OSC0)") (class "Default")
      (node (ref "Q1") (pin "1") (pinfunction "1_1") (pintype "passive"))
      (node (ref "U3") (pin "2") (pinfunction "P2_OSC0_2") (pintype "bidirectional"))
    )
    (net (code "222") (name "Net-(U3-P3_VBACK)") (class "Default")
      (node (ref "G1") (pin "+") (pinfunction "+_+") (pintype "passive"))
      (node (ref "U3") (pin "3") (pinfunction "P3_VBACK_3") (pintype "bidirectional"))
    )
    (net (code "223") (name "Net-(U3-P7_IRQ)") (class "Default")
      (node (ref "J1") (pin "P$1") (pinfunction "P$1_P$1") (pintype "bidirectional"))
      (node (ref "J1") (pin "P$2") (pinfunction "P$2_P$2") (pintype "bidirectional"))
      (node (ref "J1") (pin "P$3") (pinfunction "P$3_P$3") (pintype "bidirectional"))
      (node (ref "U3") (pin "7") (pinfunction "P7_IRQ_7") (pintype "bidirectional"))
    )
    (net (code "224") (name "Net-(U4-CPH)") (class "Default")
      (node (ref "C24") (pin "2") (pinfunction "2_2") (pintype "passive"))
      (node (ref "U4") (pin "P$13") (pinfunction "CPH_P$13") (pintype "bidirectional"))
    )
    (net (code "225") (name "Net-(U4-CPL)") (class "Default")
      (node (ref "C24") (pin "1") (pinfunction "1_1") (pintype "passive"))
      (node (ref "U4") (pin "P$14") (pinfunction "CPL_P$14") (pintype "bidirectional"))
    )
    (net (code "226") (name "Net-(U4-IPROPI)") (class "Default")
      (node (ref "R43") (pin "1") (pinfunction "1_1") (pintype "passive"))
      (node (ref "U4") (pin "P$6") (pinfunction "IPROPI_P$6") (pintype "bidirectional"))
    )
    (net (code "227") (name "Net-(U4-NFAULT)") (class "Default")
      (node (ref "J81") (pin "P$1") (pinfunction "P$1_P$1") (pintype "bidirectional"))
      (node (ref "J81") (pin "P$2") (pinfunction "P$2_P$2") (pintype "bidirectional"))
      (node (ref "R44") (pin "2") (pinfunction "2_2") (pintype "passive"))
      (node (ref "U4") (pin "P$4") (pinfunction "NFAULT_P$4") (pintype "bidirectional"))
    )
    (net (code "228") (name "Net-(U4-VCP)") (class "Default")
      (node (ref "C23") (pin "1") (pinfunction "1_1") (pintype "passive"))
      (node (ref "U4") (pin "P$12") (pinfunction "VCP_P$12") (pintype "bidirectional"))
    )
    (net (code "229") (name "Net-(U4-VREF)") (class "Default")
      (node (ref "TRIMPOT2") (pin "3") (pinfunction "3_3") (pintype "passive"))
      (node (ref "TRIMPOT2") (pin "4") (pinfunction "4_4") (pintype "passive"))
      (node (ref "U4") (pin "P$5") (pinfunction "VREF_P$5") (pintype "bidirectional"))
    )
    (net (code "230") (name "Net-(U5-MODE)") (class "Default")
      (node (ref "JP3") (pin "1") (pinfunction "1_1") (pintype "passive"))
      (node (ref "R5") (pin "1") (pinfunction "1_1") (pintype "passive"))
      (node (ref "U5") (pin "14") (pinfunction "MODE_14") (pintype "bidirectional"))
    )
    (net (code "231") (name "Net-(U5-PHASE)") (class "Default")
      (node (ref "J197") (pin "P$1") (pinfunction "P$1_P$1") (pintype "bidirectional"))
      (node (ref "J197") (pin "P$2") (pinfunction "P$2_P$2") (pintype "bidirectional"))
      (node (ref "U5") (pin "7") (pinfunction "PHASE_7") (pintype "bidirectional"))
    )
    (net (code "232") (name "Net-(U5-RC)") (class "Default")
      (node (ref "C2") (pin "1") (pinfunction "1_1") (pintype "passive"))
      (node (ref "R7") (pin "2") (pinfunction "2_2") (pintype "passive"))
      (node (ref "U5") (pin "3") (pinfunction "RC_3") (pintype "bidirectional"))
    )
    (net (code "233") (name "Net-(U5-~{BRAKE})") (class "Default")
      (node (ref "R6") (pin "1") (pinfunction "1_1") (pintype "passive"))
      (node (ref "U5") (pin "1") (pinfunction "~{BRAKE}_1") (pintype "bidirectional"))
    )
    (net (code "234") (name "Net-(U6-IN3)") (class "Default")
      (node (ref "SV10") (pin "3") (pinfunction "3_3") (pintype "passive"))
      (node (ref "U6") (pin "P$3") (pinfunction "IN3_P$3") (pintype "bidirectional"))
    )
    (net (code "235") (name "Net-(U6-OUT1)") (class "Default")
      (node (ref "SV9") (pin "1") (pinfunction "1_1") (pintype "passive"))
      (node (ref "U6") (pin "P$7") (pinfunction "OUT1_P$7") (pintype "bidirectional"))
    )
    (net (code "236") (name "Net-(U6-OUT2)") (class "Default")
      (node (ref "SV9") (pin "2") (pinfunction "2_2") (pintype "passive"))
      (node (ref "U6") (pin "P$6") (pinfunction "OUT2_P$6") (pintype "bidirectional"))
    )
    (net (code "237") (name "Net-(U6-OUT3)") (class "Default")
      (node (ref "SV9") (pin "3") (pinfunction "3_3") (pintype "passive"))
      (node (ref "U6") (pin "P$5") (pinfunction "OUT3_P$5") (pintype "bidirectional"))
    )
    (net (code "238") (name "Net-(U8-VDD)") (class "Default")
      (node (ref "C11") (pin "1") (pinfunction "1_1") (pintype "passive"))
      (node (ref "U8") (pin "1") (pinfunction "VDD_1") (pintype "bidirectional"))
    )
    (net (code "239") (name "Net-(U8-VDD2)") (class "Default")
      (node (ref "C8") (pin "1") (pinfunction "1_1") (pintype "passive"))
      (node (ref "U8") (pin "11") (pinfunction "VDD2_11") (pintype "bidirectional"))
    )
    (net (code "240") (name "Net-(U8-{slash}XRS)") (class "Default")
      (node (ref "P1") (pin "1") (pinfunction "1_1") (pintype "bidirectional"))
      (node (ref "R38") (pin "1") (pinfunction "1_1") (pintype "passive"))
      (node (ref "U8") (pin "17") (pinfunction "/XRS_17") (pintype "bidirectional"))
    )
    (net (code "241") (name "Net-(U11-VDD)") (class "Default")
      (node (ref "C32") (pin "1") (pinfunction "1_1") (pintype "passive"))
      (node (ref "U11") (pin "1") (pinfunction "VDD_1") (pintype "bidirectional"))
    )
    (net (code "242") (name "Net-(U11-VDD2)") (class "Default")
      (node (ref "C29") (pin "1") (pinfunction "1_1") (pintype "passive"))
      (node (ref "U11") (pin "11") (pinfunction "VDD2_11") (pintype "bidirectional"))
    )
    (net (code "243") (name "Net-(U11-{slash}XRS)") (class "Default")
      (node (ref "P2") (pin "1") (pinfunction "1_1") (pintype "bidirectional"))
      (node (ref "R50") (pin "1") (pinfunction "1_1") (pintype "passive"))
      (node (ref "U11") (pin "17") (pinfunction "/XRS_17") (pintype "bidirectional"))
    )
    (net (code "244") (name "POWER") (class "Default")
      (node (ref "B2") (pin "P$1") (pinfunction "BAT+_P$1") (pintype "bidirectional"))
      (node (ref "C1") (pin "+") (pinfunction "+_+") (pintype "passive"))
      (node (ref "C12") (pin "+") (pinfunction "+_+") (pintype "passive"))
      (node (ref "C13") (pin "+") (pinfunction "+_+") (pintype "passive"))
      (node (ref "C15") (pin "+") (pinfunction "+_+") (pintype "passive"))
      (node (ref "C16") (pin "1") (pinfunction "1_1") (pintype "passive"))
      (node (ref "C17") (pin "2") (pinfunction "2_2") (pintype "passive"))
      (node (ref "C20") (pin "+") (pinfunction "+_+") (pintype "passive"))
      (node (ref "C22") (pin "1") (pinfunction "1_1") (pintype "passive"))
      (node (ref "C23") (pin "2") (pinfunction "2_2") (pintype "passive"))
      (node (ref "C25") (pin "+") (pinfunction "+_+") (pintype "passive"))
      (node (ref "C27") (pin "+") (pinfunction "+_+") (pintype "passive"))
      (node (ref "C28") (pin "+") (pinfunction "+_+") (pintype "passive"))
      (node (ref "DCDC3.3V") (pin "1") (pinfunction "1_1") (pintype "passive"))
      (node (ref "DCDC5V") (pin "1") (pinfunction "1_1") (pintype "passive"))
      (node (ref "J5") (pin "1") (pinfunction "1_1") (pintype "passive"))
      (node (ref "POWER") (pin "2") (pinfunction "2_2") (pintype "passive"))
      (node (ref "S141") (pin "P$1") (pinfunction "P$1_P$1") (pintype "bidirectional"))
      (node (ref "S141") (pin "P$2") (pinfunction "P$2_P$2") (pintype "bidirectional"))
      (node (ref "S141") (pin "P$3") (pinfunction "P$3_P$3") (pintype "bidirectional"))
      (node (ref "S141") (pin "P$4") (pinfunction "P$4_P$4") (pintype "bidirectional"))
      (node (ref "S141") (pin "P$5") (pinfunction "P$5_P$5") (pintype "bidirectional"))
      (node (ref "U1") (pin "16") (pinfunction "VBB_16") (pintype "bidirectional"))
      (node (ref "U1") (pin "9") (pinfunction "VBB_9") (pintype "bidirectional"))
      (node (ref "U2") (pin "P$11") (pinfunction "VM_P$11") (pintype "bidirectional"))
      (node (ref "U4") (pin "P$11") (pinfunction "VM_P$11") (pintype "bidirectional"))
      (node (ref "U5") (pin "16") (pinfunction "VBB_16") (pintype "bidirectional"))
      (node (ref "U5") (pin "9") (pinfunction "VBB_9") (pintype "bidirectional"))
    )
    (net (code "245") (name "RXD") (class "Default")
      (node (ref "J31") (pin "P$2") (pinfunction "P$2_P$2") (pintype "bidirectional"))
      (node (ref "SV17") (pin "10") (pinfunction "10_10") (pintype "passive"))
      (node (ref "SV17") (pin "9") (pinfunction "9_9") (pintype "passive"))
    )
    (net (code "246") (name "SCK_5V") (class "Default")
      (node (ref "IC2") (pin "22") (pinfunction "A5_22") (pintype "bidirectional"))
      (node (ref "U12") (pin "5") (pinfunction "SCK_5") (pintype "bidirectional"))
      (node (ref "U7") (pin "5") (pinfunction "SCK_5") (pintype "bidirectional"))
    )
    (net (code "247") (name "SCL") (class "Default")
      (node (ref "J2") (pin "P$1") (pinfunction "P$1_P$1") (pintype "bidirectional"))
      (node (ref "J2") (pin "P$2") (pinfunction "P$2_P$2") (pintype "bidirectional"))
      (node (ref "J2") (pin "P$3") (pinfunction "P$3_P$3") (pintype "bidirectional"))
      (node (ref "U3") (pin "6") (pinfunction "P6_SCL_6") (pintype "bidirectional"))
    )
    (net (code "248") (name "SDA") (class "Default")
      (node (ref "J3") (pin "P$1") (pinfunction "P$1_P$1") (pintype "bidirectional"))
      (node (ref "J3") (pin "P$2") (pinfunction "P$2_P$2") (pintype "bidirectional"))
      (node (ref "J3") (pin "P$3") (pinfunction "P$3_P$3") (pintype "bidirectional"))
      (node (ref "U3") (pin "5") (pinfunction "P5_SDA_5") (pintype "bidirectional"))
    )
    (net (code "249") (name "SPI1_ENCA") (class "Default")
      (node (ref "SV23") (pin "1") (pinfunction "1_1") (pintype "passive"))
      (node (ref "U7") (pin "12") (pinfunction "A_12") (pintype "bidirectional"))
    )
    (net (code "250") (name "SPI1_ENCB") (class "Default")
      (node (ref "SV23") (pin "3") (pinfunction "3_3") (pintype "passive"))
      (node (ref "U7") (pin "11") (pinfunction "B_11") (pintype "bidirectional"))
    )
    (net (code "251") (name "SPI2_ENCA") (class "Default")
      (node (ref "SV23") (pin "2") (pinfunction "2_2") (pintype "passive"))
      (node (ref "U12") (pin "12") (pinfunction "A_12") (pintype "bidirectional"))
    )
    (net (code "252") (name "SPI2_ENCB") (class "Default")
      (node (ref "SV23") (pin "4") (pinfunction "4_4") (pintype "passive"))
      (node (ref "U12") (pin "11") (pinfunction "B_11") (pintype "bidirectional"))
    )
    (net (code "253") (name "SS1_5V") (class "Default")
      (node (ref "IC2") (pin "16") (pinfunction "A2_16") (pintype "bidirectional"))
      (node (ref "U7") (pin "4") (pinfunction "SS/_4") (pintype "bidirectional"))
    )
    (net (code "254") (name "SS2_5V") (class "Default")
      (node (ref "IC2") (pin "14") (pinfunction "A1_14") (pintype "bidirectional"))
      (node (ref "U12") (pin "4") (pinfunction "SS/_4") (pintype "bidirectional"))
    )
    (net (code "255") (name "TCK") (class "Default")
      (node (ref "SV14") (pin "11") (pinfunction "11_11") (pintype "passive"))
      (node (ref "SV14") (pin "9") (pinfunction "9_9") (pintype "passive"))
      (node (ref "U8") (pin "31") (pinfunction "GPIO38/XCLKIN(TCK)_31") (pintype "bidirectional"))
    )
    (net (code "256") (name "TCK_2") (class "Default")
      (node (ref "SV16") (pin "11") (pinfunction "11_11") (pintype "passive"))
      (node (ref "SV16") (pin "9") (pinfunction "9_9") (pintype "passive"))
      (node (ref "U11") (pin "31") (pinfunction "GPIO38/XCLKIN(TCK)_31") (pintype "bidirectional"))
    )
    (net (code "257") (name "TDI") (class "Default")
      (node (ref "SV14") (pin "3") (pinfunction "3_3") (pintype "passive"))
      (node (ref "U8") (pin "28") (pinfunction "GPIO35(TDI)_28") (pintype "bidirectional"))
    )
    (net (code "258") (name "TDI_2") (class "Default")
      (node (ref "SV16") (pin "3") (pinfunction "3_3") (pintype "passive"))
      (node (ref "U11") (pin "28") (pinfunction "GPIO35(TDI)_28") (pintype "bidirectional"))
    )
    (net (code "259") (name "TDO") (class "Default")
      (node (ref "R33") (pin "2") (pinfunction "2_2") (pintype "passive"))
      (node (ref "SV14") (pin "7") (pinfunction "7_7") (pintype "passive"))
      (node (ref "U8") (pin "30") (pinfunction "GPIO37(TDO)_30") (pintype "bidirectional"))
    )
    (net (code "260") (name "TDO_2") (class "Default")
      (node (ref "J30") (pin "P$2") (pinfunction "P$2_P$2") (pintype "bidirectional"))
      (node (ref "R45") (pin "2") (pinfunction "2_2") (pintype "passive"))
      (node (ref "SV16") (pin "7") (pinfunction "7_7") (pintype "passive"))
      (node (ref "U11") (pin "30") (pinfunction "GPIO37(TDO)_30") (pintype "bidirectional"))
    )
    (net (code "261") (name "TMS") (class "Default")
      (node (ref "SV14") (pin "1") (pinfunction "1_1") (pintype "passive"))
      (node (ref "U8") (pin "29") (pinfunction "GPIO36(TMS)_29") (pintype "bidirectional"))
    )
    (net (code "262") (name "TMS_2") (class "Default")
      (node (ref "SV16") (pin "1") (pinfunction "1_1") (pintype "passive"))
      (node (ref "U11") (pin "29") (pinfunction "GPIO36(TMS)_29") (pintype "bidirectional"))
    )
    (net (code "263") (name "TRSTN") (class "Default")
      (node (ref "R32") (pin "1") (pinfunction "1_1") (pintype "passive"))
      (node (ref "SV14") (pin "2") (pinfunction "2_2") (pintype "passive"))
      (node (ref "U8") (pin "16") (pinfunction "/TRST_16") (pintype "bidirectional"))
    )
    (net (code "264") (name "TRSTN_2") (class "Default")
      (node (ref "R39") (pin "1") (pinfunction "1_1") (pintype "passive"))
      (node (ref "SV16") (pin "2") (pinfunction "2_2") (pintype "passive"))
      (node (ref "U11") (pin "16") (pinfunction "/TRST_16") (pintype "bidirectional"))
    )
    (net (code "265") (name "TXD") (class "Default")
      (node (ref "J32") (pin "P$2") (pinfunction "P$2_P$2") (pintype "bidirectional"))
      (node (ref "SV17") (pin "1") (pinfunction "1_1") (pintype "passive"))
      (node (ref "SV17") (pin "2") (pinfunction "2_2") (pintype "passive"))
    )
    (net (code "266") (name "V+") (class "Default")
      (node (ref "C9") (pin "1") (pinfunction "1_1") (pintype "passive"))
      (node (ref "J28") (pin "P$2") (pinfunction "P$2_P$2") (pintype "bidirectional"))
      (node (ref "R14") (pin "2") (pinfunction "2_2") (pintype "passive"))
      (node (ref "U9") (pin "P$1") (pinfunction "~{SHDN}_P$1") (pintype "bidirectional"))
      (node (ref "U9") (pin "P$2") (pinfunction "IN_P$2") (pintype "bidirectional"))
    )
    (net (code "267") (name "VCC") (class "Default")
      (node (ref "C10") (pin "1") (pinfunction "1_1") (pintype "passive"))
      (node (ref "C18") (pin "1") (pinfunction "1_1") (pintype "passive"))
      (node (ref "C21") (pin "1") (pinfunction "1_1") (pintype "passive"))
      (node (ref "C26") (pin "1") (pinfunction "1_1") (pintype "passive"))
      (node (ref "C3") (pin "1") (pinfunction "1_1") (pintype "passive"))
      (node (ref "C33") (pin "1") (pinfunction "1_1") (pintype "passive"))
      (node (ref "C5") (pin "1") (pinfunction "1_1") (pintype "passive"))
      (node (ref "C7") (pin "1") (pinfunction "1_1") (pintype "passive"))
      (node (ref "DCDC3.3V") (pin "3") (pinfunction "3_3") (pintype "passive"))
      (node (ref "IC3") (pin "14") (pinfunction "VCC_14") (pintype "power_in"))
      (node (ref "J123") (pin "P$1") (pinfunction "P$1_P$1") (pintype "bidirectional"))
      (node (ref "J123") (pin "P$2") (pinfunction "P$2_P$2") (pintype "bidirectional"))
      (node (ref "J123") (pin "P$3") (pinfunction "P$3_P$3") (pintype "bidirectional"))
      (node (ref "J27") (pin "P$1") (pinfunction "P$1_P$1") (pintype "bidirectional"))
      (node (ref "R10") (pin "1") (pinfunction "1_1") (pintype "passive"))
      (node (ref "R11") (pin "2") (pinfunction "2_2") (pintype "passive"))
      (node (ref "R12") (pin "1") (pinfunction "1_1") (pintype "passive"))
      (node (ref "R13") (pin "1") (pinfunction "1_1") (pintype "passive"))
      (node (ref "R18") (pin "2") (pinfunction "2_2") (pintype "passive"))
      (node (ref "R24") (pin "2") (pinfunction "2_2") (pintype "passive"))
      (node (ref "R27") (pin "2") (pinfunction "2_2") (pintype "passive"))
      (node (ref "R28") (pin "2") (pinfunction "2_2") (pintype "passive"))
      (node (ref "R29") (pin "2") (pinfunction "2_2") (pintype "passive"))
      (node (ref "R30") (pin "2") (pinfunction "2_2") (pintype "passive"))
      (node (ref "R31") (pin "2") (pinfunction "2_2") (pintype "passive"))
      (node (ref "R33") (pin "1") (pinfunction "1_1") (pintype "passive"))
      (node (ref "R34") (pin "1") (pinfunction "1_1") (pintype "passive"))
      (node (ref "R35") (pin "1") (pinfunction "1_1") (pintype "passive"))
      (node (ref "R36") (pin "2") (pinfunction "2_2") (pintype "passive"))
      (node (ref "R37") (pin "2") (pinfunction "2_2") (pintype "passive"))
      (node (ref "R38") (pin "2") (pinfunction "2_2") (pintype "passive"))
      (node (ref "R4") (pin "2") (pinfunction "2_2") (pintype "passive"))
      (node (ref "R42") (pin "1") (pinfunction "1_1") (pintype "passive"))
      (node (ref "R44") (pin "1") (pinfunction "1_1") (pintype "passive"))
      (node (ref "R45") (pin "1") (pinfunction "1_1") (pintype "passive"))
      (node (ref "R46") (pin "1") (pinfunction "1_1") (pintype "passive"))
      (node (ref "R47") (pin "1") (pinfunction "1_1") (pintype "passive"))
      (node (ref "R48") (pin "2") (pinfunction "2_2") (pintype "passive"))
      (node (ref "R49") (pin "2") (pinfunction "2_2") (pintype "passive"))
      (node (ref "R5") (pin "2") (pinfunction "2_2") (pintype "passive"))
      (node (ref "R50") (pin "2") (pinfunction "2_2") (pintype "passive"))
      (node (ref "R6") (pin "2") (pinfunction "2_2") (pintype "passive"))
      (node (ref "R8") (pin "2") (pinfunction "2_2") (pintype "passive"))
      (node (ref "R9") (pin "1") (pinfunction "1_1") (pintype "passive"))
      (node (ref "S53") (pin "P$1") (pinfunction "P$1_P$1") (pintype "bidirectional"))
      (node (ref "S53") (pin "P$10") (pinfunction "P$10_P$10") (pintype "bidirectional"))
      (node (ref "S53") (pin "P$2") (pinfunction "P$2_P$2") (pintype "bidirectional"))
      (node (ref "S53") (pin "P$3") (pinfunction "P$3_P$3") (pintype "bidirectional"))
      (node (ref "S53") (pin "P$4") (pinfunction "P$4_P$4") (pintype "bidirectional"))
      (node (ref "S53") (pin "P$5") (pinfunction "P$5_P$5") (pintype "bidirectional"))
      (node (ref "S53") (pin "P$6") (pinfunction "P$6_P$6") (pintype "bidirectional"))
      (node (ref "S53") (pin "P$7") (pinfunction "P$7_P$7") (pintype "bidirectional"))
      (node (ref "S53") (pin "P$8") (pinfunction "P$8_P$8") (pintype "bidirectional"))
      (node (ref "S53") (pin "P$9") (pinfunction "P$9_P$9") (pintype "bidirectional"))
      (node (ref "S58") (pin "P$1") (pinfunction "P$1_P$1") (pintype "bidirectional"))
      (node (ref "S58") (pin "P$10") (pinfunction "P$10_P$10") (pintype "bidirectional"))
      (node (ref "S58") (pin "P$2") (pinfunction "P$2_P$2") (pintype "bidirectional"))
      (node (ref "S58") (pin "P$3") (pinfunction "P$3_P$3") (pintype "bidirectional"))
      (node (ref "S58") (pin "P$4") (pinfunction "P$4_P$4") (pintype "bidirectional"))
      (node (ref "S58") (pin "P$5") (pinfunction "P$5_P$5") (pintype "bidirectional"))
      (node (ref "S58") (pin "P$6") (pinfunction "P$6_P$6") (pintype "bidirectional"))
      (node (ref "S58") (pin "P$7") (pinfunction "P$7_P$7") (pintype "bidirectional"))
      (node (ref "S58") (pin "P$8") (pinfunction "P$8_P$8") (pintype "bidirectional"))
      (node (ref "S58") (pin "P$9") (pinfunction "P$9_P$9") (pintype "bidirectional"))
      (node (ref "SV11") (pin "2") (pinfunction "2_2") (pintype "passive"))
      (node (ref "SV12") (pin "2") (pinfunction "2_2") (pintype "passive"))
      (node (ref "SV13") (pin "3") (pinfunction "3_3") (pintype "passive"))
      (node (ref "SV13") (pin "7") (pinfunction "7_7") (pintype "passive"))
      (node (ref "SV14") (pin "5") (pinfunction "5_5") (pintype "passive"))
      (node (ref "SV16") (pin "5") (pinfunction "5_5") (pintype "passive"))
      (node (ref "TRIMPOT1") (pin "1") (pinfunction "1_1") (pintype "passive"))
      (node (ref "TRIMPOT1") (pin "2") (pinfunction "2_2") (pintype "passive"))
      (node (ref "TRIMPOT2") (pin "1") (pinfunction "1_1") (pintype "passive"))
      (node (ref "TRIMPOT2") (pin "2") (pinfunction "2_2") (pintype "passive"))
      (node (ref "U$1") (pin "1") (pinfunction "P1_VCC_1") (pintype "bidirectional"))
      (node (ref "U1") (pin "2") (pinfunction "REF_2") (pintype "bidirectional"))
      (node (ref "U1") (pin "6") (pinfunction "VCC_6") (pintype "bidirectional"))
      (node (ref "U11") (pin "22") (pinfunction "VDDA_22") (pintype "bidirectional"))
      (node (ref "U11") (pin "4") (pinfunction "VDDIO_4") (pintype "bidirectional"))
      (node (ref "U3") (pin "8") (pinfunction "P8_VCC_8") (pintype "bidirectional"))
      (node (ref "U5") (pin "2") (pinfunction "REF_2") (pintype "bidirectional"))
      (node (ref "U5") (pin "6") (pinfunction "VCC_6") (pintype "bidirectional"))
      (node (ref "U6") (pin "P$8") (pinfunction "V+_P$8") (pintype "bidirectional"))
      (node (ref "U8") (pin "22") (pinfunction "VDDA_22") (pintype "bidirectional"))
      (node (ref "U8") (pin "4") (pinfunction "VDDIO_4") (pintype "bidirectional"))
    )
    (net (code "268") (name "unconnected-(G1-+-Pad+@1)") (class "Default")
      (node (ref "G1") (pin "+@1") (pinfunction "+_+@1") (pintype "passive"))
    )
    (net (code "269") (name "unconnected-(QG2-TS-Pad1)") (class "Default")
      (node (ref "QG2") (pin "1") (pinfunction "TS_1") (pintype "passive"))
    )
    (net (code "270") (name "unconnected-(SV12-Pad3)") (class "Default")
      (node (ref "SV12") (pin "3") (pinfunction "3_3") (pintype "passive"))
    )
    (net (code "271") (name "unconnected-(SV12-Pad5)") (class "Default")
      (node (ref "SV12") (pin "5") (pinfunction "5_5") (pintype "passive"))
    )
    (net (code "272") (name "unconnected-(SV13-Pad4)") (class "Default")
      (node (ref "SV13") (pin "4") (pinfunction "4_4") (pintype "passive"))
    )
    (net (code "273") (name "unconnected-(SV13-Pad6)") (class "Default")
      (node (ref "SV13") (pin "6") (pinfunction "6_6") (pintype "passive"))
    )
    (net (code "274") (name "unconnected-(SV14-Pad6)") (class "Default")
      (node (ref "SV14") (pin "6") (pinfunction "6_6") (pintype "passive"))
    )
    (net (code "275") (name "unconnected-(SV14-Pad13)") (class "Default")
      (node (ref "SV14") (pin "13") (pinfunction "13_13") (pintype "passive"))
    )
    (net (code "276") (name "unconnected-(SV14-Pad14)") (class "Default")
      (node (ref "SV14") (pin "14") (pinfunction "14_14") (pintype "passive"))
    )
    (net (code "277") (name "unconnected-(SV16-Pad6)") (class "Default")
      (node (ref "SV16") (pin "6") (pinfunction "6_6") (pintype "passive"))
    )
    (net (code "278") (name "unconnected-(SV16-Pad13)") (class "Default")
      (node (ref "SV16") (pin "13") (pinfunction "13_13") (pintype "passive"))
    )
    (net (code "279") (name "unconnected-(SV16-Pad14)") (class "Default")
      (node (ref "SV16") (pin "14") (pinfunction "14_14") (pintype "passive"))
    )
    (net (code "280") (name "unconnected-(SV23-Pad5)") (class "Default")
      (node (ref "SV23") (pin "5") (pinfunction "5_5") (pintype "passive"))
    )
    (net (code "281") (name "unconnected-(SV23-Pad6)") (class "Default")
      (node (ref "SV23") (pin "6") (pinfunction "6_6") (pintype "passive"))
    )
    (net (code "282") (name "unconnected-(U7-CNT_EN-Pad13)") (class "Default")
      (node (ref "U7") (pin "13") (pinfunction "CNT_EN_13") (pintype "bidirectional"))
    )
    (net (code "283") (name "unconnected-(U7-DFLAG{slash}-Pad9)") (class "Default")
      (node (ref "U7") (pin "9") (pinfunction "DFLAG/_9") (pintype "bidirectional"))
    )
    (net (code "284") (name "unconnected-(U7-FCKO-Pad1)") (class "Default")
      (node (ref "U7") (pin "1") (pinfunction "FCKO_1") (pintype "bidirectional"))
    )
    (net (code "285") (name "unconnected-(U7-INDEX{slash}-Pad10)") (class "Default")
      (node (ref "U7") (pin "10") (pinfunction "INDEX/_10") (pintype "bidirectional"))
    )
    (net (code "286") (name "unconnected-(U7-LFLAG{slash}-Pad8)") (class "Default")
      (node (ref "U7") (pin "8") (pinfunction "LFLAG/_8") (pintype "bidirectional"))
    )
    (net (code "287") (name "unconnected-(U8-TEST-Pad38)") (class "Default")
      (node (ref "U8") (pin "38") (pinfunction "TEST_38") (pintype "bidirectional"))
    )
    (net (code "288") (name "unconnected-(U11-TEST-Pad38)") (class "Default")
      (node (ref "U11") (pin "38") (pinfunction "TEST_38") (pintype "bidirectional"))
    )
    (net (code "289") (name "unconnected-(U12-CNT_EN-Pad13)") (class "Default")
      (node (ref "U12") (pin "13") (pinfunction "CNT_EN_13") (pintype "bidirectional"))
    )
    (net (code "290") (name "unconnected-(U12-DFLAG{slash}-Pad9)") (class "Default")
      (node (ref "U12") (pin "9") (pinfunction "DFLAG/_9") (pintype "bidirectional"))
    )
    (net (code "291") (name "unconnected-(U12-FCKO-Pad1)") (class "Default")
      (node (ref "U12") (pin "1") (pinfunction "FCKO_1") (pintype "bidirectional"))
    )
    (net (code "292") (name "unconnected-(U12-INDEX{slash}-Pad10)") (class "Default")
      (node (ref "U12") (pin "10") (pinfunction "INDEX/_10") (pintype "bidirectional"))
    )
    (net (code "293") (name "unconnected-(U12-LFLAG{slash}-Pad8)") (class "Default")
      (node (ref "U12") (pin "8") (pinfunction "LFLAG/_8") (pintype "bidirectional"))
    )
  )
)
